# Full.net
KiCad netlist of a schematic drawn in EAGLE
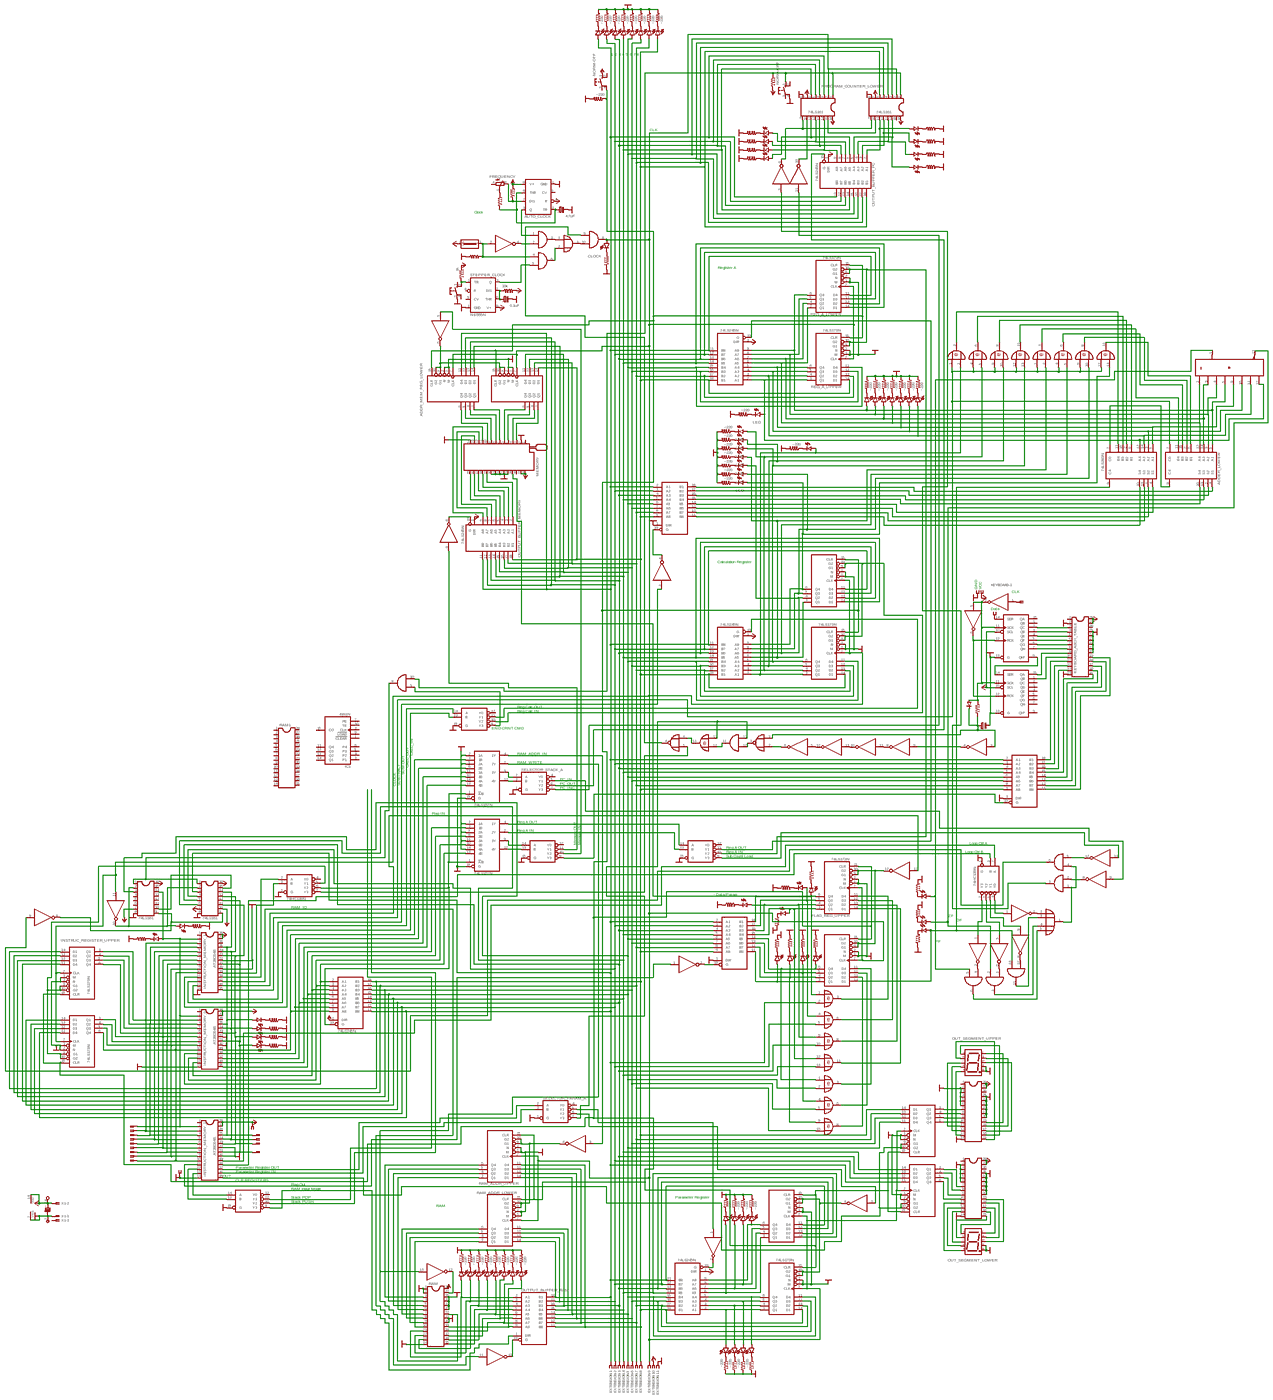
[diagram p0: schematic, sheet 1, overview]
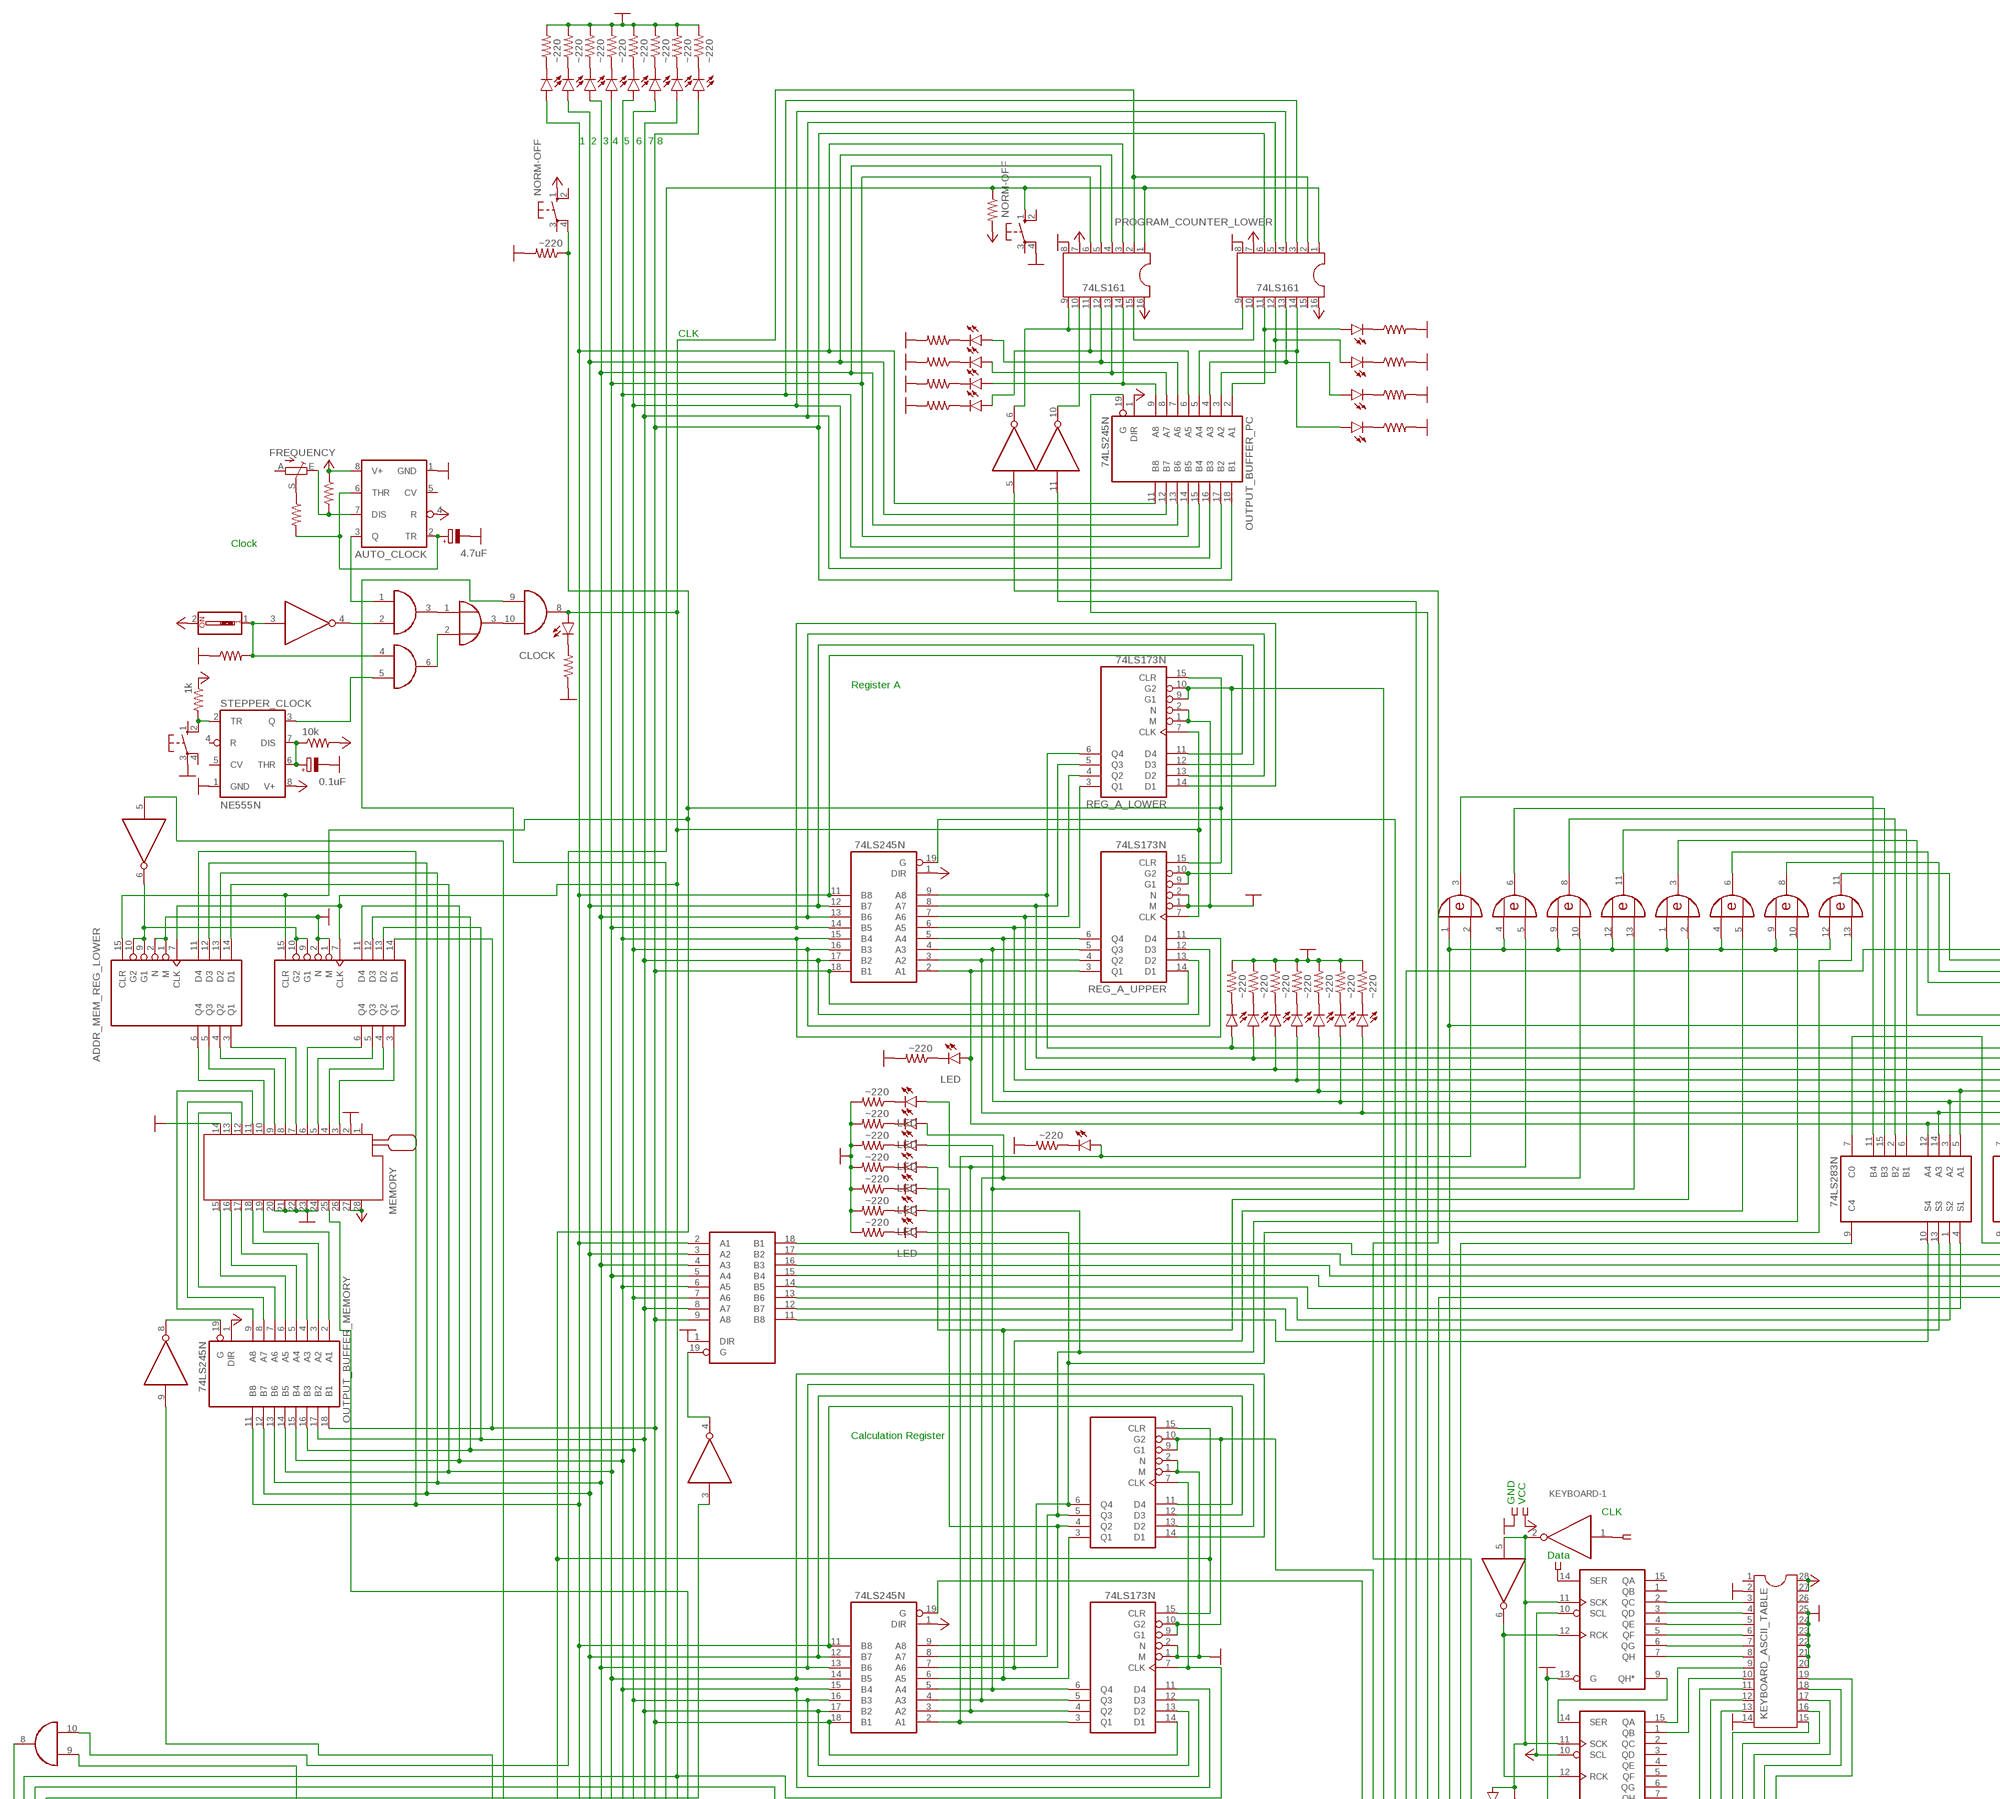
[diagram p1: schematic, sheet 1, part 1 of 4]
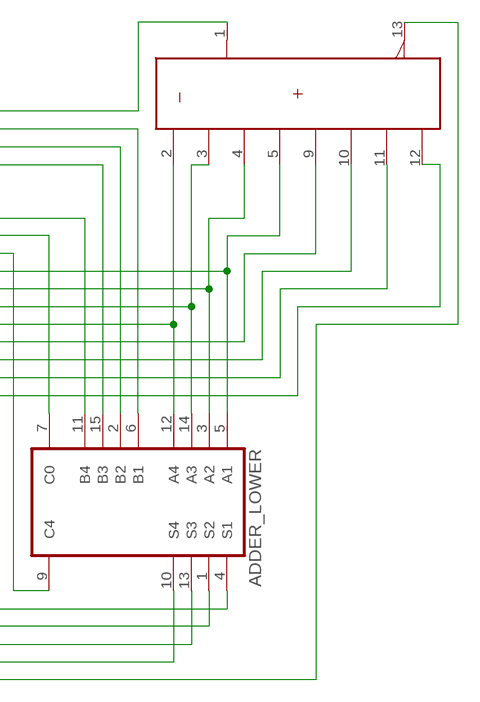
[diagram p2: schematic, sheet 1, part 2 of 4]
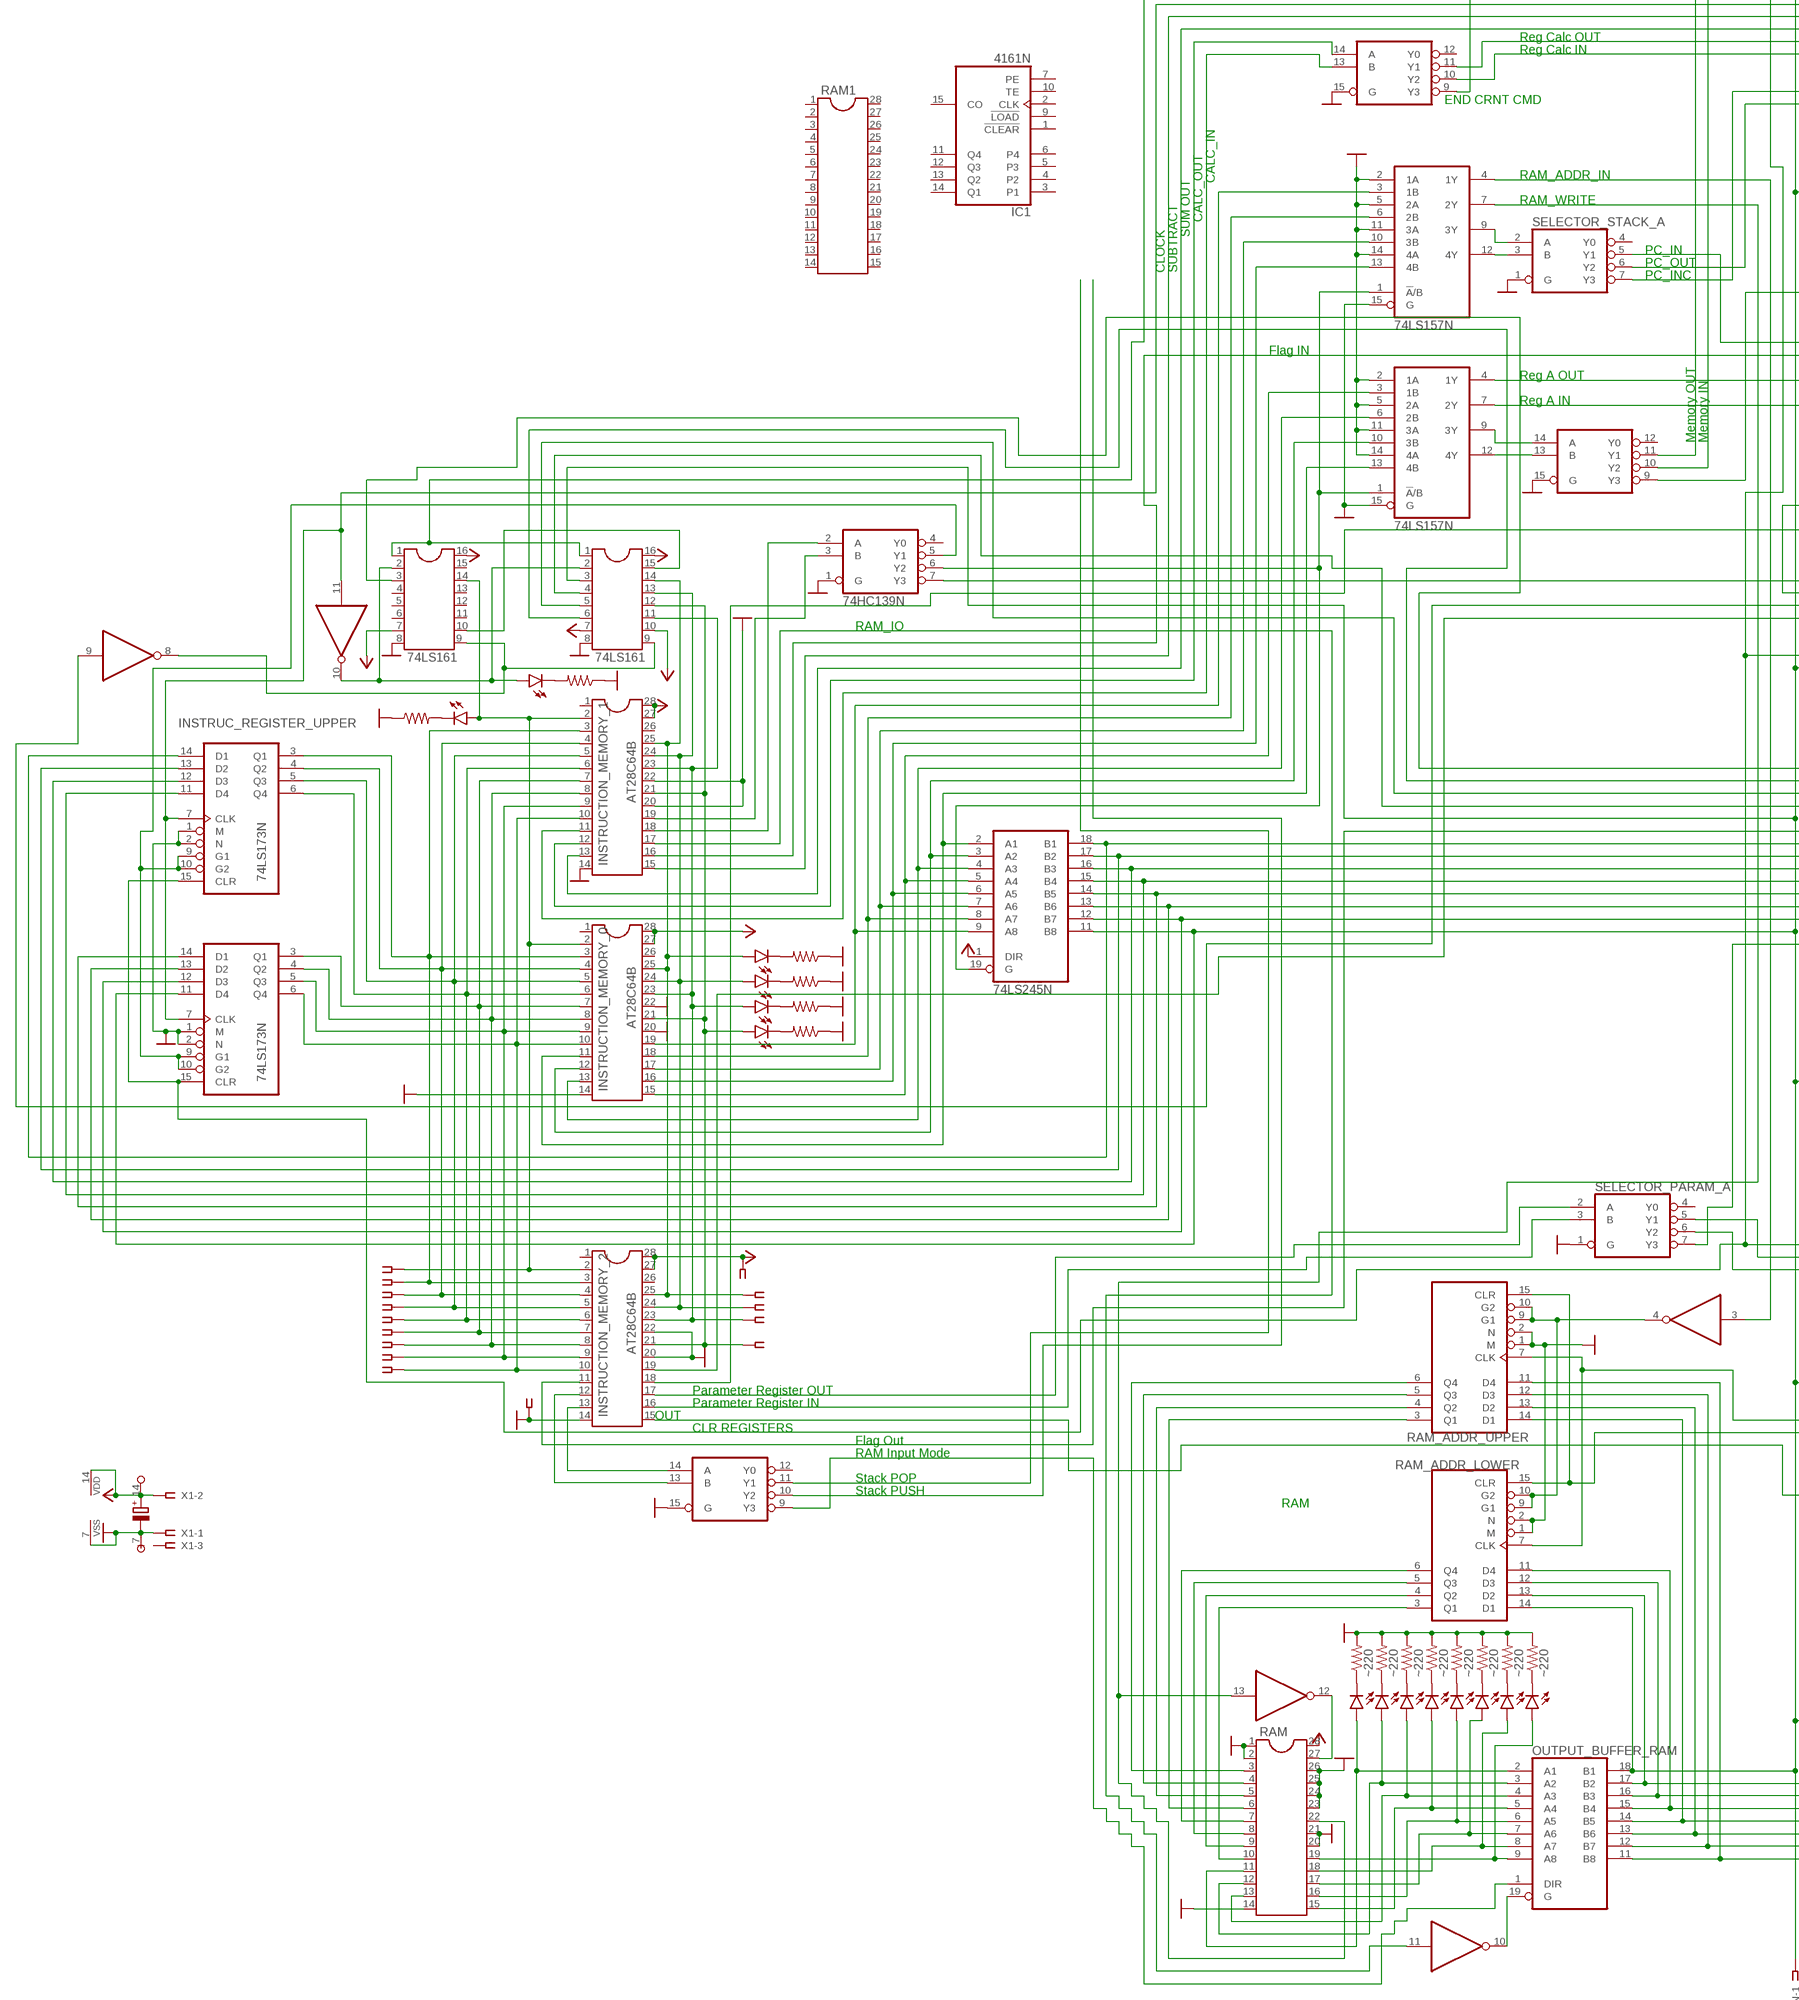
[diagram p3: schematic, sheet 1, part 3 of 4]
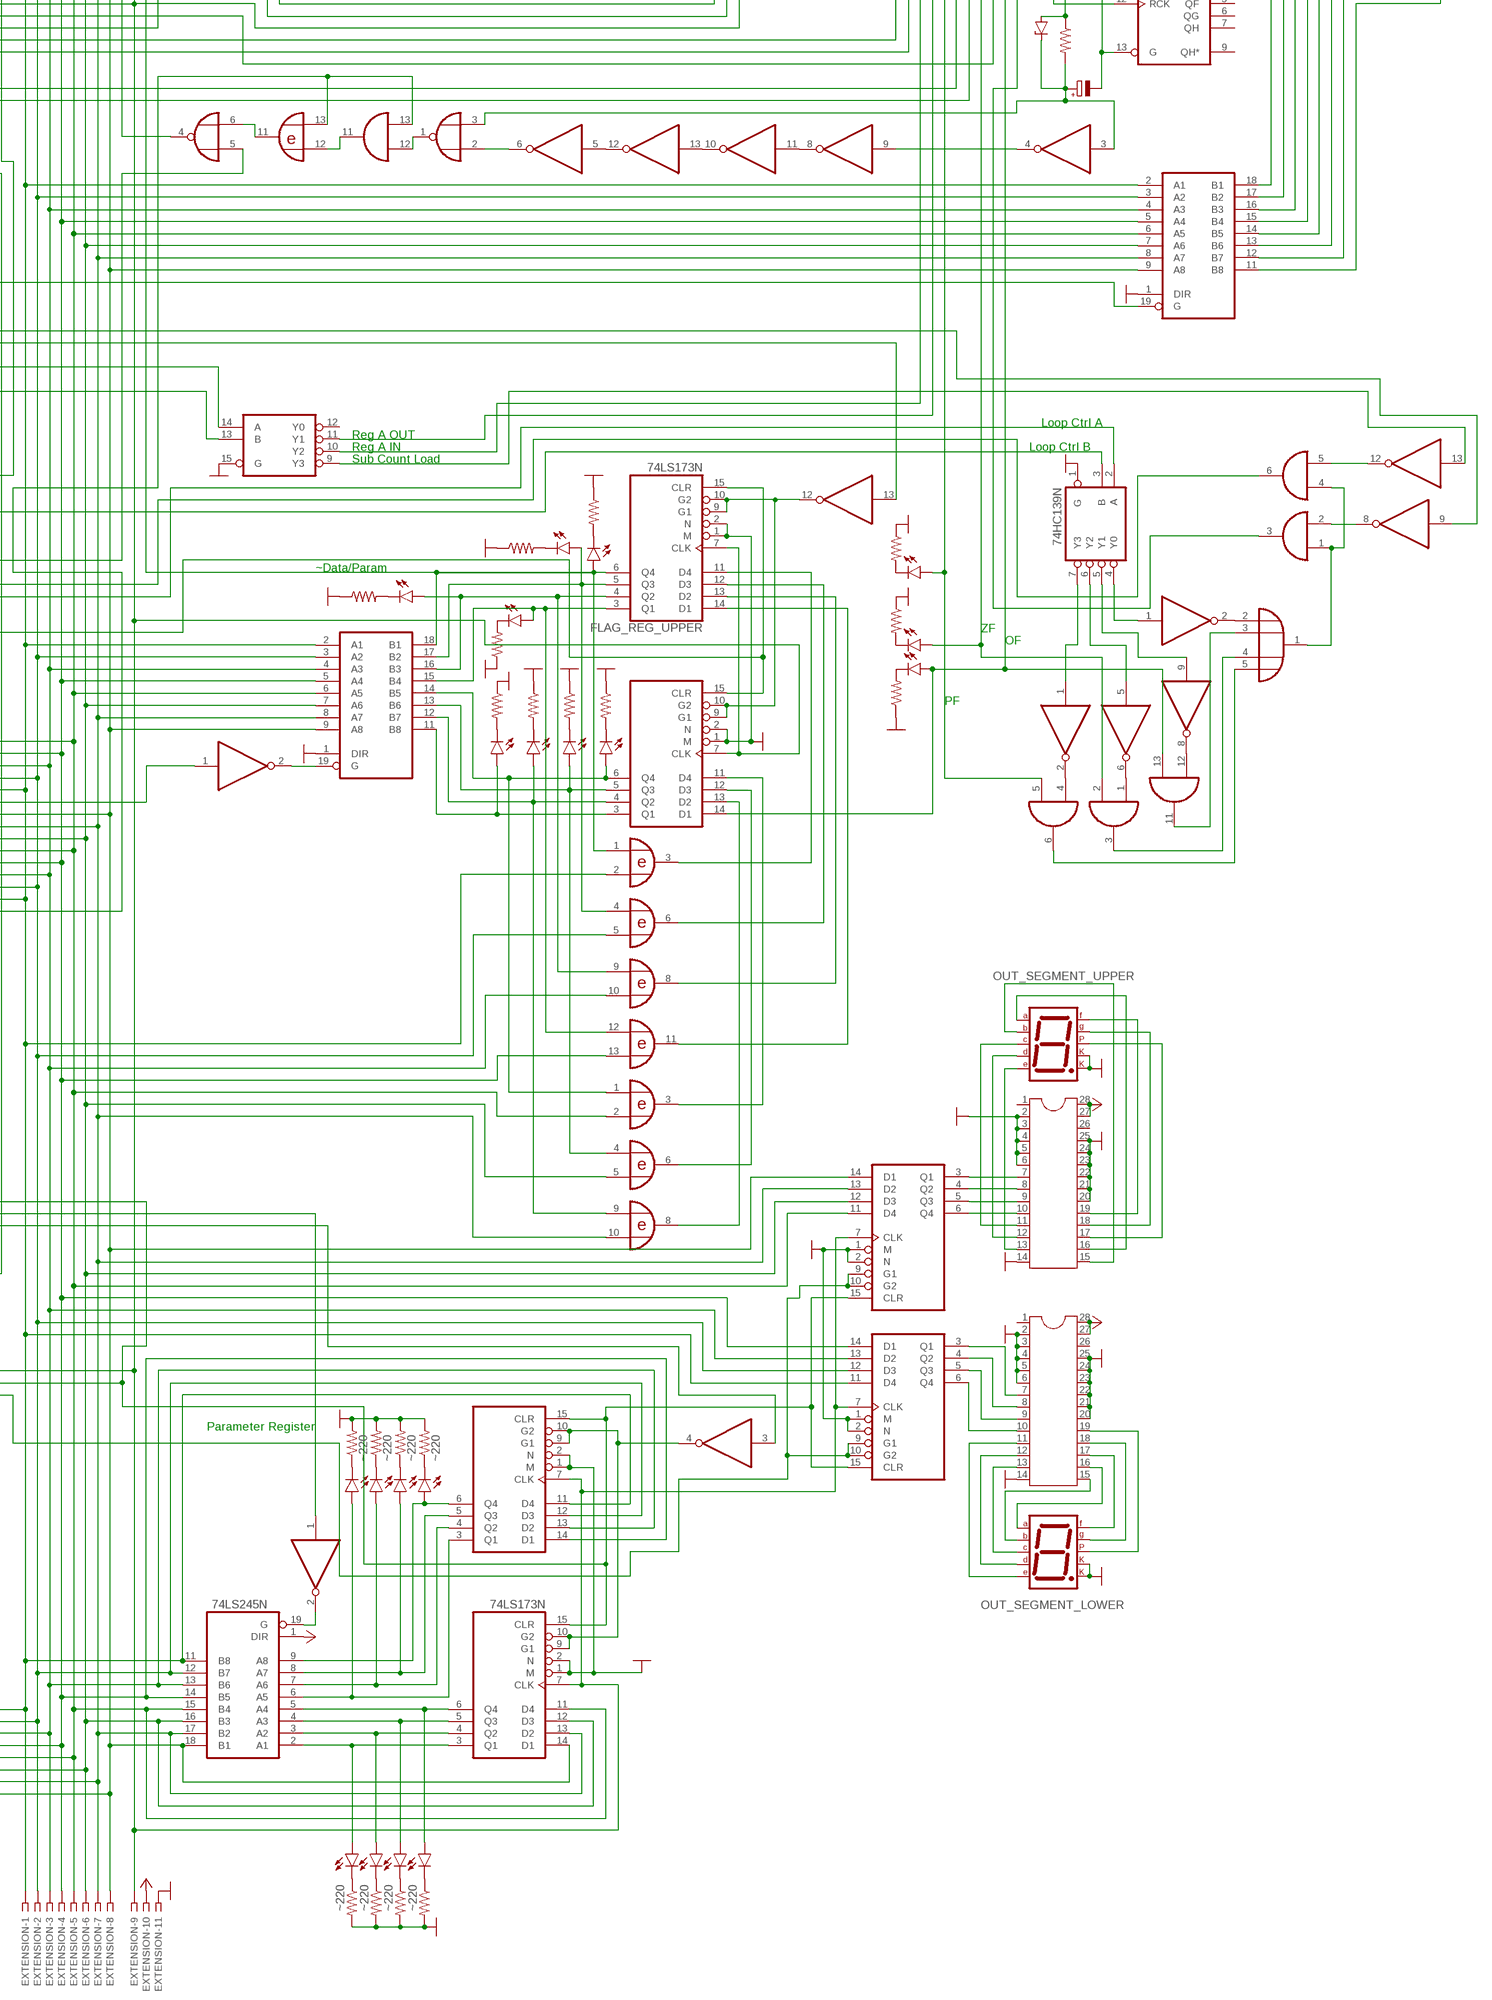
[diagram p4: schematic, sheet 1, part 4 of 4]

(export (version "E")
  (design (tool "Eeschema 10.0.6"))
  (components
    (comp (ref "4_INP_OR_GATE")
      (value "4072N")
      (footprint "eagle-import:DIL14")
      (libsource (lib "eagle-import") (part "4072N"))
    )
    (comp (ref "ADDER_LOWER")
      (value "74LS283N")
      (footprint "eagle-import:DIL16")
      (libsource (lib "eagle-import") (part "74283NLS"))
    )
    (comp (ref "ADDER_UPPER")
      (value "74LS283N")
      (footprint "eagle-import:DIL16")
      (libsource (lib "eagle-import") (part "74283NLS"))
    )
    (comp (ref "ADDR_MEM_REG_LOWER")
      (value "74LS173N")
      (footprint "eagle-import:DIL16")
      (libsource (lib "eagle-import") (part "74173NLS"))
    )
    (comp (ref "ADDR_MEM_REG_UPPER")
      (value "74LS173N")
      (footprint "eagle-import:DIL16")
      (libsource (lib "eagle-import") (part "74173NLS"))
    )
    (comp (ref "AND_GATE3_")
      (value "74LS08N")
      (footprint "eagle-import:DIL14")
      (libsource (lib "eagle-import") (part "7408NLS"))
    )
    (comp (ref "AND_GATE4_")
      (value "74LS08N")
      (footprint "eagle-import:DIL14")
      (libsource (lib "eagle-import") (part "7408NLS"))
    )
    (comp (ref "AND_GATE_")
      (value "74LS08N")
      (footprint "eagle-import:DIL14")
      (libsource (lib "eagle-import") (part "7408NLS"))
    )
    (comp (ref "AUTO_CLOCK")
      (value "NE555N")
      (footprint "eagle-import:DIL08")
      (libsource (lib "eagle-import") (part "555NNE"))
    )
    (comp (ref "C1")
      (value "4.7uF")
      (footprint "eagle-import:E2-5")
      (libsource (lib "eagle-import") (part "CPOL-EUE2-5"))
    )
    (comp (ref "C2")
      (value "0.1uF")
      (footprint "eagle-import:E2-5")
      (libsource (lib "eagle-import") (part "CPOL-EUE2-5"))
    )
    (comp (ref "C3")
      (value "0.1uF")
      (footprint "eagle-import:E2-5")
      (libsource (lib "eagle-import") (part "CPOL-EUE2-5"))
    )
    (comp (ref "C4")
      (value "0.1uF")
      (footprint "eagle-import:E2-5")
      (libsource (lib "eagle-import") (part "CPOL-EUE2-5"))
    )
    (comp (ref "CLK_MODE")
      (value "SWITCH")
      (footprint "eagle-import:EDG-01")
      (libsource (lib "eagle-import") (part "SW_DIP-1"))
    )
    (comp (ref "CLK_TRIGGER")
      (value "SWITCH")
      (footprint "eagle-import:B3F-10XX")
      (fields (field (name "MPN") "B3F-1000"))
      (libsource (lib "eagle-import") (part "10-XX"))
    )
    (comp (ref "CLOCK")
      (value "Yellow")
      (footprint "eagle-import:LED5MM")
      (libsource (lib "eagle-import") (part "LED5MM"))
    )
    (comp (ref "D1")
      (value "1N4728")
      (footprint "eagle-import:DO41Z10")
      (libsource (lib "eagle-import") (part "1N4728"))
    )
    (comp (ref "DATABUS_1")
      (value "LED")
      (footprint "eagle-import:LED5MM")
      (libsource (lib "eagle-import") (part "LED5MM"))
    )
    (comp (ref "DATABUS_2")
      (value "LED")
      (footprint "eagle-import:LED5MM")
      (libsource (lib "eagle-import") (part "LED5MM"))
    )
    (comp (ref "DATABUS_3")
      (value "LED")
      (footprint "eagle-import:LED5MM")
      (libsource (lib "eagle-import") (part "LED5MM"))
    )
    (comp (ref "DATABUS_4")
      (value "LED")
      (footprint "eagle-import:LED5MM")
      (libsource (lib "eagle-import") (part "LED5MM"))
    )
    (comp (ref "DATABUS_5")
      (value "LED")
      (footprint "eagle-import:LED5MM")
      (libsource (lib "eagle-import") (part "LED5MM"))
    )
    (comp (ref "DATABUS_6")
      (value "LED")
      (footprint "eagle-import:LED5MM")
      (libsource (lib "eagle-import") (part "LED5MM"))
    )
    (comp (ref "DATABUS_7")
      (value "LED")
      (footprint "eagle-import:LED5MM")
      (libsource (lib "eagle-import") (part "LED5MM"))
    )
    (comp (ref "DATABUS_8")
      (value "LED")
      (footprint "eagle-import:LED5MM")
      (libsource (lib "eagle-import") (part "LED5MM"))
    )
    (comp (ref "EXTENSION")
      (value "SSW-111-02-G-S")
      (footprint "eagle-import:SSW-111-02-G-S")
      (fields (field (name "MF") "Samtec Inc."))
      (libsource (lib "eagle-import") (part "SSW-111-02-G-S"))
    )
    (comp (ref "FLAG_1")
      (value "LED")
      (footprint "eagle-import:LED5MM")
      (libsource (lib "eagle-import") (part "LED5MM"))
    )
    (comp (ref "FLAG_2")
      (value "LED")
      (footprint "eagle-import:LED5MM")
      (libsource (lib "eagle-import") (part "LED5MM"))
    )
    (comp (ref "FLAG_3")
      (value "LED")
      (footprint "eagle-import:LED5MM")
      (libsource (lib "eagle-import") (part "LED5MM"))
    )
    (comp (ref "FLAG_4")
      (value "LED")
      (footprint "eagle-import:LED5MM")
      (libsource (lib "eagle-import") (part "LED5MM"))
    )
    (comp (ref "FLAG_5")
      (value "LED")
      (footprint "eagle-import:LED5MM")
      (libsource (lib "eagle-import") (part "LED5MM"))
    )
    (comp (ref "FLAG_6")
      (value "LED")
      (footprint "eagle-import:LED5MM")
      (libsource (lib "eagle-import") (part "LED5MM"))
    )
    (comp (ref "FLAG_7")
      (value "LED")
      (footprint "eagle-import:LED5MM")
      (libsource (lib "eagle-import") (part "LED5MM"))
    )
    (comp (ref "FLAG_8")
      (value "LED")
      (footprint "eagle-import:LED5MM")
      (libsource (lib "eagle-import") (part "LED5MM"))
    )
    (comp (ref "FLAG_REG_LOWER")
      (value "74LS173N")
      (footprint "eagle-import:DIL16")
      (libsource (lib "eagle-import") (part "74173NLS"))
    )
    (comp (ref "FLAG_REG_UPPER")
      (value "74LS173N")
      (footprint "eagle-import:DIL16")
      (libsource (lib "eagle-import") (part "74173NLS"))
    )
    (comp (ref "FREQUENCY")
      (value "100k")
      (footprint "eagle-import:RJ9W")
      (libsource (lib "eagle-import") (part "TRIM_EU-RJ9W"))
    )
    (comp (ref "IC1")
      (value "4161N")
      (footprint "eagle-import:DIL16")
      (libsource (lib "eagle-import") (part "4161N"))
    )
    (comp (ref "INSTRUCTIONS_EXTENSION")
      (value "SSW-115-02-G-S")
      (footprint "eagle-import:SSW-115-02-G-S")
      (fields (field (name "MF") "Samtec Inc."))
      (libsource (lib "eagle-import") (part "SSW-115-02-G-S"))
    )
    (comp (ref "INSTRUCTION_MEMORY_0")
      (value "AT28C64B")
      (footprint "eagle-import:DIL28-6")
      (libsource (lib "eagle-import") (part "DIL28"))
    )
    (comp (ref "INSTRUCTION_MEMORY_1")
      (value "AT28C64B")
      (footprint "eagle-import:DIL28-6")
      (libsource (lib "eagle-import") (part "DIL28"))
    )
    (comp (ref "INSTRUCTION_MEMORY_2")
      (value "AT28C64B")
      (footprint "eagle-import:DIL28-6")
      (libsource (lib "eagle-import") (part "DIL28"))
    )
    (comp (ref "INSTRUC_REGISTER_LOWER")
      (value "74LS173N")
      (footprint "eagle-import:DIL16")
      (libsource (lib "eagle-import") (part "74173NLS"))
    )
    (comp (ref "INSTRUC_REGISTER_UPPER")
      (value "74LS173N")
      (footprint "eagle-import:DIL16")
      (libsource (lib "eagle-import") (part "74173NLS"))
    )
    (comp (ref "INVERTED_CLK_LED")
      (value "LED")
      (footprint "eagle-import:LED5MM")
      (libsource (lib "eagle-import") (part "LED5MM"))
    )
    (comp (ref "KEYBOARD")
      (value "SSW-104-02-G-S")
      (footprint "eagle-import:SSW-104-02-G-S")
      (fields (field (name "MF") "Samtec Inc."))
      (libsource (lib "eagle-import") (part "SSW-104-02-G-S"))
    )
    (comp (ref "KEYBOARD_ASCII_TABLE")
      (value "AT28C64B")
      (footprint "eagle-import:DIL28-6")
      (libsource (lib "eagle-import") (part "DIL28"))
    )
    (comp (ref "KEYBOARD_SHIFT_LOWER")
      (value "74LS595N")
      (footprint "eagle-import:DIL16")
      (libsource (lib "eagle-import") (part "74595NLS"))
    )
    (comp (ref "KEYBOARD_SHIFT_UPPER")
      (value "74LS595N")
      (footprint "eagle-import:DIL16")
      (libsource (lib "eagle-import") (part "74595NLS"))
    )
    (comp (ref "LED_A_REG_1")
      (value "LED")
      (footprint "eagle-import:LED5MM")
      (libsource (lib "eagle-import") (part "LED5MM"))
    )
    (comp (ref "LED_A_REG_2")
      (value "LED")
      (footprint "eagle-import:LED5MM")
      (libsource (lib "eagle-import") (part "LED5MM"))
    )
    (comp (ref "LED_A_REG_3")
      (value "LED")
      (footprint "eagle-import:LED5MM")
      (libsource (lib "eagle-import") (part "LED5MM"))
    )
    (comp (ref "LED_A_REG_4")
      (value "LED")
      (footprint "eagle-import:LED5MM")
      (libsource (lib "eagle-import") (part "LED5MM"))
    )
    (comp (ref "LED_A_REG_5")
      (value "LED")
      (footprint "eagle-import:LED5MM")
      (libsource (lib "eagle-import") (part "LED5MM"))
    )
    (comp (ref "LED_A_REG_6")
      (value "LED")
      (footprint "eagle-import:LED5MM")
      (libsource (lib "eagle-import") (part "LED5MM"))
    )
    (comp (ref "LED_A_REG_7")
      (value "LED")
      (footprint "eagle-import:LED5MM")
      (libsource (lib "eagle-import") (part "LED5MM"))
    )
    (comp (ref "LED_A_REG_8")
      (value "LED")
      (footprint "eagle-import:LED5MM")
      (libsource (lib "eagle-import") (part "LED5MM"))
    )
    (comp (ref "LED_B_REG_1")
      (value "LED")
      (footprint "eagle-import:LED5MM")
      (libsource (lib "eagle-import") (part "LED5MM"))
    )
    (comp (ref "LED_B_REG_2")
      (value "LED")
      (footprint "eagle-import:LED5MM")
      (libsource (lib "eagle-import") (part "LED5MM"))
    )
    (comp (ref "LED_B_REG_3")
      (value "LED")
      (footprint "eagle-import:LED5MM")
      (libsource (lib "eagle-import") (part "LED5MM"))
    )
    (comp (ref "LED_B_REG_4")
      (value "LED")
      (footprint "eagle-import:LED5MM")
      (libsource (lib "eagle-import") (part "LED5MM"))
    )
    (comp (ref "LED_B_REG_5")
      (value "LED")
      (footprint "eagle-import:LED5MM")
      (libsource (lib "eagle-import") (part "LED5MM"))
    )
    (comp (ref "LED_B_REG_6")
      (value "LED")
      (footprint "eagle-import:LED5MM")
      (libsource (lib "eagle-import") (part "LED5MM"))
    )
    (comp (ref "LED_B_REG_7")
      (value "LED")
      (footprint "eagle-import:LED5MM")
      (libsource (lib "eagle-import") (part "LED5MM"))
    )
    (comp (ref "LED_B_REG_8")
      (value "LED")
      (footprint "eagle-import:LED5MM")
      (libsource (lib "eagle-import") (part "LED5MM"))
    )
    (comp (ref "MEMORY")
      (value "228-1277-00-0602J")
      (footprint "eagle-import:228-1277-00-0602J")
      (fields (field (name "MF") "3M"))
      (libsource (lib "eagle-import") (part "228-?00-0602J1277-"))
    )
    (comp (ref "MICRO_COUNTER_LOWER")
      (value "74LS161")
      (footprint "eagle-import:DIL16")
      (libsource (lib "eagle-import") (part "DIL16"))
    )
    (comp (ref "MICRO_COUNTER_UPPER")
      (value "74LS161")
      (footprint "eagle-import:DIL16")
      (libsource (lib "eagle-import") (part "DIL16"))
    )
    (comp (ref "NOR_GATE_")
      (value "74LS02N")
      (footprint "eagle-import:DIL14")
      (libsource (lib "eagle-import") (part "7402NLS"))
    )
    (comp (ref "NOT_GATE1_")
      (value "74LS04N")
      (footprint "eagle-import:DIL14")
      (libsource (lib "eagle-import") (part "7404NLS"))
    )
    (comp (ref "NOT_GATE2_")
      (value "74LS04N")
      (footprint "eagle-import:DIL14")
      (libsource (lib "eagle-import") (part "7404NLS"))
    )
    (comp (ref "NOT_GATE3_")
      (value "74LS04N")
      (footprint "eagle-import:DIL14")
      (libsource (lib "eagle-import") (part "7404NLS"))
    )
    (comp (ref "NOT_GATE4_")
      (value "74LS04N")
      (footprint "eagle-import:DIL14")
      (fields (field (name "SPICEPREFIX") "B"))
      (libsource (lib "eagle-import") (part "7404NLS"))
    )
    (comp (ref "NOT_GATE_")
      (value "74LS04N")
      (footprint "eagle-import:DIL14")
      (libsource (lib "eagle-import") (part "7404NLS"))
    )
    (comp (ref "OR_GATE_")
      (value "74LS32N")
      (footprint "eagle-import:DIL14")
      (libsource (lib "eagle-import") (part "7432NLS"))
    )
    (comp (ref "OUTPUT_BUFFER_ALU")
      (value "74LS245N")
      (footprint "eagle-import:DIL20")
      (libsource (lib "eagle-import") (part "74245NLS"))
    )
    (comp (ref "OUTPUT_BUFFER_CALC_REG")
      (value "74LS245N")
      (footprint "eagle-import:DIL20")
      (libsource (lib "eagle-import") (part "74245NLS"))
    )
    (comp (ref "OUTPUT_BUFFER_FLAGS")
      (value "74HC245N")
      (footprint "eagle-import:DIL20")
      (libsource (lib "eagle-import") (part "74245NHC"))
    )
    (comp (ref "OUTPUT_BUFFER_INSTRUCTION")
      (value "74LS245N")
      (footprint "eagle-import:DIL20")
      (libsource (lib "eagle-import") (part "74xx-us_88_74245NLS"))
    )
    (comp (ref "OUTPUT_BUFFER_KEYBOARD")
      (value "74LS245N")
      (footprint "eagle-import:DIL20")
      (libsource (lib "eagle-import") (part "74245NLS"))
    )
    (comp (ref "OUTPUT_BUFFER_MEMORY")
      (value "74LS245N")
      (footprint "eagle-import:DIL20")
      (libsource (lib "eagle-import") (part "74245NLS"))
    )
    (comp (ref "OUTPUT_BUFFER_PARAM_REG")
      (value "74LS245N")
      (footprint "eagle-import:DIL20")
      (libsource (lib "eagle-import") (part "74245NLS"))
    )
    (comp (ref "OUTPUT_BUFFER_PC")
      (value "74LS245N")
      (footprint "eagle-import:DIL20")
      (libsource (lib "eagle-import") (part "74245NLS"))
    )
    (comp (ref "OUTPUT_BUFFER_RAM")
      (value "74HC245N")
      (footprint "eagle-import:DIL20")
      (libsource (lib "eagle-import") (part "74245NHC"))
    )
    (comp (ref "OUTPUT_BUFFER_REG_A")
      (value "74LS245N")
      (footprint "eagle-import:DIL20")
      (libsource (lib "eagle-import") (part "74245NLS"))
    )
    (comp (ref "OUT_REG_LOWER")
      (value "74LS173N")
      (footprint "eagle-import:DIL16")
      (libsource (lib "eagle-import") (part "74173NLS"))
    )
    (comp (ref "OUT_REG_UPPER")
      (value "74LS173N")
      (footprint "eagle-import:DIL16")
      (libsource (lib "eagle-import") (part "74173NLS"))
    )
    (comp (ref "OUT_ROM_LOWER")
      (value "AT28C64B")
      (footprint "eagle-import:DIL28-6")
      (libsource (lib "eagle-import") (part "DIL28"))
    )
    (comp (ref "OUT_ROM_UPPER")
      (value "AT28C64B")
      (footprint "eagle-import:DIL28-6")
      (libsource (lib "eagle-import") (part "DIL28"))
    )
    (comp (ref "OUT_SEGMENT_LOWER")
      (value "LED")
      (footprint "eagle-import:7SEG-13")
      (libsource (lib "eagle-import") (part "7SEG-CK"))
    )
    (comp (ref "OUT_SEGMENT_UPPER")
      (value "LED")
      (footprint "eagle-import:7SEG-13")
      (libsource (lib "eagle-import") (part "7SEG-CK"))
    )
    (comp (ref "OVERFLOW_FLAG")
      (value "LED")
      (footprint "eagle-import:LED5MM")
      (libsource (lib "eagle-import") (part "LED5MM"))
    )
    (comp (ref "PARAM_LED_1")
      (value "LED3MM")
      (footprint "eagle-import:LED3MM")
      (libsource (lib "eagle-import") (part "LED3MM"))
    )
    (comp (ref "PARAM_LED_2")
      (value "LED3MM")
      (footprint "eagle-import:LED3MM")
      (libsource (lib "eagle-import") (part "LED3MM"))
    )
    (comp (ref "PARAM_LED_3")
      (value "LED3MM")
      (footprint "eagle-import:LED3MM")
      (libsource (lib "eagle-import") (part "LED3MM"))
    )
    (comp (ref "PARAM_LED_4")
      (value "LED3MM")
      (footprint "eagle-import:LED3MM")
      (libsource (lib "eagle-import") (part "LED3MM"))
    )
    (comp (ref "PARAM_LED_5")
      (value "LED3MM")
      (footprint "eagle-import:LED3MM")
      (libsource (lib "eagle-import") (part "LED3MM"))
    )
    (comp (ref "PARAM_LED_6")
      (value "LED3MM")
      (footprint "eagle-import:LED3MM")
      (libsource (lib "eagle-import") (part "LED3MM"))
    )
    (comp (ref "PARAM_LED_7")
      (value "LED3MM")
      (footprint "eagle-import:LED3MM")
      (libsource (lib "eagle-import") (part "LED3MM"))
    )
    (comp (ref "PARAM_LED_8")
      (value "LED3MM")
      (footprint "eagle-import:LED3MM")
      (libsource (lib "eagle-import") (part "LED3MM"))
    )
    (comp (ref "PC_1")
      (value "LED5MM")
      (footprint "eagle-import:LED5MM")
      (libsource (lib "eagle-import") (part "LED5MM"))
    )
    (comp (ref "PC_2")
      (value "LED5MM")
      (footprint "eagle-import:LED5MM")
      (libsource (lib "eagle-import") (part "LED5MM"))
    )
    (comp (ref "PC_3")
      (value "LED5MM")
      (footprint "eagle-import:LED5MM")
      (libsource (lib "eagle-import") (part "LED5MM"))
    )
    (comp (ref "PC_4")
      (value "LED5MM")
      (footprint "eagle-import:LED5MM")
      (libsource (lib "eagle-import") (part "LED5MM"))
    )
    (comp (ref "PC_5")
      (value "LED5MM")
      (footprint "eagle-import:LED5MM")
      (libsource (lib "eagle-import") (part "LED5MM"))
    )
    (comp (ref "PC_6")
      (value "LED5MM")
      (footprint "eagle-import:LED5MM")
      (libsource (lib "eagle-import") (part "LED5MM"))
    )
    (comp (ref "PC_7")
      (value "LED5MM")
      (footprint "eagle-import:LED5MM")
      (libsource (lib "eagle-import") (part "LED5MM"))
    )
    (comp (ref "PC_8")
      (value "LED5MM")
      (footprint "eagle-import:LED5MM")
      (libsource (lib "eagle-import") (part "LED5MM"))
    )
    (comp (ref "POSITIVE_FLAG")
      (value "LED")
      (footprint "eagle-import:LED5MM")
      (libsource (lib "eagle-import") (part "LED5MM"))
    )
    (comp (ref "PROGRAM_COUNTER_LOWER")
      (value "74LS161")
      (footprint "eagle-import:DIL16")
      (libsource (lib "eagle-import") (part "DIL16"))
    )
    (comp (ref "PROGRAM_COUNTER_UPPER")
      (value "74LS161")
      (footprint "eagle-import:DIL16")
      (libsource (lib "eagle-import") (part "DIL16"))
    )
    (comp (ref "R1")
      (value "1k")
      (footprint "eagle-import:0204_7")
      (libsource (lib "eagle-import") (part "R-US_0204/7"))
    )
    (comp (ref "R2")
      (value "1k")
      (footprint "eagle-import:0204_7")
      (libsource (lib "eagle-import") (part "R-US_0204/7"))
    )
    (comp (ref "R3")
      (value "10k")
      (footprint "eagle-import:0204_7")
      (libsource (lib "eagle-import") (part "R-US_0204/7"))
    )
    (comp (ref "R4")
      (value "220")
      (footprint "eagle-import:0204_7")
      (libsource (lib "eagle-import") (part "R-US_0204/7"))
    )
    (comp (ref "R5")
      (value "~220")
      (footprint "eagle-import:0204_7")
      (libsource (lib "eagle-import") (part "R-US_0204/7"))
    )
    (comp (ref "R6")
      (value "~220")
      (footprint "eagle-import:0204_7")
      (libsource (lib "eagle-import") (part "R-US_0204/7"))
    )
    (comp (ref "R7")
      (value "220")
      (footprint "eagle-import:0204_7")
      (libsource (lib "eagle-import") (part "R-US_0204/7"))
    )
    (comp (ref "R8")
      (value "~220")
      (footprint "eagle-import:0204_7")
      (libsource (lib "eagle-import") (part "R-US_0204/7"))
    )
    (comp (ref "R9")
      (value "~220")
      (footprint "eagle-import:0204_7")
      (libsource (lib "eagle-import") (part "R-US_0204/7"))
    )
    (comp (ref "R10")
      (value "~220")
      (footprint "eagle-import:0204_7")
      (libsource (lib "eagle-import") (part "R-US_0204/7"))
    )
    (comp (ref "R11")
      (value "~220")
      (footprint "eagle-import:0204_7")
      (libsource (lib "eagle-import") (part "R-US_0204/7"))
    )
    (comp (ref "R12")
      (value "~220")
      (footprint "eagle-import:0204_7")
      (libsource (lib "eagle-import") (part "R-US_0204/7"))
    )
    (comp (ref "R13")
      (value "~220")
      (footprint "eagle-import:0204_7")
      (libsource (lib "eagle-import") (part "R-US_0204/7"))
    )
    (comp (ref "R14")
      (value "~220")
      (footprint "eagle-import:0204_7")
      (libsource (lib "eagle-import") (part "R-US_0204/7"))
    )
    (comp (ref "R15")
      (value "~220")
      (footprint "eagle-import:0204_7")
      (libsource (lib "eagle-import") (part "R-US_0204/7"))
    )
    (comp (ref "R16")
      (value "~220")
      (footprint "eagle-import:0204_7")
      (libsource (lib "eagle-import") (part "R-US_0204/7"))
    )
    (comp (ref "R17")
      (value "~220")
      (footprint "eagle-import:0204_7")
      (libsource (lib "eagle-import") (part "R-US_0204/7"))
    )
    (comp (ref "R18")
      (value "~220")
      (footprint "eagle-import:0204_7")
      (libsource (lib "eagle-import") (part "R-US_0204/7"))
    )
    (comp (ref "R19")
      (value "~220")
      (footprint "eagle-import:0204_7")
      (libsource (lib "eagle-import") (part "R-US_0204/7"))
    )
    (comp (ref "R20")
      (value "~220")
      (footprint "eagle-import:0204_7")
      (libsource (lib "eagle-import") (part "R-US_0204/7"))
    )
    (comp (ref "R21")
      (value "~220")
      (footprint "eagle-import:0204_7")
      (libsource (lib "eagle-import") (part "R-US_0204/7"))
    )
    (comp (ref "R22")
      (value "~220")
      (footprint "eagle-import:0204_7")
      (libsource (lib "eagle-import") (part "R-US_0204/7"))
    )
    (comp (ref "R23")
      (value "~220")
      (footprint "eagle-import:0204_7")
      (libsource (lib "eagle-import") (part "R-US_0204/7"))
    )
    (comp (ref "R24")
      (value "~220")
      (footprint "eagle-import:0204_7")
      (libsource (lib "eagle-import") (part "R-US_0204/7"))
    )
    (comp (ref "R25")
      (value "~220")
      (footprint "eagle-import:0204_7")
      (libsource (lib "eagle-import") (part "R-US_0204/7"))
    )
    (comp (ref "R26")
      (value "~220")
      (footprint "eagle-import:0204_7")
      (libsource (lib "eagle-import") (part "R-US_0204/7"))
    )
    (comp (ref "R27")
      (value "~220")
      (footprint "eagle-import:0204_7")
      (libsource (lib "eagle-import") (part "R-US_0204/7"))
    )
    (comp (ref "R28")
      (value "~220")
      (footprint "eagle-import:0204_7")
      (libsource (lib "eagle-import") (part "R-US_0204/7"))
    )
    (comp (ref "R29")
      (value "~220")
      (footprint "eagle-import:0204_7")
      (libsource (lib "eagle-import") (part "R-US_0204/7"))
    )
    (comp (ref "R30")
      (value "~220")
      (footprint "eagle-import:0204_7")
      (libsource (lib "eagle-import") (part "R-US_0204/7"))
    )
    (comp (ref "R31")
      (value "~220")
      (footprint "eagle-import:0204_7")
      (libsource (lib "eagle-import") (part "R-US_0204/7"))
    )
    (comp (ref "R32")
      (value "~220")
      (footprint "eagle-import:0204_7")
      (libsource (lib "eagle-import") (part "R-US_0204/7"))
    )
    (comp (ref "R33")
      (value "~220")
      (footprint "eagle-import:0204_7")
      (libsource (lib "eagle-import") (part "R-US_0204/7"))
    )
    (comp (ref "R34")
      (value "~220")
      (footprint "eagle-import:0204_7")
      (libsource (lib "eagle-import") (part "R-US_0204/7"))
    )
    (comp (ref "R35")
      (value "~220")
      (footprint "eagle-import:0204_7")
      (libsource (lib "eagle-import") (part "R-US_0204/7"))
    )
    (comp (ref "R36")
      (value "~220")
      (footprint "eagle-import:0204_7")
      (libsource (lib "eagle-import") (part "R-US_0204/7"))
    )
    (comp (ref "R37")
      (value "~220")
      (footprint "eagle-import:0204_7")
      (libsource (lib "eagle-import") (part "R-US_0204/7"))
    )
    (comp (ref "R38")
      (value "~220")
      (footprint "eagle-import:0204_7")
      (libsource (lib "eagle-import") (part "R-US_0204/7"))
    )
    (comp (ref "R39")
      (value "~220")
      (footprint "eagle-import:0204_7")
      (libsource (lib "eagle-import") (part "R-US_0204/7"))
    )
    (comp (ref "R40")
      (value "~220")
      (footprint "eagle-import:0204_7")
      (libsource (lib "eagle-import") (part "R-US_0204/7"))
    )
    (comp (ref "R41")
      (value "~220")
      (footprint "eagle-import:0204_7")
      (libsource (lib "eagle-import") (part "R-US_0204/7"))
    )
    (comp (ref "R42")
      (value "~220")
      (footprint "eagle-import:0204_7")
      (libsource (lib "eagle-import") (part "R-US_0204/7"))
    )
    (comp (ref "R43")
      (value "~220")
      (footprint "eagle-import:0204_7")
      (libsource (lib "eagle-import") (part "R-US_0204/7"))
    )
    (comp (ref "R44")
      (value "~220")
      (footprint "eagle-import:0204_7")
      (libsource (lib "eagle-import") (part "R-US_0204/7"))
    )
    (comp (ref "R45")
      (value "~220")
      (footprint "eagle-import:0204_7")
      (libsource (lib "eagle-import") (part "R-US_0204/7"))
    )
    (comp (ref "R53")
      (value "~220")
      (footprint "eagle-import:0204_7")
      (libsource (lib "eagle-import") (part "R-US_0204/7"))
    )
    (comp (ref "R54")
      (value "~220")
      (footprint "eagle-import:0204_7")
      (libsource (lib "eagle-import") (part "R-US_0204/7"))
    )
    (comp (ref "R55")
      (value "~220")
      (footprint "eagle-import:0204_7")
      (libsource (lib "eagle-import") (part "R-US_0204/7"))
    )
    (comp (ref "R56")
      (value "~220")
      (footprint "eagle-import:0204_7")
      (libsource (lib "eagle-import") (part "R-US_0204/7"))
    )
    (comp (ref "R57")
      (value "~220")
      (footprint "eagle-import:0204_7")
      (libsource (lib "eagle-import") (part "R-US_0204/7"))
    )
    (comp (ref "R58")
      (value "~220")
      (footprint "eagle-import:0204_7")
      (libsource (lib "eagle-import") (part "R-US_0204/7"))
    )
    (comp (ref "R59")
      (value "~220")
      (footprint "eagle-import:0204_7")
      (libsource (lib "eagle-import") (part "R-US_0204/7"))
    )
    (comp (ref "R60")
      (value "~220")
      (footprint "eagle-import:0204_7")
      (libsource (lib "eagle-import") (part "R-US_0204/7"))
    )
    (comp (ref "R61")
      (value "~220")
      (footprint "eagle-import:0204_7")
      (libsource (lib "eagle-import") (part "R-US_0204/7"))
    )
    (comp (ref "R62")
      (value "~220")
      (footprint "eagle-import:0204_7")
      (libsource (lib "eagle-import") (part "R-US_0204/7"))
    )
    (comp (ref "R63")
      (value "~220")
      (footprint "eagle-import:0204_7")
      (libsource (lib "eagle-import") (part "R-US_0204/7"))
    )
    (comp (ref "R64")
      (value "~220")
      (footprint "eagle-import:0204_7")
      (libsource (lib "eagle-import") (part "R-US_0204/7"))
    )
    (comp (ref "R65")
      (value "~220")
      (footprint "eagle-import:0204_7")
      (libsource (lib "eagle-import") (part "R-US_0204/7"))
    )
    (comp (ref "R66")
      (value "~220")
      (footprint "eagle-import:0204_7")
      (libsource (lib "eagle-import") (part "R-US_0204/7"))
    )
    (comp (ref "R67")
      (value "~220")
      (footprint "eagle-import:0204_7")
      (libsource (lib "eagle-import") (part "R-US_0204/7"))
    )
    (comp (ref "R68")
      (value "~220")
      (footprint "eagle-import:0204_7")
      (libsource (lib "eagle-import") (part "R-US_0204/7"))
    )
    (comp (ref "R69")
      (value "~220")
      (footprint "eagle-import:0204_7")
      (libsource (lib "eagle-import") (part "R-US_0204/7"))
    )
    (comp (ref "R70")
      (value "~220")
      (footprint "eagle-import:0204_7")
      (libsource (lib "eagle-import") (part "R-US_0204/7"))
    )
    (comp (ref "R71")
      (value "~220")
      (footprint "eagle-import:0204_7")
      (libsource (lib "eagle-import") (part "R-US_0204/7"))
    )
    (comp (ref "R72")
      (value "~220")
      (footprint "eagle-import:0204_7")
      (libsource (lib "eagle-import") (part "R-US_0204/7"))
    )
    (comp (ref "R73")
      (value "~220")
      (footprint "eagle-import:0204_7")
      (libsource (lib "eagle-import") (part "R-US_0204/7"))
    )
    (comp (ref "R74")
      (value "~220")
      (footprint "eagle-import:0204_7")
      (libsource (lib "eagle-import") (part "R-US_0204/7"))
    )
    (comp (ref "R75")
      (value "~220")
      (footprint "eagle-import:0204_7")
      (libsource (lib "eagle-import") (part "R-US_0204/7"))
    )
    (comp (ref "R76")
      (value "~220")
      (footprint "eagle-import:0204_7")
      (libsource (lib "eagle-import") (part "R-US_0204/7"))
    )
    (comp (ref "R77")
      (value "~220")
      (footprint "eagle-import:0204_7")
      (libsource (lib "eagle-import") (part "R-US_0204/7"))
    )
    (comp (ref "R78")
      (value "~220")
      (footprint "eagle-import:0204_7")
      (libsource (lib "eagle-import") (part "R-US_0204/7"))
    )
    (comp (ref "R79")
      (value "~220")
      (footprint "eagle-import:0204_7")
      (libsource (lib "eagle-import") (part "R-US_0204/7"))
    )
    (comp (ref "R80")
      (value "~220")
      (footprint "eagle-import:0204_7")
      (libsource (lib "eagle-import") (part "R-US_0204/7"))
    )
    (comp (ref "R81")
      (value "~220")
      (footprint "eagle-import:0204_7")
      (libsource (lib "eagle-import") (part "R-US_0204/7"))
    )
    (comp (ref "RAM")
      (value "71256SA15TPG")
      (footprint "eagle-import:DIL28-3")
      (libsource (lib "eagle-import") (part "DIL28-3"))
    )
    (comp (ref "RAM1")
      (value "71256SA15TPG")
      (footprint "eagle-import:DIL28-3")
      (libsource (lib "eagle-import") (part "DIL28-3"))
    )
    (comp (ref "RAM_ADDR_LOWER")
      (value "74LS173N")
      (footprint "eagle-import:DIL16")
      (libsource (lib "eagle-import") (part "74173NLS"))
    )
    (comp (ref "RAM_ADDR_UPPER")
      (value "74LS173N")
      (footprint "eagle-import:DIL16")
      (libsource (lib "eagle-import") (part "74173NLS"))
    )
    (comp (ref "RAM_LED_1")
      (value "LED3MM")
      (footprint "eagle-import:LED3MM")
      (libsource (lib "eagle-import") (part "LED3MM"))
    )
    (comp (ref "RAM_LED_2")
      (value "LED3MM")
      (footprint "eagle-import:LED3MM")
      (libsource (lib "eagle-import") (part "LED3MM"))
    )
    (comp (ref "RAM_LED_3")
      (value "LED3MM")
      (footprint "eagle-import:LED3MM")
      (libsource (lib "eagle-import") (part "LED3MM"))
    )
    (comp (ref "RAM_LED_4")
      (value "LED3MM")
      (footprint "eagle-import:LED3MM")
      (libsource (lib "eagle-import") (part "LED3MM"))
    )
    (comp (ref "RAM_LED_5")
      (value "LED3MM")
      (footprint "eagle-import:LED3MM")
      (libsource (lib "eagle-import") (part "LED3MM"))
    )
    (comp (ref "RAM_LED_6")
      (value "LED3MM")
      (footprint "eagle-import:LED3MM")
      (libsource (lib "eagle-import") (part "LED3MM"))
    )
    (comp (ref "RAM_LED_7")
      (value "LED3MM")
      (footprint "eagle-import:LED3MM")
      (libsource (lib "eagle-import") (part "LED3MM"))
    )
    (comp (ref "RAM_LED_8")
      (value "LED3MM")
      (footprint "eagle-import:LED3MM")
      (libsource (lib "eagle-import") (part "LED3MM"))
    )
    (comp (ref "REG_A_LOWER")
      (value "74LS173N")
      (footprint "eagle-import:DIL16")
      (libsource (lib "eagle-import") (part "74173NLS"))
    )
    (comp (ref "REG_A_UPPER")
      (value "74LS173N")
      (footprint "eagle-import:DIL16")
      (libsource (lib "eagle-import") (part "74173NLS"))
    )
    (comp (ref "REG_CALC_LOWER")
      (value "74LS173N")
      (footprint "eagle-import:DIL16")
      (libsource (lib "eagle-import") (part "74173NLS"))
    )
    (comp (ref "REG_CALC_UPPER")
      (value "74LS173N")
      (footprint "eagle-import:DIL16")
      (libsource (lib "eagle-import") (part "74173NLS"))
    )
    (comp (ref "REG_PARAM_LOWER")
      (value "74LS173N")
      (footprint "eagle-import:DIL16")
      (libsource (lib "eagle-import") (part "74173NLS"))
    )
    (comp (ref "REG_PARAM_UPPER")
      (value "74LS173N")
      (footprint "eagle-import:DIL16")
      (libsource (lib "eagle-import") (part "74173NLS"))
    )
    (comp (ref "RESET_PC")
      (value "NORM-OFF")
      (footprint "eagle-import:B3F-10XX")
      (fields (field (name "MPN") "B3F-1000"))
      (libsource (lib "eagle-import") (part "10-XX"))
    )
    (comp (ref "RESET_REGS")
      (value "NORM-OFF")
      (footprint "eagle-import:B3F-10XX")
      (fields (field (name "MPN") "B3F-1000"))
      (libsource (lib "eagle-import") (part "10-XX"))
    )
    (comp (ref "SELECTOR_BRANCH_")
      (value "74HC139N")
      (footprint "eagle-import:DIL16")
      (libsource (lib "eagle-import") (part "74139NHC"))
    )
    (comp (ref "SELECTOR_INSRUCTION_LOWER")
      (value "74LS157N")
      (footprint "eagle-import:DIL16")
      (libsource (lib "eagle-import") (part "74157NLS"))
    )
    (comp (ref "SELECTOR_INSRUCTION_UPPER")
      (value "74LS157N")
      (footprint "eagle-import:DIL16")
      (libsource (lib "eagle-import") (part "74157NLS"))
    )
    (comp (ref "SELECTOR_LOGIC_")
      (value "74HC139N")
      (footprint "eagle-import:DIL16")
      (libsource (lib "eagle-import") (part "74139NHC"))
    )
    (comp (ref "SELECTOR_PARAM_")
      (value "74LS139N")
      (footprint "eagle-import:DIL16")
      (libsource (lib "eagle-import") (part "74139NLS"))
    )
    (comp (ref "SELECTOR_STACK_")
      (value "74LS139N")
      (footprint "eagle-import:DIL16")
      (libsource (lib "eagle-import") (part "74139NLS"))
    )
    (comp (ref "STEPPER_CLOCK")
      (value "NE555N")
      (footprint "eagle-import:DIL08")
      (libsource (lib "eagle-import") (part "555NNE"))
    )
    (comp (ref "SUBTRACT_INVRTR_LOWER_")
      (value "74LS86N")
      (footprint "eagle-import:DIL14")
      (libsource (lib "eagle-import") (part "7486NLS"))
    )
    (comp (ref "SUBTRACT_INVRTR_UPPER_")
      (value "74LS86N")
      (footprint "eagle-import:DIL14")
      (libsource (lib "eagle-import") (part "7486NLS"))
    )
    (comp (ref "USTEP_1")
      (value "LED")
      (footprint "eagle-import:LED5MM")
      (libsource (lib "eagle-import") (part "LED5MM"))
    )
    (comp (ref "USTEP_2")
      (value "LED")
      (footprint "eagle-import:LED5MM")
      (libsource (lib "eagle-import") (part "LED5MM"))
    )
    (comp (ref "USTEP_3")
      (value "LED")
      (footprint "eagle-import:LED5MM")
      (libsource (lib "eagle-import") (part "LED5MM"))
    )
    (comp (ref "USTEP_4")
      (value "LED")
      (footprint "eagle-import:LED5MM")
      (libsource (lib "eagle-import") (part "LED5MM"))
    )
    (comp (ref "USTEP_5")
      (value "LED")
      (footprint "eagle-import:LED5MM")
      (libsource (lib "eagle-import") (part "LED5MM"))
    )
    (comp (ref "X1")
      (value "SSW-103-02-G-S")
      (footprint "eagle-import:SSW-103-02-G-S")
      (fields (field (name "MF") "Samtec Inc."))
      (libsource (lib "eagle-import") (part "SSW-103-02-G-S"))
    )
    (comp (ref "XOR_GATE_1")
      (value "74LS86N")
      (footprint "eagle-import:DIL14")
      (libsource (lib "eagle-import") (part "7486NLS"))
    )
    (comp (ref "XOR_GATE_2")
      (value "74LS86N")
      (footprint "eagle-import:DIL14")
      (libsource (lib "eagle-import") (part "7486NLS"))
    )
    (comp (ref "ZERO_FLAG")
      (value "220")
      (footprint "eagle-import:LED5MM")
      (libsource (lib "eagle-import") (part "LED5MM"))
    )
    (comp (ref "ZERO_POS_FLAG_IDENTIFIER")
      (value "744078N")
      (footprint "eagle-import:DIL14")
      (libsource (lib "eagle-import") (part "744078N"))
    )
  )
  (nets
    (net (code "1") (name "GND") (class "Default")
      (node (ref "4_INP_OR_GATE") (pin "7") (pinfunction "VSS_7") (pintype "power_in"))
      (node (ref "ADDR_MEM_REG_LOWER") (pin "1") (pinfunction "M_1") (pintype "input"))
      (node (ref "ADDR_MEM_REG_LOWER") (pin "2") (pinfunction "N_2") (pintype "input"))
      (node (ref "ADDR_MEM_REG_UPPER") (pin "1") (pinfunction "M_1") (pintype "input"))
      (node (ref "ADDR_MEM_REG_UPPER") (pin "2") (pinfunction "N_2") (pintype "input"))
      (node (ref "AUTO_CLOCK") (pin "1") (pinfunction "GND_1") (pintype "power_in"))
      (node (ref "C1") (pin "-") (pinfunction "-_-") (pintype "passive"))
      (node (ref "C2") (pin "-") (pinfunction "-_-") (pintype "passive"))
      (node (ref "C3") (pin "-") (pinfunction "-_-") (pintype "passive"))
      (node (ref "C4") (pin "-") (pinfunction "-_-") (pintype "passive"))
      (node (ref "CLK_TRIGGER") (pin "3") (pinfunction "P_3") (pintype "passive"))
      (node (ref "EXTENSION") (pin "11") (pinfunction "1_11") (pintype "passive"))
      (node (ref "FLAG_REG_LOWER") (pin "1") (pinfunction "M_1") (pintype "input"))
      (node (ref "FLAG_REG_LOWER") (pin "2") (pinfunction "N_2") (pintype "input"))
      (node (ref "FLAG_REG_UPPER") (pin "1") (pinfunction "M_1") (pintype "input"))
      (node (ref "FLAG_REG_UPPER") (pin "2") (pinfunction "N_2") (pintype "input"))
      (node (ref "INSTRUCTIONS_EXTENSION") (pin "15") (pinfunction "1_15") (pintype "passive"))
      (node (ref "INSTRUCTION_MEMORY_0") (pin "14") (pinfunction "14_14") (pintype "passive"))
      (node (ref "INSTRUCTION_MEMORY_0") (pin "20") (pinfunction "20_20") (pintype "passive"))
      (node (ref "INSTRUCTION_MEMORY_0") (pin "22") (pinfunction "22_22") (pintype "passive"))
      (node (ref "INSTRUCTION_MEMORY_1") (pin "14") (pinfunction "14_14") (pintype "passive"))
      (node (ref "INSTRUCTION_MEMORY_1") (pin "20") (pinfunction "20_20") (pintype "passive"))
      (node (ref "INSTRUCTION_MEMORY_1") (pin "22") (pinfunction "22_22") (pintype "passive"))
      (node (ref "INSTRUCTION_MEMORY_2") (pin "14") (pinfunction "14_14") (pintype "passive"))
      (node (ref "INSTRUCTION_MEMORY_2") (pin "20") (pinfunction "20_20") (pintype "passive"))
      (node (ref "INSTRUCTION_MEMORY_2") (pin "22") (pinfunction "22_22") (pintype "passive"))
      (node (ref "INSTRUC_REGISTER_LOWER") (pin "1") (pinfunction "M_1") (pintype "input"))
      (node (ref "INSTRUC_REGISTER_LOWER") (pin "2") (pinfunction "N_2") (pintype "input"))
      (node (ref "INSTRUC_REGISTER_UPPER") (pin "1") (pinfunction "M_1") (pintype "input"))
      (node (ref "INSTRUC_REGISTER_UPPER") (pin "2") (pinfunction "N_2") (pintype "input"))
      (node (ref "KEYBOARD") (pin "4") (pinfunction "1_4") (pintype "passive"))
      (node (ref "KEYBOARD_ASCII_TABLE") (pin "14") (pinfunction "14_14") (pintype "passive"))
      (node (ref "KEYBOARD_ASCII_TABLE") (pin "2") (pinfunction "2_2") (pintype "passive"))
      (node (ref "KEYBOARD_ASCII_TABLE") (pin "20") (pinfunction "20_20") (pintype "passive"))
      (node (ref "KEYBOARD_ASCII_TABLE") (pin "21") (pinfunction "21_21") (pintype "passive"))
      (node (ref "KEYBOARD_ASCII_TABLE") (pin "22") (pinfunction "22_22") (pintype "passive"))
      (node (ref "KEYBOARD_ASCII_TABLE") (pin "23") (pinfunction "23_23") (pintype "passive"))
      (node (ref "KEYBOARD_ASCII_TABLE") (pin "24") (pinfunction "24_24") (pintype "passive"))
      (node (ref "KEYBOARD_ASCII_TABLE") (pin "25") (pinfunction "25_25") (pintype "passive"))
      (node (ref "KEYBOARD_SHIFT_LOWER") (pin "13") (pinfunction "G_13") (pintype "input"))
      (node (ref "KEYBOARD_SHIFT_UPPER") (pin "13") (pinfunction "G_13") (pintype "input"))
      (node (ref "MEMORY") (pin "14") (pinfunction "14_14") (pintype "passive"))
      (node (ref "MEMORY") (pin "2") (pinfunction "2_2") (pintype "passive"))
      (node (ref "MEMORY") (pin "20") (pinfunction "20_20") (pintype "passive"))
      (node (ref "MEMORY") (pin "21") (pinfunction "21_21") (pintype "passive"))
      (node (ref "MEMORY") (pin "22") (pinfunction "22_22") (pintype "passive"))
      (node (ref "MEMORY") (pin "23") (pinfunction "23_23") (pintype "passive"))
      (node (ref "MEMORY") (pin "24") (pinfunction "24_24") (pintype "passive"))
      (node (ref "MICRO_COUNTER_LOWER") (pin "8") (pinfunction "8_8") (pintype "passive"))
      (node (ref "MICRO_COUNTER_UPPER") (pin "8") (pinfunction "8_8") (pintype "passive"))
      (node (ref "OUTPUT_BUFFER_ALU") (pin "1") (pinfunction "DIR_1") (pintype "input"))
      (node (ref "OUTPUT_BUFFER_FLAGS") (pin "1") (pinfunction "DIR_1") (pintype "input"))
      (node (ref "OUTPUT_BUFFER_KEYBOARD") (pin "1") (pinfunction "DIR_1") (pintype "input"))
      (node (ref "OUT_REG_LOWER") (pin "1") (pinfunction "M_1") (pintype "input"))
      (node (ref "OUT_REG_LOWER") (pin "2") (pinfunction "N_2") (pintype "input"))
      (node (ref "OUT_REG_UPPER") (pin "1") (pinfunction "M_1") (pintype "input"))
      (node (ref "OUT_REG_UPPER") (pin "2") (pinfunction "N_2") (pintype "input"))
      (node (ref "OUT_ROM_LOWER") (pin "14") (pinfunction "14_14") (pintype "passive"))
      (node (ref "OUT_ROM_LOWER") (pin "2") (pinfunction "2_2") (pintype "passive"))
      (node (ref "OUT_ROM_LOWER") (pin "20") (pinfunction "20_20") (pintype "passive"))
      (node (ref "OUT_ROM_LOWER") (pin "21") (pinfunction "21_21") (pintype "passive"))
      (node (ref "OUT_ROM_LOWER") (pin "22") (pinfunction "22_22") (pintype "passive"))
      (node (ref "OUT_ROM_LOWER") (pin "23") (pinfunction "23_23") (pintype "passive"))
      (node (ref "OUT_ROM_LOWER") (pin "24") (pinfunction "24_24") (pintype "passive"))
      (node (ref "OUT_ROM_LOWER") (pin "25") (pinfunction "25_25") (pintype "passive"))
      (node (ref "OUT_ROM_LOWER") (pin "3") (pinfunction "3_3") (pintype "passive"))
      (node (ref "OUT_ROM_LOWER") (pin "4") (pinfunction "4_4") (pintype "passive"))
      (node (ref "OUT_ROM_LOWER") (pin "5") (pinfunction "5_5") (pintype "passive"))
      (node (ref "OUT_ROM_LOWER") (pin "6") (pinfunction "6_6") (pintype "passive"))
      (node (ref "OUT_ROM_UPPER") (pin "14") (pinfunction "14_14") (pintype "passive"))
      (node (ref "OUT_ROM_UPPER") (pin "2") (pinfunction "2_2") (pintype "passive"))
      (node (ref "OUT_ROM_UPPER") (pin "20") (pinfunction "20_20") (pintype "passive"))
      (node (ref "OUT_ROM_UPPER") (pin "21") (pinfunction "21_21") (pintype "passive"))
      (node (ref "OUT_ROM_UPPER") (pin "22") (pinfunction "22_22") (pintype "passive"))
      (node (ref "OUT_ROM_UPPER") (pin "23") (pinfunction "23_23") (pintype "passive"))
      (node (ref "OUT_ROM_UPPER") (pin "24") (pinfunction "24_24") (pintype "passive"))
      (node (ref "OUT_ROM_UPPER") (pin "25") (pinfunction "25_25") (pintype "passive"))
      (node (ref "OUT_ROM_UPPER") (pin "3") (pinfunction "3_3") (pintype "passive"))
      (node (ref "OUT_ROM_UPPER") (pin "4") (pinfunction "4_4") (pintype "passive"))
      (node (ref "OUT_ROM_UPPER") (pin "5") (pinfunction "5_5") (pintype "passive"))
      (node (ref "OUT_ROM_UPPER") (pin "6") (pinfunction "6_6") (pintype "passive"))
      (node (ref "OUT_SEGMENT_LOWER") (pin "3") (pinfunction "CK1_3") (pintype "passive"))
      (node (ref "OUT_SEGMENT_LOWER") (pin "8") (pinfunction "CK2_8") (pintype "passive"))
      (node (ref "OUT_SEGMENT_UPPER") (pin "3") (pinfunction "CK1_3") (pintype "passive"))
      (node (ref "OUT_SEGMENT_UPPER") (pin "8") (pinfunction "CK2_8") (pintype "passive"))
      (node (ref "PROGRAM_COUNTER_LOWER") (pin "8") (pinfunction "8_8") (pintype "passive"))
      (node (ref "PROGRAM_COUNTER_UPPER") (pin "8") (pinfunction "8_8") (pintype "passive"))
      (node (ref "R10") (pin "1") (pinfunction "1_1") (pintype "passive"))
      (node (ref "R11") (pin "1") (pinfunction "1_1") (pintype "passive"))
      (node (ref "R12") (pin "1") (pinfunction "1_1") (pintype "passive"))
      (node (ref "R13") (pin "1") (pinfunction "1_1") (pintype "passive"))
      (node (ref "R14") (pin "1") (pinfunction "1_1") (pintype "passive"))
      (node (ref "R15") (pin "1") (pinfunction "1_1") (pintype "passive"))
      (node (ref "R16") (pin "2") (pinfunction "2_2") (pintype "passive"))
      (node (ref "R17") (pin "2") (pinfunction "2_2") (pintype "passive"))
      (node (ref "R18") (pin "2") (pinfunction "2_2") (pintype "passive"))
      (node (ref "R19") (pin "2") (pinfunction "2_2") (pintype "passive"))
      (node (ref "R20") (pin "2") (pinfunction "2_2") (pintype "passive"))
      (node (ref "R21") (pin "2") (pinfunction "2_2") (pintype "passive"))
      (node (ref "R22") (pin "2") (pinfunction "2_2") (pintype "passive"))
      (node (ref "R23") (pin "2") (pinfunction "2_2") (pintype "passive"))
      (node (ref "R24") (pin "2") (pinfunction "2_2") (pintype "passive"))
      (node (ref "R25") (pin "2") (pinfunction "2_2") (pintype "passive"))
      (node (ref "R26") (pin "2") (pinfunction "2_2") (pintype "passive"))
      (node (ref "R27") (pin "2") (pinfunction "2_2") (pintype "passive"))
      (node (ref "R28") (pin "2") (pinfunction "2_2") (pintype "passive"))
      (node (ref "R29") (pin "2") (pinfunction "2_2") (pintype "passive"))
      (node (ref "R30") (pin "2") (pinfunction "2_2") (pintype "passive"))
      (node (ref "R31") (pin "2") (pinfunction "2_2") (pintype "passive"))
      (node (ref "R32") (pin "2") (pinfunction "2_2") (pintype "passive"))
      (node (ref "R33") (pin "2") (pinfunction "2_2") (pintype "passive"))
      (node (ref "R34") (pin "2") (pinfunction "2_2") (pintype "passive"))
      (node (ref "R35") (pin "2") (pinfunction "2_2") (pintype "passive"))
      (node (ref "R36") (pin "2") (pinfunction "2_2") (pintype "passive"))
      (node (ref "R37") (pin "2") (pinfunction "2_2") (pintype "passive"))
      (node (ref "R38") (pin "2") (pinfunction "2_2") (pintype "passive"))
      (node (ref "R39") (pin "2") (pinfunction "2_2") (pintype "passive"))
      (node (ref "R4") (pin "1") (pinfunction "1_1") (pintype "passive"))
      (node (ref "R40") (pin "1") (pinfunction "1_1") (pintype "passive"))
      (node (ref "R41") (pin "1") (pinfunction "1_1") (pintype "passive"))
      (node (ref "R42") (pin "1") (pinfunction "1_1") (pintype "passive"))
      (node (ref "R43") (pin "1") (pinfunction "1_1") (pintype "passive"))
      (node (ref "R44") (pin "1") (pinfunction "1_1") (pintype "passive"))
      (node (ref "R45") (pin "1") (pinfunction "1_1") (pintype "passive"))
      (node (ref "R5") (pin "1") (pinfunction "1_1") (pintype "passive"))
      (node (ref "R53") (pin "2") (pinfunction "2_2") (pintype "passive"))
      (node (ref "R54") (pin "2") (pinfunction "2_2") (pintype "passive"))
      (node (ref "R55") (pin "2") (pinfunction "2_2") (pintype "passive"))
      (node (ref "R56") (pin "2") (pinfunction "2_2") (pintype "passive"))
      (node (ref "R57") (pin "2") (pinfunction "2_2") (pintype "passive"))
      (node (ref "R58") (pin "2") (pinfunction "2_2") (pintype "passive"))
      (node (ref "R59") (pin "2") (pinfunction "2_2") (pintype "passive"))
      (node (ref "R60") (pin "2") (pinfunction "2_2") (pintype "passive"))
      (node (ref "R61") (pin "2") (pinfunction "2_2") (pintype "passive"))
      (node (ref "R62") (pin "2") (pinfunction "2_2") (pintype "passive"))
      (node (ref "R63") (pin "2") (pinfunction "2_2") (pintype "passive"))
      (node (ref "R64") (pin "2") (pinfunction "2_2") (pintype "passive"))
      (node (ref "R65") (pin "2") (pinfunction "2_2") (pintype "passive"))
      (node (ref "R66") (pin "2") (pinfunction "2_2") (pintype "passive"))
      (node (ref "R67") (pin "2") (pinfunction "2_2") (pintype "passive"))
      (node (ref "R68") (pin "2") (pinfunction "2_2") (pintype "passive"))
      (node (ref "R69") (pin "2") (pinfunction "2_2") (pintype "passive"))
      (node (ref "R70") (pin "2") (pinfunction "2_2") (pintype "passive"))
      (node (ref "R71") (pin "2") (pinfunction "2_2") (pintype "passive"))
      (node (ref "R72") (pin "2") (pinfunction "2_2") (pintype "passive"))
      (node (ref "R73") (pin "2") (pinfunction "2_2") (pintype "passive"))
      (node (ref "R74") (pin "2") (pinfunction "2_2") (pintype "passive"))
      (node (ref "R75") (pin "2") (pinfunction "2_2") (pintype "passive"))
      (node (ref "R76") (pin "2") (pinfunction "2_2") (pintype "passive"))
      (node (ref "R77") (pin "1") (pinfunction "1_1") (pintype "passive"))
      (node (ref "R78") (pin "1") (pinfunction "1_1") (pintype "passive"))
      (node (ref "R79") (pin "1") (pinfunction "1_1") (pintype "passive"))
      (node (ref "R8") (pin "1") (pinfunction "1_1") (pintype "passive"))
      (node (ref "R81") (pin "2") (pinfunction "2_2") (pintype "passive"))
      (node (ref "R9") (pin "1") (pinfunction "1_1") (pintype "passive"))
      (node (ref "RAM") (pin "1") (pinfunction "1_1") (pintype "passive"))
      (node (ref "RAM") (pin "14") (pinfunction "14_14") (pintype "passive"))
      (node (ref "RAM") (pin "2") (pinfunction "2_2") (pintype "passive"))
      (node (ref "RAM") (pin "20") (pinfunction "20_20") (pintype "passive"))
      (node (ref "RAM") (pin "21") (pinfunction "21_21") (pintype "passive"))
      (node (ref "RAM") (pin "23") (pinfunction "23_23") (pintype "passive"))
      (node (ref "RAM") (pin "24") (pinfunction "24_24") (pintype "passive"))
      (node (ref "RAM") (pin "25") (pinfunction "25_25") (pintype "passive"))
      (node (ref "RAM") (pin "26") (pinfunction "26_26") (pintype "passive"))
      (node (ref "RAM_ADDR_LOWER") (pin "1") (pinfunction "M_1") (pintype "input"))
      (node (ref "RAM_ADDR_LOWER") (pin "2") (pinfunction "N_2") (pintype "input"))
      (node (ref "RAM_ADDR_UPPER") (pin "1") (pinfunction "M_1") (pintype "input"))
      (node (ref "RAM_ADDR_UPPER") (pin "2") (pinfunction "N_2") (pintype "input"))
      (node (ref "REG_A_LOWER") (pin "1") (pinfunction "M_1") (pintype "input"))
      (node (ref "REG_A_LOWER") (pin "2") (pinfunction "N_2") (pintype "input"))
      (node (ref "REG_A_UPPER") (pin "1") (pinfunction "M_1") (pintype "input"))
      (node (ref "REG_A_UPPER") (pin "2") (pinfunction "N_2") (pintype "input"))
      (node (ref "REG_CALC_LOWER") (pin "1") (pinfunction "M_1") (pintype "input"))
      (node (ref "REG_CALC_LOWER") (pin "2") (pinfunction "N_2") (pintype "input"))
      (node (ref "REG_CALC_UPPER") (pin "1") (pinfunction "M_1") (pintype "input"))
      (node (ref "REG_CALC_UPPER") (pin "2") (pinfunction "N_2") (pintype "input"))
      (node (ref "REG_PARAM_LOWER") (pin "1") (pinfunction "M_1") (pintype "input"))
      (node (ref "REG_PARAM_LOWER") (pin "2") (pinfunction "N_2") (pintype "input"))
      (node (ref "REG_PARAM_UPPER") (pin "1") (pinfunction "M_1") (pintype "input"))
      (node (ref "REG_PARAM_UPPER") (pin "2") (pinfunction "N_2") (pintype "input"))
      (node (ref "RESET_PC") (pin "4") (pinfunction "P1_4") (pintype "passive"))
      (node (ref "SELECTOR_BRANCH_") (pin "1") (pinfunction "G_1") (pintype "input"))
      (node (ref "SELECTOR_BRANCH_") (pin "15") (pinfunction "G_15") (pintype "input"))
      (node (ref "SELECTOR_INSRUCTION_LOWER") (pin "11") (pinfunction "3A_11") (pintype "input"))
      (node (ref "SELECTOR_INSRUCTION_LOWER") (pin "14") (pinfunction "4A_14") (pintype "input"))
      (node (ref "SELECTOR_INSRUCTION_LOWER") (pin "15") (pinfunction "G_15") (pintype "input"))
      (node (ref "SELECTOR_INSRUCTION_LOWER") (pin "2") (pinfunction "1A_2") (pintype "input"))
      (node (ref "SELECTOR_INSRUCTION_LOWER") (pin "5") (pinfunction "2A_5") (pintype "input"))
      (node (ref "SELECTOR_INSRUCTION_UPPER") (pin "11") (pinfunction "3A_11") (pintype "input"))
      (node (ref "SELECTOR_INSRUCTION_UPPER") (pin "14") (pinfunction "4A_14") (pintype "input"))
      (node (ref "SELECTOR_INSRUCTION_UPPER") (pin "15") (pinfunction "G_15") (pintype "input"))
      (node (ref "SELECTOR_INSRUCTION_UPPER") (pin "2") (pinfunction "1A_2") (pintype "input"))
      (node (ref "SELECTOR_INSRUCTION_UPPER") (pin "5") (pinfunction "2A_5") (pintype "input"))
      (node (ref "SELECTOR_LOGIC_") (pin "1") (pinfunction "G_1") (pintype "input"))
      (node (ref "SELECTOR_LOGIC_") (pin "15") (pinfunction "G_15") (pintype "input"))
      (node (ref "SELECTOR_PARAM_") (pin "1") (pinfunction "G_1") (pintype "input"))
      (node (ref "SELECTOR_PARAM_") (pin "15") (pinfunction "G_15") (pintype "input"))
      (node (ref "SELECTOR_STACK_") (pin "1") (pinfunction "G_1") (pintype "input"))
      (node (ref "SELECTOR_STACK_") (pin "15") (pinfunction "G_15") (pintype "input"))
      (node (ref "STEPPER_CLOCK") (pin "1") (pinfunction "GND_1") (pintype "power_in"))
      (node (ref "X1") (pin "1") (pinfunction "1_1") (pintype "passive"))
      (node (ref "ZERO_POS_FLAG_IDENTIFIER") (pin "7") (pinfunction "-UB_7") (pintype "power_in"))
    )
    (net (code "2") (name "Net-(4_INP_OR_GATEA-I0)") (class "Default")
      (node (ref "4_INP_OR_GATE") (pin "2") (pinfunction "I0_2") (pintype "input"))
      (node (ref "NOT_GATE4_") (pin "2") (pinfunction "O_2") (pintype "output"))
    )
    (net (code "3") (name "Net-(4_INP_OR_GATEA-I1)") (class "Default")
      (node (ref "4_INP_OR_GATE") (pin "3") (pinfunction "I1_3") (pintype "input"))
      (node (ref "AND_GATE3_") (pin "11") (pinfunction "O_11") (pintype "output"))
    )
    (net (code "4") (name "Net-(4_INP_OR_GATEA-I2)") (class "Default")
      (node (ref "4_INP_OR_GATE") (pin "4") (pinfunction "I2_4") (pintype "input"))
      (node (ref "AND_GATE4_") (pin "3") (pinfunction "O_3") (pintype "output"))
    )
    (net (code "5") (name "Net-(4_INP_OR_GATEA-I3)") (class "Default")
      (node (ref "4_INP_OR_GATE") (pin "5") (pinfunction "I3_5") (pintype "input"))
      (node (ref "AND_GATE4_") (pin "6") (pinfunction "O_6") (pintype "output"))
    )
    (net (code "6") (name "Net-(4_INP_OR_GATEA-O)") (class "Default")
      (node (ref "4_INP_OR_GATE") (pin "1") (pinfunction "O_1") (pintype "output"))
      (node (ref "AND_GATE3_") (pin "1") (pinfunction "I0_1") (pintype "input"))
      (node (ref "AND_GATE3_") (pin "4") (pinfunction "I0_4") (pintype "input"))
    )
    (net (code "7") (name "Net-(ADDER_LOWERA-A1)") (class "Default")
      (node (ref "ADDER_LOWER") (pin "5") (pinfunction "A1_5") (pintype "input"))
      (node (ref "LED_A_REG_1") (pin "A") (pinfunction "A_A") (pintype "passive"))
      (node (ref "OUTPUT_BUFFER_REG_A") (pin "9") (pinfunction "A8_9") (pintype "bidirectional"))
      (node (ref "REG_A_LOWER") (pin "6") (pinfunction "Q4_6") (pintype "tri_state"))
      (node (ref "ZERO_POS_FLAG_IDENTIFIER") (pin "5") (pinfunction "D_5") (pintype "input"))
    )
    (net (code "8") (name "Net-(ADDER_LOWERA-A2)") (class "Default")
      (node (ref "ADDER_LOWER") (pin "3") (pinfunction "A2_3") (pintype "input"))
      (node (ref "LED_A_REG_2") (pin "A") (pinfunction "A_A") (pintype "passive"))
      (node (ref "OUTPUT_BUFFER_REG_A") (pin "8") (pinfunction "A7_8") (pintype "bidirectional"))
      (node (ref "REG_A_LOWER") (pin "5") (pinfunction "Q3_5") (pintype "tri_state"))
      (node (ref "ZERO_POS_FLAG_IDENTIFIER") (pin "4") (pinfunction "C_4") (pintype "input"))
    )
    (net (code "9") (name "Net-(ADDER_LOWERA-A3)") (class "Default")
      (node (ref "ADDER_LOWER") (pin "14") (pinfunction "A3_14") (pintype "input"))
      (node (ref "LED_A_REG_3") (pin "A") (pinfunction "A_A") (pintype "passive"))
      (node (ref "OUTPUT_BUFFER_REG_A") (pin "7") (pinfunction "A6_7") (pintype "bidirectional"))
      (node (ref "REG_A_LOWER") (pin "4") (pinfunction "Q2_4") (pintype "tri_state"))
      (node (ref "ZERO_POS_FLAG_IDENTIFIER") (pin "3") (pinfunction "B_3") (pintype "input"))
    )
    (net (code "10") (name "Net-(ADDER_LOWERA-A4)") (class "Default")
      (node (ref "ADDER_LOWER") (pin "12") (pinfunction "A4_12") (pintype "input"))
      (node (ref "LED_A_REG_4") (pin "A") (pinfunction "A_A") (pintype "passive"))
      (node (ref "OUTPUT_BUFFER_REG_A") (pin "6") (pinfunction "A5_6") (pintype "bidirectional"))
      (node (ref "REG_A_LOWER") (pin "3") (pinfunction "Q1_3") (pintype "tri_state"))
      (node (ref "ZERO_POS_FLAG_IDENTIFIER") (pin "2") (pinfunction "A_2") (pintype "input"))
    )
    (net (code "11") (name "Net-(ADDER_LOWERA-B1)") (class "Default")
      (node (ref "ADDER_LOWER") (pin "6") (pinfunction "B1_6") (pintype "input"))
      (node (ref "SUBTRACT_INVRTR_LOWER_") (pin "11") (pinfunction "O_11") (pintype "output"))
    )
    (net (code "12") (name "Net-(ADDER_LOWERA-B2)") (class "Default")
      (node (ref "ADDER_LOWER") (pin "2") (pinfunction "B2_2") (pintype "input"))
      (node (ref "SUBTRACT_INVRTR_LOWER_") (pin "8") (pinfunction "O_8") (pintype "output"))
    )
    (net (code "13") (name "Net-(ADDER_LOWERA-B3)") (class "Default")
      (node (ref "ADDER_LOWER") (pin "15") (pinfunction "B3_15") (pintype "input"))
      (node (ref "SUBTRACT_INVRTR_LOWER_") (pin "6") (pinfunction "O_6") (pintype "output"))
    )
    (net (code "14") (name "Net-(ADDER_LOWERA-B4)") (class "Default")
      (node (ref "ADDER_LOWER") (pin "11") (pinfunction "B4_11") (pintype "input"))
      (node (ref "SUBTRACT_INVRTR_LOWER_") (pin "3") (pinfunction "O_3") (pintype "output"))
    )
    (net (code "15") (name "Net-(ADDER_LOWERA-C0)") (class "Default")
      (node (ref "ADDER_LOWER") (pin "7") (pinfunction "C0_7") (pintype "input"))
      (node (ref "INSTRUCTION_MEMORY_1") (pin "15") (pinfunction "15_15") (pintype "passive"))
      (node (ref "SUBTRACT_INVRTR_LOWER_") (pin "1") (pinfunction "I0_1") (pintype "input"))
      (node (ref "SUBTRACT_INVRTR_LOWER_") (pin "12") (pinfunction "I0_12") (pintype "input"))
      (node (ref "SUBTRACT_INVRTR_LOWER_") (pin "4") (pinfunction "I0_4") (pintype "input"))
      (node (ref "SUBTRACT_INVRTR_LOWER_") (pin "9") (pinfunction "I0_9") (pintype "input"))
      (node (ref "SUBTRACT_INVRTR_UPPER_") (pin "1") (pinfunction "I0_1") (pintype "input"))
      (node (ref "SUBTRACT_INVRTR_UPPER_") (pin "12") (pinfunction "I0_12") (pintype "input"))
      (node (ref "SUBTRACT_INVRTR_UPPER_") (pin "4") (pinfunction "I0_4") (pintype "input"))
      (node (ref "SUBTRACT_INVRTR_UPPER_") (pin "9") (pinfunction "I0_9") (pintype "input"))
    )
    (net (code "16") (name "Net-(ADDER_LOWERA-C4)") (class "Default")
      (node (ref "ADDER_LOWER") (pin "9") (pinfunction "C4_9") (pintype "output"))
      (node (ref "ADDER_UPPER") (pin "7") (pinfunction "C0_7") (pintype "input"))
    )
    (net (code "17") (name "Net-(ADDER_LOWERA-S1)") (class "Default")
      (node (ref "ADDER_LOWER") (pin "4") (pinfunction "S1_4") (pintype "output"))
      (node (ref "OUTPUT_BUFFER_ALU") (pin "18") (pinfunction "B1_18") (pintype "bidirectional"))
    )
    (net (code "18") (name "Net-(ADDER_LOWERA-S2)") (class "Default")
      (node (ref "ADDER_LOWER") (pin "1") (pinfunction "S2_1") (pintype "output"))
      (node (ref "OUTPUT_BUFFER_ALU") (pin "17") (pinfunction "B2_17") (pintype "bidirectional"))
    )
    (net (code "19") (name "Net-(ADDER_LOWERA-S3)") (class "Default")
      (node (ref "ADDER_LOWER") (pin "13") (pinfunction "S3_13") (pintype "output"))
      (node (ref "OUTPUT_BUFFER_ALU") (pin "16") (pinfunction "B3_16") (pintype "bidirectional"))
    )
    (net (code "20") (name "Net-(ADDER_LOWERA-S4)") (class "Default")
      (node (ref "ADDER_LOWER") (pin "10") (pinfunction "S4_10") (pintype "output"))
      (node (ref "OUTPUT_BUFFER_ALU") (pin "15") (pinfunction "B4_15") (pintype "bidirectional"))
    )
    (net (code "21") (name "Net-(ADDER_UPPERA-A1)") (class "Default")
      (node (ref "ADDER_UPPER") (pin "5") (pinfunction "A1_5") (pintype "input"))
      (node (ref "LED_A_REG_5") (pin "A") (pinfunction "A_A") (pintype "passive"))
      (node (ref "OUTPUT_BUFFER_REG_A") (pin "5") (pinfunction "A4_5") (pintype "bidirectional"))
      (node (ref "REG_A_UPPER") (pin "6") (pinfunction "Q4_6") (pintype "tri_state"))
      (node (ref "ZERO_POS_FLAG_IDENTIFIER") (pin "9") (pinfunction "E_9") (pintype "input"))
    )
    (net (code "22") (name "Net-(ADDER_UPPERA-A2)") (class "Default")
      (node (ref "ADDER_UPPER") (pin "3") (pinfunction "A2_3") (pintype "input"))
      (node (ref "LED_A_REG_6") (pin "A") (pinfunction "A_A") (pintype "passive"))
      (node (ref "OUTPUT_BUFFER_REG_A") (pin "4") (pinfunction "A3_4") (pintype "bidirectional"))
      (node (ref "REG_A_UPPER") (pin "5") (pinfunction "Q3_5") (pintype "tri_state"))
      (node (ref "ZERO_POS_FLAG_IDENTIFIER") (pin "10") (pinfunction "F_10") (pintype "input"))
    )
    (net (code "23") (name "Net-(ADDER_UPPERA-A3)") (class "Default")
      (node (ref "ADDER_UPPER") (pin "14") (pinfunction "A3_14") (pintype "input"))
      (node (ref "LED_A_REG_7") (pin "A") (pinfunction "A_A") (pintype "passive"))
      (node (ref "OUTPUT_BUFFER_REG_A") (pin "3") (pinfunction "A2_3") (pintype "bidirectional"))
      (node (ref "REG_A_UPPER") (pin "4") (pinfunction "Q2_4") (pintype "tri_state"))
      (node (ref "ZERO_POS_FLAG_IDENTIFIER") (pin "11") (pinfunction "G_11") (pintype "input"))
    )
    (net (code "24") (name "Net-(ADDER_UPPERA-A4)") (class "Default")
      (node (ref "ADDER_UPPER") (pin "12") (pinfunction "A4_12") (pintype "input"))
      (node (ref "LED_A_REG_8") (pin "A") (pinfunction "A_A") (pintype "passive"))
      (node (ref "OUTPUT_BUFFER_REG_A") (pin "2") (pinfunction "A1_2") (pintype "bidirectional"))
      (node (ref "REG_A_UPPER") (pin "3") (pinfunction "Q1_3") (pintype "tri_state"))
      (node (ref "ZERO_POS_FLAG_IDENTIFIER") (pin "12") (pinfunction "H_12") (pintype "input"))
    )
    (net (code "25") (name "Net-(ADDER_UPPERA-B1)") (class "Default")
      (node (ref "ADDER_UPPER") (pin "6") (pinfunction "B1_6") (pintype "input"))
      (node (ref "SUBTRACT_INVRTR_UPPER_") (pin "11") (pinfunction "O_11") (pintype "output"))
    )
    (net (code "26") (name "Net-(ADDER_UPPERA-B2)") (class "Default")
      (node (ref "ADDER_UPPER") (pin "2") (pinfunction "B2_2") (pintype "input"))
      (node (ref "SUBTRACT_INVRTR_UPPER_") (pin "8") (pinfunction "O_8") (pintype "output"))
    )
    (net (code "27") (name "Net-(ADDER_UPPERA-B3)") (class "Default")
      (node (ref "ADDER_UPPER") (pin "15") (pinfunction "B3_15") (pintype "input"))
      (node (ref "SUBTRACT_INVRTR_UPPER_") (pin "6") (pinfunction "O_6") (pintype "output"))
    )
    (net (code "28") (name "Net-(ADDER_UPPERA-B4)") (class "Default")
      (node (ref "ADDER_UPPER") (pin "11") (pinfunction "B4_11") (pintype "input"))
      (node (ref "SUBTRACT_INVRTR_UPPER_") (pin "3") (pinfunction "O_3") (pintype "output"))
    )
    (net (code "29") (name "Net-(ADDER_UPPERA-C4)") (class "Default")
      (node (ref "ADDER_UPPER") (pin "9") (pinfunction "C4_9") (pintype "output"))
      (node (ref "AND_GATE3_") (pin "13") (pinfunction "I1_13") (pintype "input"))
      (node (ref "FLAG_REG_LOWER") (pin "14") (pinfunction "D1_14") (pintype "input"))
      (node (ref "OVERFLOW_FLAG") (pin "A") (pinfunction "A_A") (pintype "passive"))
    )
    (net (code "30") (name "Net-(ADDER_UPPERA-S1)") (class "Default")
      (node (ref "ADDER_UPPER") (pin "4") (pinfunction "S1_4") (pintype "output"))
      (node (ref "OUTPUT_BUFFER_ALU") (pin "14") (pinfunction "B5_14") (pintype "bidirectional"))
    )
    (net (code "31") (name "Net-(ADDER_UPPERA-S2)") (class "Default")
      (node (ref "ADDER_UPPER") (pin "1") (pinfunction "S2_1") (pintype "output"))
      (node (ref "OUTPUT_BUFFER_ALU") (pin "13") (pinfunction "B6_13") (pintype "bidirectional"))
    )
    (net (code "32") (name "Net-(ADDER_UPPERA-S3)") (class "Default")
      (node (ref "ADDER_UPPER") (pin "13") (pinfunction "S3_13") (pintype "output"))
      (node (ref "OUTPUT_BUFFER_ALU") (pin "12") (pinfunction "B7_12") (pintype "bidirectional"))
    )
    (net (code "33") (name "Net-(ADDER_UPPERA-S4)") (class "Default")
      (node (ref "ADDER_UPPER") (pin "10") (pinfunction "S4_10") (pintype "output"))
      (node (ref "OUTPUT_BUFFER_ALU") (pin "11") (pinfunction "B8_11") (pintype "bidirectional"))
    )
    (net (code "34") (name "Net-(ADDR_MEM_REG_LOWERA-CLK)") (class "Default")
      (node (ref "ADDR_MEM_REG_LOWER") (pin "7") (pinfunction "CLK_7") (pintype "input"))
      (node (ref "ADDR_MEM_REG_UPPER") (pin "7") (pinfunction "CLK_7") (pintype "input"))
      (node (ref "AND_GATE_") (pin "8") (pinfunction "O_8") (pintype "output"))
      (node (ref "CLOCK") (pin "A") (pinfunction "A_A") (pintype "passive"))
      (node (ref "EXTENSION") (pin "9") (pinfunction "1_9") (pintype "passive"))
      (node (ref "FLAG_REG_LOWER") (pin "7") (pinfunction "CLK_7") (pintype "input"))
      (node (ref "FLAG_REG_UPPER") (pin "7") (pinfunction "CLK_7") (pintype "input"))
      (node (ref "INSTRUC_REGISTER_LOWER") (pin "7") (pinfunction "CLK_7") (pintype "input"))
      (node (ref "INSTRUC_REGISTER_UPPER") (pin "7") (pinfunction "CLK_7") (pintype "input"))
      (node (ref "NOT_GATE1_") (pin "11") (pinfunction "I_11") (pintype "input"))
      (node (ref "OUT_REG_LOWER") (pin "7") (pinfunction "CLK_7") (pintype "input"))
      (node (ref "OUT_REG_UPPER") (pin "7") (pinfunction "CLK_7") (pintype "input"))
      (node (ref "PROGRAM_COUNTER_LOWER") (pin "2") (pinfunction "2_2") (pintype "passive"))
      (node (ref "PROGRAM_COUNTER_UPPER") (pin "2") (pinfunction "2_2") (pintype "passive"))
      (node (ref "RAM_ADDR_LOWER") (pin "7") (pinfunction "CLK_7") (pintype "input"))
      (node (ref "RAM_ADDR_UPPER") (pin "7") (pinfunction "CLK_7") (pintype "input"))
      (node (ref "REG_A_LOWER") (pin "7") (pinfunction "CLK_7") (pintype "input"))
      (node (ref "REG_A_UPPER") (pin "7") (pinfunction "CLK_7") (pintype "input"))
      (node (ref "REG_CALC_LOWER") (pin "7") (pinfunction "CLK_7") (pintype "input"))
      (node (ref "REG_CALC_UPPER") (pin "7") (pinfunction "CLK_7") (pintype "input"))
      (node (ref "REG_PARAM_LOWER") (pin "7") (pinfunction "CLK_7") (pintype "input"))
      (node (ref "REG_PARAM_UPPER") (pin "7") (pinfunction "CLK_7") (pintype "input"))
    )
    (net (code "35") (name "Net-(ADDR_MEM_REG_LOWERA-CLR)") (class "Default")
      (node (ref "ADDR_MEM_REG_LOWER") (pin "15") (pinfunction "CLR_15") (pintype "input"))
      (node (ref "ADDR_MEM_REG_UPPER") (pin "15") (pinfunction "CLR_15") (pintype "input"))
      (node (ref "FLAG_REG_LOWER") (pin "15") (pinfunction "CLR_15") (pintype "input"))
      (node (ref "FLAG_REG_UPPER") (pin "15") (pinfunction "CLR_15") (pintype "input"))
      (node (ref "INSTRUC_REGISTER_LOWER") (pin "15") (pinfunction "CLR_15") (pintype "input"))
      (node (ref "INSTRUC_REGISTER_UPPER") (pin "15") (pinfunction "CLR_15") (pintype "input"))
      (node (ref "OUT_REG_LOWER") (pin "15") (pinfunction "CLR_15") (pintype "input"))
      (node (ref "OUT_REG_UPPER") (pin "15") (pinfunction "CLR_15") (pintype "input"))
      (node (ref "R81") (pin "1") (pinfunction "1_1") (pintype "passive"))
      (node (ref "RAM_ADDR_LOWER") (pin "15") (pinfunction "CLR_15") (pintype "input"))
      (node (ref "RAM_ADDR_UPPER") (pin "15") (pinfunction "CLR_15") (pintype "input"))
      (node (ref "REG_A_LOWER") (pin "15") (pinfunction "CLR_15") (pintype "input"))
      (node (ref "REG_A_UPPER") (pin "15") (pinfunction "CLR_15") (pintype "input"))
      (node (ref "REG_CALC_LOWER") (pin "15") (pinfunction "CLR_15") (pintype "input"))
      (node (ref "REG_CALC_UPPER") (pin "15") (pinfunction "CLR_15") (pintype "input"))
      (node (ref "REG_PARAM_LOWER") (pin "15") (pinfunction "CLR_15") (pintype "input"))
      (node (ref "REG_PARAM_UPPER") (pin "15") (pinfunction "CLR_15") (pintype "input"))
      (node (ref "RESET_REGS") (pin "4") (pinfunction "P1_4") (pintype "passive"))
    )
    (net (code "36") (name "Net-(ADDR_MEM_REG_LOWERA-D1)") (class "Default")
      (node (ref "ADDR_MEM_REG_LOWER") (pin "14") (pinfunction "D1_14") (pintype "input"))
      (node (ref "DATABUS_4") (pin "A") (pinfunction "A_A") (pintype "passive"))
      (node (ref "EXTENSION") (pin "4") (pinfunction "1_4") (pintype "passive"))
      (node (ref "INSTRUC_REGISTER_LOWER") (pin "14") (pinfunction "D1_14") (pintype "input"))
      (node (ref "MICRO_COUNTER_LOWER") (pin "6") (pinfunction "6_6") (pintype "passive"))
      (node (ref "OUTPUT_BUFFER_ALU") (pin "5") (pinfunction "A4_5") (pintype "bidirectional"))
      (node (ref "OUTPUT_BUFFER_CALC_REG") (pin "14") (pinfunction "B5_14") (pintype "bidirectional"))
      (node (ref "OUTPUT_BUFFER_FLAGS") (pin "5") (pinfunction "A4_5") (pintype "bidirectional"))
      (node (ref "OUTPUT_BUFFER_INSTRUCTION") (pin "14") (pinfunction "B5_14") (pintype "bidirectional"))
      (node (ref "OUTPUT_BUFFER_KEYBOARD") (pin "5") (pinfunction "A4_5") (pintype "bidirectional"))
      (node (ref "OUTPUT_BUFFER_MEMORY") (pin "14") (pinfunction "B5_14") (pintype "bidirectional"))
      (node (ref "OUTPUT_BUFFER_PARAM_REG") (pin "14") (pinfunction "B5_14") (pintype "bidirectional"))
      (node (ref "OUTPUT_BUFFER_PC") (pin "14") (pinfunction "B5_14") (pintype "bidirectional"))
      (node (ref "OUTPUT_BUFFER_RAM") (pin "15") (pinfunction "B4_15") (pintype "bidirectional"))
      (node (ref "OUTPUT_BUFFER_REG_A") (pin "14") (pinfunction "B5_14") (pintype "bidirectional"))
      (node (ref "OUT_REG_LOWER") (pin "14") (pinfunction "D1_14") (pintype "input"))
      (node (ref "PROGRAM_COUNTER_LOWER") (pin "6") (pinfunction "6_6") (pintype "passive"))
      (node (ref "RAM_ADDR_LOWER") (pin "11") (pinfunction "D4_11") (pintype "input"))
      (node (ref "REG_A_LOWER") (pin "14") (pinfunction "D1_14") (pintype "input"))
      (node (ref "REG_CALC_LOWER") (pin "14") (pinfunction "D1_14") (pintype "input"))
      (node (ref "REG_PARAM_LOWER") (pin "14") (pinfunction "D1_14") (pintype "input"))
      (node (ref "XOR_GATE_1") (pin "13") (pinfunction "I1_13") (pintype "input"))
    )
    (net (code "37") (name "Net-(ADDR_MEM_REG_LOWERA-D2)") (class "Default")
      (node (ref "ADDR_MEM_REG_LOWER") (pin "13") (pinfunction "D2_13") (pintype "input"))
      (node (ref "DATABUS_3") (pin "A") (pinfunction "A_A") (pintype "passive"))
      (node (ref "EXTENSION") (pin "3") (pinfunction "1_3") (pintype "passive"))
      (node (ref "INSTRUC_REGISTER_LOWER") (pin "13") (pinfunction "D2_13") (pintype "input"))
      (node (ref "MICRO_COUNTER_LOWER") (pin "5") (pinfunction "5_5") (pintype "passive"))
      (node (ref "OUTPUT_BUFFER_ALU") (pin "4") (pinfunction "A3_4") (pintype "bidirectional"))
      (node (ref "OUTPUT_BUFFER_CALC_REG") (pin "13") (pinfunction "B6_13") (pintype "bidirectional"))
      (node (ref "OUTPUT_BUFFER_FLAGS") (pin "4") (pinfunction "A3_4") (pintype "bidirectional"))
      (node (ref "OUTPUT_BUFFER_INSTRUCTION") (pin "13") (pinfunction "B6_13") (pintype "bidirectional"))
      (node (ref "OUTPUT_BUFFER_KEYBOARD") (pin "4") (pinfunction "A3_4") (pintype "bidirectional"))
      (node (ref "OUTPUT_BUFFER_MEMORY") (pin "13") (pinfunction "B6_13") (pintype "bidirectional"))
      (node (ref "OUTPUT_BUFFER_PARAM_REG") (pin "13") (pinfunction "B6_13") (pintype "bidirectional"))
      (node (ref "OUTPUT_BUFFER_PC") (pin "13") (pinfunction "B6_13") (pintype "bidirectional"))
      (node (ref "OUTPUT_BUFFER_RAM") (pin "16") (pinfunction "B3_16") (pintype "bidirectional"))
      (node (ref "OUTPUT_BUFFER_REG_A") (pin "13") (pinfunction "B6_13") (pintype "bidirectional"))
      (node (ref "OUT_REG_LOWER") (pin "13") (pinfunction "D2_13") (pintype "input"))
      (node (ref "PROGRAM_COUNTER_LOWER") (pin "5") (pinfunction "5_5") (pintype "passive"))
      (node (ref "RAM_ADDR_LOWER") (pin "12") (pinfunction "D3_12") (pintype "input"))
      (node (ref "REG_A_LOWER") (pin "13") (pinfunction "D2_13") (pintype "input"))
      (node (ref "REG_CALC_LOWER") (pin "13") (pinfunction "D2_13") (pintype "input"))
      (node (ref "REG_PARAM_LOWER") (pin "13") (pinfunction "D2_13") (pintype "input"))
      (node (ref "XOR_GATE_1") (pin "10") (pinfunction "I1_10") (pintype "input"))
    )
    (net (code "38") (name "Net-(ADDR_MEM_REG_LOWERA-D3)") (class "Default")
      (node (ref "ADDR_MEM_REG_LOWER") (pin "12") (pinfunction "D3_12") (pintype "input"))
      (node (ref "DATABUS_2") (pin "A") (pinfunction "A_A") (pintype "passive"))
      (node (ref "EXTENSION") (pin "2") (pinfunction "1_2") (pintype "passive"))
      (node (ref "INSTRUC_REGISTER_LOWER") (pin "12") (pinfunction "D3_12") (pintype "input"))
      (node (ref "MICRO_COUNTER_LOWER") (pin "4") (pinfunction "4_4") (pintype "passive"))
      (node (ref "OUTPUT_BUFFER_ALU") (pin "3") (pinfunction "A2_3") (pintype "bidirectional"))
      (node (ref "OUTPUT_BUFFER_CALC_REG") (pin "12") (pinfunction "B7_12") (pintype "bidirectional"))
      (node (ref "OUTPUT_BUFFER_FLAGS") (pin "3") (pinfunction "A2_3") (pintype "bidirectional"))
      (node (ref "OUTPUT_BUFFER_INSTRUCTION") (pin "12") (pinfunction "B7_12") (pintype "bidirectional"))
      (node (ref "OUTPUT_BUFFER_KEYBOARD") (pin "3") (pinfunction "A2_3") (pintype "bidirectional"))
      (node (ref "OUTPUT_BUFFER_MEMORY") (pin "12") (pinfunction "B7_12") (pintype "bidirectional"))
      (node (ref "OUTPUT_BUFFER_PARAM_REG") (pin "12") (pinfunction "B7_12") (pintype "bidirectional"))
      (node (ref "OUTPUT_BUFFER_PC") (pin "12") (pinfunction "B7_12") (pintype "bidirectional"))
      (node (ref "OUTPUT_BUFFER_RAM") (pin "17") (pinfunction "B2_17") (pintype "bidirectional"))
      (node (ref "OUTPUT_BUFFER_REG_A") (pin "12") (pinfunction "B7_12") (pintype "bidirectional"))
      (node (ref "OUT_REG_LOWER") (pin "12") (pinfunction "D3_12") (pintype "input"))
      (node (ref "PROGRAM_COUNTER_LOWER") (pin "4") (pinfunction "4_4") (pintype "passive"))
      (node (ref "RAM_ADDR_LOWER") (pin "13") (pinfunction "D2_13") (pintype "input"))
      (node (ref "REG_A_LOWER") (pin "12") (pinfunction "D3_12") (pintype "input"))
      (node (ref "REG_CALC_LOWER") (pin "12") (pinfunction "D3_12") (pintype "input"))
      (node (ref "REG_PARAM_LOWER") (pin "12") (pinfunction "D3_12") (pintype "input"))
      (node (ref "XOR_GATE_1") (pin "5") (pinfunction "I1_5") (pintype "input"))
    )
    (net (code "39") (name "Net-(ADDR_MEM_REG_LOWERA-D4)") (class "Default")
      (node (ref "ADDR_MEM_REG_LOWER") (pin "11") (pinfunction "D4_11") (pintype "input"))
      (node (ref "DATABUS_1") (pin "A") (pinfunction "A_A") (pintype "passive"))
      (node (ref "EXTENSION") (pin "1") (pinfunction "1_1") (pintype "passive"))
      (node (ref "INSTRUC_REGISTER_LOWER") (pin "11") (pinfunction "D4_11") (pintype "input"))
      (node (ref "MICRO_COUNTER_LOWER") (pin "3") (pinfunction "3_3") (pintype "passive"))
      (node (ref "OUTPUT_BUFFER_ALU") (pin "2") (pinfunction "A1_2") (pintype "bidirectional"))
      (node (ref "OUTPUT_BUFFER_CALC_REG") (pin "11") (pinfunction "B8_11") (pintype "bidirectional"))
      (node (ref "OUTPUT_BUFFER_FLAGS") (pin "2") (pinfunction "A1_2") (pintype "bidirectional"))
      (node (ref "OUTPUT_BUFFER_INSTRUCTION") (pin "11") (pinfunction "B8_11") (pintype "bidirectional"))
      (node (ref "OUTPUT_BUFFER_KEYBOARD") (pin "2") (pinfunction "A1_2") (pintype "bidirectional"))
      (node (ref "OUTPUT_BUFFER_MEMORY") (pin "11") (pinfunction "B8_11") (pintype "bidirectional"))
      (node (ref "OUTPUT_BUFFER_PARAM_REG") (pin "11") (pinfunction "B8_11") (pintype "bidirectional"))
      (node (ref "OUTPUT_BUFFER_PC") (pin "11") (pinfunction "B8_11") (pintype "bidirectional"))
      (node (ref "OUTPUT_BUFFER_RAM") (pin "18") (pinfunction "B1_18") (pintype "bidirectional"))
      (node (ref "OUTPUT_BUFFER_REG_A") (pin "11") (pinfunction "B8_11") (pintype "bidirectional"))
      (node (ref "OUT_REG_LOWER") (pin "11") (pinfunction "D4_11") (pintype "input"))
      (node (ref "PROGRAM_COUNTER_LOWER") (pin "3") (pinfunction "3_3") (pintype "passive"))
      (node (ref "RAM_ADDR_LOWER") (pin "14") (pinfunction "D1_14") (pintype "input"))
      (node (ref "REG_A_LOWER") (pin "11") (pinfunction "D4_11") (pintype "input"))
      (node (ref "REG_CALC_LOWER") (pin "11") (pinfunction "D4_11") (pintype "input"))
      (node (ref "REG_PARAM_LOWER") (pin "11") (pinfunction "D4_11") (pintype "input"))
      (node (ref "XOR_GATE_1") (pin "2") (pinfunction "I1_2") (pintype "input"))
    )
    (net (code "40") (name "Net-(ADDR_MEM_REG_LOWERA-G1)") (class "Default")
      (node (ref "ADDR_MEM_REG_LOWER") (pin "10") (pinfunction "G2_10") (pintype "input"))
      (node (ref "ADDR_MEM_REG_LOWER") (pin "9") (pinfunction "G1_9") (pintype "input"))
      (node (ref "ADDR_MEM_REG_UPPER") (pin "10") (pinfunction "G2_10") (pintype "input"))
      (node (ref "ADDR_MEM_REG_UPPER") (pin "9") (pinfunction "G1_9") (pintype "input"))
      (node (ref "NOT_GATE1_") (pin "6") (pinfunction "O_6") (pintype "output"))
    )
    (net (code "41") (name "Net-(ADDR_MEM_REG_LOWERA-Q1)") (class "Default")
      (node (ref "ADDR_MEM_REG_LOWER") (pin "3") (pinfunction "Q1_3") (pintype "tri_state"))
      (node (ref "MEMORY") (pin "7") (pinfunction "7_7") (pintype "passive"))
    )
    (net (code "42") (name "Net-(ADDR_MEM_REG_LOWERA-Q2)") (class "Default")
      (node (ref "ADDR_MEM_REG_LOWER") (pin "4") (pinfunction "Q2_4") (pintype "tri_state"))
      (node (ref "MEMORY") (pin "8") (pinfunction "8_8") (pintype "passive"))
    )
    (net (code "43") (name "Net-(ADDR_MEM_REG_LOWERA-Q3)") (class "Default")
      (node (ref "ADDR_MEM_REG_LOWER") (pin "5") (pinfunction "Q3_5") (pintype "tri_state"))
      (node (ref "MEMORY") (pin "9") (pinfunction "9_9") (pintype "passive"))
    )
    (net (code "44") (name "Net-(ADDR_MEM_REG_LOWERA-Q4)") (class "Default")
      (node (ref "ADDR_MEM_REG_LOWER") (pin "6") (pinfunction "Q4_6") (pintype "tri_state"))
      (node (ref "MEMORY") (pin "10") (pinfunction "10_10") (pintype "passive"))
    )
    (net (code "45") (name "Net-(ADDR_MEM_REG_UPPERA-D1)") (class "Default")
      (node (ref "ADDR_MEM_REG_UPPER") (pin "14") (pinfunction "D1_14") (pintype "input"))
      (node (ref "DATABUS_8") (pin "A") (pinfunction "A_A") (pintype "passive"))
      (node (ref "EXTENSION") (pin "8") (pinfunction "1_8") (pintype "passive"))
      (node (ref "INSTRUC_REGISTER_UPPER") (pin "14") (pinfunction "D1_14") (pintype "input"))
      (node (ref "OUTPUT_BUFFER_ALU") (pin "9") (pinfunction "A8_9") (pintype "bidirectional"))
      (node (ref "OUTPUT_BUFFER_CALC_REG") (pin "18") (pinfunction "B1_18") (pintype "bidirectional"))
      (node (ref "OUTPUT_BUFFER_FLAGS") (pin "9") (pinfunction "A8_9") (pintype "bidirectional"))
      (node (ref "OUTPUT_BUFFER_INSTRUCTION") (pin "18") (pinfunction "B1_18") (pintype "bidirectional"))
      (node (ref "OUTPUT_BUFFER_KEYBOARD") (pin "9") (pinfunction "A8_9") (pintype "bidirectional"))
      (node (ref "OUTPUT_BUFFER_MEMORY") (pin "18") (pinfunction "B1_18") (pintype "bidirectional"))
      (node (ref "OUTPUT_BUFFER_PARAM_REG") (pin "18") (pinfunction "B1_18") (pintype "bidirectional"))
      (node (ref "OUTPUT_BUFFER_PC") (pin "18") (pinfunction "B1_18") (pintype "bidirectional"))
      (node (ref "OUTPUT_BUFFER_RAM") (pin "11") (pinfunction "B8_11") (pintype "bidirectional"))
      (node (ref "OUTPUT_BUFFER_REG_A") (pin "18") (pinfunction "B1_18") (pintype "bidirectional"))
      (node (ref "OUT_REG_UPPER") (pin "14") (pinfunction "D1_14") (pintype "input"))
      (node (ref "PROGRAM_COUNTER_UPPER") (pin "6") (pinfunction "6_6") (pintype "passive"))
      (node (ref "RAM_ADDR_UPPER") (pin "11") (pinfunction "D4_11") (pintype "input"))
      (node (ref "REG_A_UPPER") (pin "14") (pinfunction "D1_14") (pintype "input"))
      (node (ref "REG_CALC_UPPER") (pin "14") (pinfunction "D1_14") (pintype "input"))
      (node (ref "REG_PARAM_UPPER") (pin "14") (pinfunction "D1_14") (pintype "input"))
    )
    (net (code "46") (name "Net-(ADDR_MEM_REG_UPPERA-D2)") (class "Default")
      (node (ref "ADDR_MEM_REG_UPPER") (pin "13") (pinfunction "D2_13") (pintype "input"))
      (node (ref "DATABUS_7") (pin "A") (pinfunction "A_A") (pintype "passive"))
      (node (ref "EXTENSION") (pin "7") (pinfunction "1_7") (pintype "passive"))
      (node (ref "INSTRUC_REGISTER_UPPER") (pin "13") (pinfunction "D2_13") (pintype "input"))
      (node (ref "OUTPUT_BUFFER_ALU") (pin "8") (pinfunction "A7_8") (pintype "bidirectional"))
      (node (ref "OUTPUT_BUFFER_CALC_REG") (pin "17") (pinfunction "B2_17") (pintype "bidirectional"))
      (node (ref "OUTPUT_BUFFER_FLAGS") (pin "8") (pinfunction "A7_8") (pintype "bidirectional"))
      (node (ref "OUTPUT_BUFFER_INSTRUCTION") (pin "17") (pinfunction "B2_17") (pintype "bidirectional"))
      (node (ref "OUTPUT_BUFFER_KEYBOARD") (pin "8") (pinfunction "A7_8") (pintype "bidirectional"))
      (node (ref "OUTPUT_BUFFER_MEMORY") (pin "17") (pinfunction "B2_17") (pintype "bidirectional"))
      (node (ref "OUTPUT_BUFFER_PARAM_REG") (pin "17") (pinfunction "B2_17") (pintype "bidirectional"))
      (node (ref "OUTPUT_BUFFER_PC") (pin "17") (pinfunction "B2_17") (pintype "bidirectional"))
      (node (ref "OUTPUT_BUFFER_RAM") (pin "12") (pinfunction "B7_12") (pintype "bidirectional"))
      (node (ref "OUTPUT_BUFFER_REG_A") (pin "17") (pinfunction "B2_17") (pintype "bidirectional"))
      (node (ref "OUT_REG_UPPER") (pin "13") (pinfunction "D2_13") (pintype "input"))
      (node (ref "PROGRAM_COUNTER_UPPER") (pin "5") (pinfunction "5_5") (pintype "passive"))
      (node (ref "RAM_ADDR_UPPER") (pin "12") (pinfunction "D3_12") (pintype "input"))
      (node (ref "REG_A_UPPER") (pin "13") (pinfunction "D2_13") (pintype "input"))
      (node (ref "REG_CALC_UPPER") (pin "13") (pinfunction "D2_13") (pintype "input"))
      (node (ref "REG_PARAM_UPPER") (pin "13") (pinfunction "D2_13") (pintype "input"))
      (node (ref "XOR_GATE_2") (pin "10") (pinfunction "I1_10") (pintype "input"))
    )
    (net (code "47") (name "Net-(ADDR_MEM_REG_UPPERA-D3)") (class "Default")
      (node (ref "ADDR_MEM_REG_UPPER") (pin "12") (pinfunction "D3_12") (pintype "input"))
      (node (ref "DATABUS_6") (pin "A") (pinfunction "A_A") (pintype "passive"))
      (node (ref "EXTENSION") (pin "6") (pinfunction "1_6") (pintype "passive"))
      (node (ref "INSTRUC_REGISTER_UPPER") (pin "12") (pinfunction "D3_12") (pintype "input"))
      (node (ref "OUTPUT_BUFFER_ALU") (pin "7") (pinfunction "A6_7") (pintype "bidirectional"))
      (node (ref "OUTPUT_BUFFER_CALC_REG") (pin "16") (pinfunction "B3_16") (pintype "bidirectional"))
      (node (ref "OUTPUT_BUFFER_FLAGS") (pin "7") (pinfunction "A6_7") (pintype "bidirectional"))
      (node (ref "OUTPUT_BUFFER_INSTRUCTION") (pin "16") (pinfunction "B3_16") (pintype "bidirectional"))
      (node (ref "OUTPUT_BUFFER_KEYBOARD") (pin "7") (pinfunction "A6_7") (pintype "bidirectional"))
      (node (ref "OUTPUT_BUFFER_MEMORY") (pin "16") (pinfunction "B3_16") (pintype "bidirectional"))
      (node (ref "OUTPUT_BUFFER_PARAM_REG") (pin "16") (pinfunction "B3_16") (pintype "bidirectional"))
      (node (ref "OUTPUT_BUFFER_PC") (pin "16") (pinfunction "B3_16") (pintype "bidirectional"))
      (node (ref "OUTPUT_BUFFER_RAM") (pin "13") (pinfunction "B6_13") (pintype "bidirectional"))
      (node (ref "OUTPUT_BUFFER_REG_A") (pin "16") (pinfunction "B3_16") (pintype "bidirectional"))
      (node (ref "OUT_REG_UPPER") (pin "12") (pinfunction "D3_12") (pintype "input"))
      (node (ref "PROGRAM_COUNTER_UPPER") (pin "4") (pinfunction "4_4") (pintype "passive"))
      (node (ref "RAM_ADDR_UPPER") (pin "13") (pinfunction "D2_13") (pintype "input"))
      (node (ref "REG_A_UPPER") (pin "12") (pinfunction "D3_12") (pintype "input"))
      (node (ref "REG_CALC_UPPER") (pin "12") (pinfunction "D3_12") (pintype "input"))
      (node (ref "REG_PARAM_UPPER") (pin "12") (pinfunction "D3_12") (pintype "input"))
      (node (ref "XOR_GATE_2") (pin "5") (pinfunction "I1_5") (pintype "input"))
    )
    (net (code "48") (name "Net-(ADDR_MEM_REG_UPPERA-D4)") (class "Default")
      (node (ref "ADDR_MEM_REG_UPPER") (pin "11") (pinfunction "D4_11") (pintype "input"))
      (node (ref "DATABUS_5") (pin "A") (pinfunction "A_A") (pintype "passive"))
      (node (ref "EXTENSION") (pin "5") (pinfunction "1_5") (pintype "passive"))
      (node (ref "INSTRUC_REGISTER_UPPER") (pin "11") (pinfunction "D4_11") (pintype "input"))
      (node (ref "MICRO_COUNTER_UPPER") (pin "3") (pinfunction "3_3") (pintype "passive"))
      (node (ref "OUTPUT_BUFFER_ALU") (pin "6") (pinfunction "A5_6") (pintype "bidirectional"))
      (node (ref "OUTPUT_BUFFER_CALC_REG") (pin "15") (pinfunction "B4_15") (pintype "bidirectional"))
      (node (ref "OUTPUT_BUFFER_FLAGS") (pin "6") (pinfunction "A5_6") (pintype "bidirectional"))
      (node (ref "OUTPUT_BUFFER_INSTRUCTION") (pin "15") (pinfunction "B4_15") (pintype "bidirectional"))
      (node (ref "OUTPUT_BUFFER_KEYBOARD") (pin "6") (pinfunction "A5_6") (pintype "bidirectional"))
      (node (ref "OUTPUT_BUFFER_MEMORY") (pin "15") (pinfunction "B4_15") (pintype "bidirectional"))
      (node (ref "OUTPUT_BUFFER_PARAM_REG") (pin "15") (pinfunction "B4_15") (pintype "bidirectional"))
      (node (ref "OUTPUT_BUFFER_PC") (pin "15") (pinfunction "B4_15") (pintype "bidirectional"))
      (node (ref "OUTPUT_BUFFER_RAM") (pin "14") (pinfunction "B5_14") (pintype "bidirectional"))
      (node (ref "OUTPUT_BUFFER_REG_A") (pin "15") (pinfunction "B4_15") (pintype "bidirectional"))
      (node (ref "OUT_REG_UPPER") (pin "11") (pinfunction "D4_11") (pintype "input"))
      (node (ref "PROGRAM_COUNTER_UPPER") (pin "3") (pinfunction "3_3") (pintype "passive"))
      (node (ref "RAM_ADDR_UPPER") (pin "14") (pinfunction "D1_14") (pintype "input"))
      (node (ref "REG_A_UPPER") (pin "11") (pinfunction "D4_11") (pintype "input"))
      (node (ref "REG_CALC_UPPER") (pin "11") (pinfunction "D4_11") (pintype "input"))
      (node (ref "REG_PARAM_UPPER") (pin "11") (pinfunction "D4_11") (pintype "input"))
      (node (ref "XOR_GATE_2") (pin "2") (pinfunction "I1_2") (pintype "input"))
    )
    (net (code "49") (name "Net-(ADDR_MEM_REG_UPPERA-Q1)") (class "Default")
      (node (ref "ADDR_MEM_REG_UPPER") (pin "3") (pinfunction "Q1_3") (pintype "tri_state"))
      (node (ref "MEMORY") (pin "3") (pinfunction "3_3") (pintype "passive"))
    )
    (net (code "50") (name "Net-(ADDR_MEM_REG_UPPERA-Q2)") (class "Default")
      (node (ref "ADDR_MEM_REG_UPPER") (pin "4") (pinfunction "Q2_4") (pintype "tri_state"))
      (node (ref "MEMORY") (pin "4") (pinfunction "4_4") (pintype "passive"))
    )
    (net (code "51") (name "Net-(ADDR_MEM_REG_UPPERA-Q3)") (class "Default")
      (node (ref "ADDR_MEM_REG_UPPER") (pin "5") (pinfunction "Q3_5") (pintype "tri_state"))
      (node (ref "MEMORY") (pin "5") (pinfunction "5_5") (pintype "passive"))
    )
    (net (code "52") (name "Net-(ADDR_MEM_REG_UPPERA-Q4)") (class "Default")
      (node (ref "ADDR_MEM_REG_UPPER") (pin "6") (pinfunction "Q4_6") (pintype "tri_state"))
      (node (ref "MEMORY") (pin "6") (pinfunction "6_6") (pintype "passive"))
    )
    (net (code "53") (name "Net-(AND_GATE3_A-I1)") (class "Default")
      (node (ref "AND_GATE3_") (pin "2") (pinfunction "I1_2") (pintype "input"))
      (node (ref "NOT_GATE_") (pin "8") (pinfunction "O_8") (pintype "output"))
    )
    (net (code "54") (name "Net-(AND_GATE3_A-O)") (class "Default")
      (node (ref "AND_GATE3_") (pin "3") (pinfunction "O_3") (pintype "output"))
      (node (ref "NOT_GATE4_") (pin "5") (pinfunction "I_5") (pintype "input"))
    )
    (net (code "55") (name "Net-(AND_GATE3_B-I1)") (class "Default")
      (node (ref "AND_GATE3_") (pin "5") (pinfunction "I1_5") (pintype "input"))
      (node (ref "NOT_GATE4_") (pin "12") (pinfunction "O_12") (pintype "output"))
    )
    (net (code "56") (name "Net-(AND_GATE3_B-O)") (class "Default")
      (node (ref "AND_GATE3_") (pin "6") (pinfunction "O_6") (pintype "output"))
      (node (ref "NOT_GATE4_") (pin "9") (pinfunction "I_9") (pintype "input"))
    )
    (net (code "57") (name "Net-(AND_GATE3_C-I0)") (class "Default")
      (node (ref "AND_GATE3_") (pin "9") (pinfunction "I0_9") (pintype "input"))
      (node (ref "SELECTOR_LOGIC_") (pin "9") (pinfunction "Y3_9") (pintype "output"))
    )
    (net (code "58") (name "Net-(AND_GATE3_C-I1)") (class "Default")
      (node (ref "AND_GATE3_") (pin "10") (pinfunction "I1_10") (pintype "input"))
      (node (ref "PROGRAM_COUNTER_LOWER") (pin "1") (pinfunction "1_1") (pintype "passive"))
      (node (ref "PROGRAM_COUNTER_UPPER") (pin "1") (pinfunction "1_1") (pintype "passive"))
      (node (ref "R80") (pin "1") (pinfunction "1_1") (pintype "passive"))
      (node (ref "RESET_PC") (pin "1") (pinfunction "S_1") (pintype "passive"))
    )
    (net (code "59") (name "Net-(AND_GATE3_C-O)") (class "Default")
      (node (ref "AND_GATE3_") (pin "8") (pinfunction "O_8") (pintype "output"))
      (node (ref "MICRO_COUNTER_LOWER") (pin "1") (pinfunction "1_1") (pintype "passive"))
      (node (ref "MICRO_COUNTER_UPPER") (pin "1") (pinfunction "1_1") (pintype "passive"))
    )
    (net (code "60") (name "Net-(AND_GATE3_D-I0)") (class "Default")
      (node (ref "AND_GATE3_") (pin "12") (pinfunction "I0_12") (pintype "input"))
      (node (ref "NOT_GATE2_") (pin "8") (pinfunction "O_8") (pintype "output"))
    )
    (net (code "61") (name "Net-(AND_GATE4_A-I0)") (class "Default")
      (node (ref "AND_GATE4_") (pin "1") (pinfunction "I0_1") (pintype "input"))
      (node (ref "NOT_GATE2_") (pin "6") (pinfunction "O_6") (pintype "output"))
    )
    (net (code "62") (name "Net-(AND_GATE4_A-I1)") (class "Default")
      (node (ref "AND_GATE4_") (pin "2") (pinfunction "I1_2") (pintype "input"))
      (node (ref "ZERO_FLAG") (pin "A") (pinfunction "A_A") (pintype "passive"))
      (node (ref "ZERO_POS_FLAG_IDENTIFIER") (pin "13") (pinfunction "W_13") (pintype "output"))
    )
    (net (code "63") (name "Net-(AND_GATE4_B-I0)") (class "Default")
      (node (ref "AND_GATE4_") (pin "4") (pinfunction "I0_4") (pintype "input"))
      (node (ref "NOT_GATE1_") (pin "2") (pinfunction "O_2") (pintype "output"))
    )
    (net (code "64") (name "Net-(AND_GATE4_B-I1)") (class "Default")
      (node (ref "AND_GATE4_") (pin "5") (pinfunction "I1_5") (pintype "input"))
      (node (ref "POSITIVE_FLAG") (pin "A") (pinfunction "A_A") (pintype "passive"))
      (node (ref "ZERO_POS_FLAG_IDENTIFIER") (pin "1") (pinfunction "Y_1") (pintype "output"))
    )
    (net (code "65") (name "Net-(AND_GATE_A-I0)") (class "Default")
      (node (ref "AND_GATE_") (pin "1") (pinfunction "I0_1") (pintype "input"))
      (node (ref "AUTO_CLOCK") (pin "3") (pinfunction "Q_3") (pintype "output"))
    )
    (net (code "66") (name "Net-(AND_GATE_A-I1)") (class "Default")
      (node (ref "AND_GATE_") (pin "2") (pinfunction "I1_2") (pintype "input"))
      (node (ref "NOT_GATE1_") (pin "4") (pinfunction "O_4") (pintype "output"))
    )
    (net (code "67") (name "Net-(AND_GATE_A-O)") (class "Default")
      (node (ref "AND_GATE_") (pin "3") (pinfunction "O_3") (pintype "output"))
      (node (ref "OR_GATE_") (pin "1") (pinfunction "I0_1") (pintype "input"))
    )
    (net (code "68") (name "Net-(AND_GATE_B-I0)") (class "Default")
      (node (ref "AND_GATE_") (pin "4") (pinfunction "I0_4") (pintype "input"))
      (node (ref "CLK_MODE") (pin "1") (pinfunction "1_1") (pintype "passive"))
      (node (ref "NOT_GATE1_") (pin "3") (pinfunction "I_3") (pintype "input"))
      (node (ref "R4") (pin "2") (pinfunction "2_2") (pintype "passive"))
    )
    (net (code "69") (name "Net-(AND_GATE_B-I1)") (class "Default")
      (node (ref "AND_GATE_") (pin "5") (pinfunction "I1_5") (pintype "input"))
      (node (ref "STEPPER_CLOCK") (pin "3") (pinfunction "Q_3") (pintype "output"))
    )
    (net (code "70") (name "Net-(AND_GATE_B-O)") (class "Default")
      (node (ref "AND_GATE_") (pin "6") (pinfunction "O_6") (pintype "output"))
      (node (ref "OR_GATE_") (pin "2") (pinfunction "I1_2") (pintype "input"))
    )
    (net (code "71") (name "Net-(AND_GATE_C-I0)") (class "Default")
      (node (ref "AND_GATE_") (pin "9") (pinfunction "I0_9") (pintype "input"))
      (node (ref "NOR_GATE_") (pin "4") (pinfunction "O_4") (pintype "output"))
    )
    (net (code "72") (name "Net-(AND_GATE_C-I1)") (class "Default")
      (node (ref "AND_GATE_") (pin "10") (pinfunction "I1_10") (pintype "input"))
      (node (ref "OR_GATE_") (pin "3") (pinfunction "O_3") (pintype "output"))
    )
    (net (code "73") (name "Net-(AND_GATE_D-I0)") (class "Default")
      (node (ref "AND_GATE_") (pin "12") (pinfunction "I0_12") (pintype "input"))
      (node (ref "NOR_GATE_") (pin "1") (pinfunction "O_1") (pintype "output"))
    )
    (net (code "74") (name "Net-(AND_GATE_D-I1)") (class "Default")
      (node (ref "AND_GATE_") (pin "13") (pinfunction "I1_13") (pintype "input"))
      (node (ref "SELECTOR_PARAM_") (pin "7") (pinfunction "Y3_7") (pintype "output"))
      (node (ref "XOR_GATE_2") (pin "13") (pinfunction "I1_13") (pintype "input"))
    )
    (net (code "75") (name "Net-(AND_GATE_D-O)") (class "Default")
      (node (ref "AND_GATE_") (pin "11") (pinfunction "O_11") (pintype "output"))
      (node (ref "XOR_GATE_2") (pin "12") (pinfunction "I0_12") (pintype "input"))
    )
    (net (code "76") (name "Net-(AUTO_CLOCK-DIS)") (class "Default")
      (node (ref "AUTO_CLOCK") (pin "7") (pinfunction "DIS_7") (pintype "input"))
      (node (ref "FREQUENCY") (pin "E") (pinfunction "E_E") (pintype "passive"))
      (node (ref "R1") (pin "2") (pinfunction "2_2") (pintype "passive"))
    )
    (net (code "77") (name "Net-(AUTO_CLOCK-THR)") (class "Default")
      (node (ref "AUTO_CLOCK") (pin "2") (pinfunction "TR_2") (pintype "input"))
      (node (ref "AUTO_CLOCK") (pin "6") (pinfunction "THR_6") (pintype "input"))
      (node (ref "C1") (pin "+") (pinfunction "+_+") (pintype "passive"))
      (node (ref "R7") (pin "2") (pinfunction "2_2") (pintype "passive"))
    )
    (net (code "78") (name "Net-(CLK_TRIGGER-S1)") (class "Default")
      (node (ref "CLK_TRIGGER") (pin "2") (pinfunction "S1_2") (pintype "passive"))
      (node (ref "R2") (pin "2") (pinfunction "2_2") (pintype "passive"))
      (node (ref "STEPPER_CLOCK") (pin "2") (pinfunction "TR_2") (pintype "input"))
    )
    (net (code "79") (name "Net-(CLOCK-C)") (class "Default")
      (node (ref "CLOCK") (pin "K") (pinfunction "C_K") (pintype "passive"))
      (node (ref "R5") (pin "2") (pinfunction "2_2") (pintype "passive"))
    )
    (net (code "80") (name "Net-(DATABUS_1-C)") (class "Default")
      (node (ref "DATABUS_1") (pin "K") (pinfunction "C_K") (pintype "passive"))
      (node (ref "R24") (pin "1") (pinfunction "1_1") (pintype "passive"))
    )
    (net (code "81") (name "Net-(DATABUS_2-C)") (class "Default")
      (node (ref "DATABUS_2") (pin "K") (pinfunction "C_K") (pintype "passive"))
      (node (ref "R25") (pin "1") (pinfunction "1_1") (pintype "passive"))
    )
    (net (code "82") (name "Net-(DATABUS_3-C)") (class "Default")
      (node (ref "DATABUS_3") (pin "K") (pinfunction "C_K") (pintype "passive"))
      (node (ref "R26") (pin "1") (pinfunction "1_1") (pintype "passive"))
    )
    (net (code "83") (name "Net-(DATABUS_4-C)") (class "Default")
      (node (ref "DATABUS_4") (pin "K") (pinfunction "C_K") (pintype "passive"))
      (node (ref "R27") (pin "1") (pinfunction "1_1") (pintype "passive"))
    )
    (net (code "84") (name "Net-(DATABUS_5-C)") (class "Default")
      (node (ref "DATABUS_5") (pin "K") (pinfunction "C_K") (pintype "passive"))
      (node (ref "R28") (pin "1") (pinfunction "1_1") (pintype "passive"))
    )
    (net (code "85") (name "Net-(DATABUS_6-C)") (class "Default")
      (node (ref "DATABUS_6") (pin "K") (pinfunction "C_K") (pintype "passive"))
      (node (ref "R29") (pin "1") (pinfunction "1_1") (pintype "passive"))
    )
    (net (code "86") (name "Net-(DATABUS_7-C)") (class "Default")
      (node (ref "DATABUS_7") (pin "K") (pinfunction "C_K") (pintype "passive"))
      (node (ref "R30") (pin "1") (pinfunction "1_1") (pintype "passive"))
    )
    (net (code "87") (name "Net-(DATABUS_8-C)") (class "Default")
      (node (ref "DATABUS_8") (pin "K") (pinfunction "C_K") (pintype "passive"))
      (node (ref "R31") (pin "1") (pinfunction "1_1") (pintype "passive"))
    )
    (net (code "88") (name "Net-(FLAG_1-C)") (class "Default")
      (node (ref "FLAG_1") (pin "K") (pinfunction "C_K") (pintype "passive"))
      (node (ref "R15") (pin "2") (pinfunction "2_2") (pintype "passive"))
    )
    (net (code "89") (name "Net-(FLAG_2-C)") (class "Default")
      (node (ref "FLAG_2") (pin "K") (pinfunction "C_K") (pintype "passive"))
      (node (ref "R77") (pin "2") (pinfunction "2_2") (pintype "passive"))
    )
    (net (code "90") (name "Net-(FLAG_3-C)") (class "Default")
      (node (ref "FLAG_3") (pin "K") (pinfunction "C_K") (pintype "passive"))
      (node (ref "R78") (pin "2") (pinfunction "2_2") (pintype "passive"))
    )
    (net (code "91") (name "Net-(FLAG_4-C)") (class "Default")
      (node (ref "FLAG_4") (pin "K") (pinfunction "C_K") (pintype "passive"))
      (node (ref "R79") (pin "2") (pinfunction "2_2") (pintype "passive"))
    )
    (net (code "92") (name "Net-(FLAG_5-C)") (class "Default")
      (node (ref "FLAG_5") (pin "K") (pinfunction "C_K") (pintype "passive"))
      (node (ref "R11") (pin "2") (pinfunction "2_2") (pintype "passive"))
    )
    (net (code "93") (name "Net-(FLAG_6-C)") (class "Default")
      (node (ref "FLAG_6") (pin "K") (pinfunction "C_K") (pintype "passive"))
      (node (ref "R10") (pin "2") (pinfunction "2_2") (pintype "passive"))
    )
    (net (code "94") (name "Net-(FLAG_7-C)") (class "Default")
      (node (ref "FLAG_7") (pin "K") (pinfunction "C_K") (pintype "passive"))
      (node (ref "R9") (pin "2") (pinfunction "2_2") (pintype "passive"))
    )
    (net (code "95") (name "Net-(FLAG_8-C)") (class "Default")
      (node (ref "FLAG_8") (pin "K") (pinfunction "C_K") (pintype "passive"))
      (node (ref "R8") (pin "2") (pinfunction "2_2") (pintype "passive"))
    )
    (net (code "96") (name "Net-(FLAG_REG_LOWERA-D2)") (class "Default")
      (node (ref "FLAG_REG_LOWER") (pin "13") (pinfunction "D2_13") (pintype "input"))
      (node (ref "XOR_GATE_2") (pin "8") (pinfunction "O_8") (pintype "output"))
    )
    (net (code "97") (name "Net-(FLAG_REG_LOWERA-D3)") (class "Default")
      (node (ref "FLAG_REG_LOWER") (pin "12") (pinfunction "D3_12") (pintype "input"))
      (node (ref "XOR_GATE_2") (pin "6") (pinfunction "O_6") (pintype "output"))
    )
    (net (code "98") (name "Net-(FLAG_REG_LOWERA-D4)") (class "Default")
      (node (ref "FLAG_REG_LOWER") (pin "11") (pinfunction "D4_11") (pintype "input"))
      (node (ref "XOR_GATE_2") (pin "3") (pinfunction "O_3") (pintype "output"))
    )
    (net (code "99") (name "Net-(FLAG_REG_LOWERA-G1)") (class "Default")
      (node (ref "FLAG_REG_LOWER") (pin "10") (pinfunction "G2_10") (pintype "input"))
      (node (ref "FLAG_REG_LOWER") (pin "9") (pinfunction "G1_9") (pintype "input"))
      (node (ref "FLAG_REG_UPPER") (pin "10") (pinfunction "G2_10") (pintype "input"))
      (node (ref "FLAG_REG_UPPER") (pin "9") (pinfunction "G1_9") (pintype "input"))
      (node (ref "NOT_GATE1_") (pin "12") (pinfunction "O_12") (pintype "output"))
    )
    (net (code "100") (name "Net-(FLAG_REG_LOWERA-Q1)") (class "Default")
      (node (ref "FLAG_8") (pin "A") (pinfunction "A_A") (pintype "passive"))
      (node (ref "FLAG_REG_LOWER") (pin "3") (pinfunction "Q1_3") (pintype "tri_state"))
      (node (ref "OUTPUT_BUFFER_FLAGS") (pin "11") (pinfunction "B8_11") (pintype "bidirectional"))
    )
    (net (code "101") (name "Net-(FLAG_REG_LOWERA-Q2)") (class "Default")
      (node (ref "FLAG_7") (pin "A") (pinfunction "A_A") (pintype "passive"))
      (node (ref "FLAG_REG_LOWER") (pin "4") (pinfunction "Q2_4") (pintype "tri_state"))
      (node (ref "OUTPUT_BUFFER_FLAGS") (pin "12") (pinfunction "B7_12") (pintype "bidirectional"))
      (node (ref "XOR_GATE_2") (pin "9") (pinfunction "I0_9") (pintype "input"))
    )
    (net (code "102") (name "Net-(FLAG_REG_LOWERA-Q3)") (class "Default")
      (node (ref "FLAG_6") (pin "A") (pinfunction "A_A") (pintype "passive"))
      (node (ref "FLAG_REG_LOWER") (pin "5") (pinfunction "Q3_5") (pintype "tri_state"))
      (node (ref "OUTPUT_BUFFER_FLAGS") (pin "13") (pinfunction "B6_13") (pintype "bidirectional"))
      (node (ref "XOR_GATE_2") (pin "4") (pinfunction "I0_4") (pintype "input"))
    )
    (net (code "103") (name "Net-(FLAG_REG_LOWERA-Q4)") (class "Default")
      (node (ref "FLAG_5") (pin "A") (pinfunction "A_A") (pintype "passive"))
      (node (ref "FLAG_REG_LOWER") (pin "6") (pinfunction "Q4_6") (pintype "tri_state"))
      (node (ref "OUTPUT_BUFFER_FLAGS") (pin "14") (pinfunction "B5_14") (pintype "bidirectional"))
      (node (ref "XOR_GATE_2") (pin "1") (pinfunction "I0_1") (pintype "input"))
    )
    (net (code "104") (name "Net-(FLAG_REG_UPPERA-D1)") (class "Default")
      (node (ref "FLAG_REG_UPPER") (pin "14") (pinfunction "D1_14") (pintype "input"))
      (node (ref "XOR_GATE_1") (pin "11") (pinfunction "O_11") (pintype "output"))
    )
    (net (code "105") (name "Net-(FLAG_REG_UPPERA-D2)") (class "Default")
      (node (ref "FLAG_REG_UPPER") (pin "13") (pinfunction "D2_13") (pintype "input"))
      (node (ref "XOR_GATE_1") (pin "8") (pinfunction "O_8") (pintype "output"))
    )
    (net (code "106") (name "Net-(FLAG_REG_UPPERA-D3)") (class "Default")
      (node (ref "FLAG_REG_UPPER") (pin "12") (pinfunction "D3_12") (pintype "input"))
      (node (ref "XOR_GATE_1") (pin "6") (pinfunction "O_6") (pintype "output"))
    )
    (net (code "107") (name "Net-(FLAG_REG_UPPERA-D4)") (class "Default")
      (node (ref "FLAG_REG_UPPER") (pin "11") (pinfunction "D4_11") (pintype "input"))
      (node (ref "XOR_GATE_1") (pin "3") (pinfunction "O_3") (pintype "output"))
    )
    (net (code "108") (name "Net-(FLAG_REG_UPPERA-Q1)") (class "Default")
      (node (ref "FLAG_4") (pin "A") (pinfunction "A_A") (pintype "passive"))
      (node (ref "FLAG_REG_UPPER") (pin "3") (pinfunction "Q1_3") (pintype "tri_state"))
      (node (ref "OUTPUT_BUFFER_FLAGS") (pin "15") (pinfunction "B4_15") (pintype "bidirectional"))
      (node (ref "XOR_GATE_1") (pin "12") (pinfunction "I0_12") (pintype "input"))
    )
    (net (code "109") (name "Net-(FLAG_REG_UPPERA-Q2)") (class "Default")
      (node (ref "FLAG_3") (pin "A") (pinfunction "A_A") (pintype "passive"))
      (node (ref "FLAG_REG_UPPER") (pin "4") (pinfunction "Q2_4") (pintype "tri_state"))
      (node (ref "OUTPUT_BUFFER_FLAGS") (pin "16") (pinfunction "B3_16") (pintype "bidirectional"))
      (node (ref "XOR_GATE_1") (pin "9") (pinfunction "I0_9") (pintype "input"))
    )
    (net (code "110") (name "Net-(FLAG_REG_UPPERA-Q3)") (class "Default")
      (node (ref "FLAG_2") (pin "A") (pinfunction "A_A") (pintype "passive"))
      (node (ref "FLAG_REG_UPPER") (pin "5") (pinfunction "Q3_5") (pintype "tri_state"))
      (node (ref "OUTPUT_BUFFER_FLAGS") (pin "17") (pinfunction "B2_17") (pintype "bidirectional"))
      (node (ref "XOR_GATE_1") (pin "4") (pinfunction "I0_4") (pintype "input"))
    )
    (net (code "111") (name "Net-(FLAG_REG_UPPERA-Q4)") (class "Default")
      (node (ref "FLAG_1") (pin "A") (pinfunction "A_A") (pintype "passive"))
      (node (ref "FLAG_REG_UPPER") (pin "6") (pinfunction "Q4_6") (pintype "tri_state"))
      (node (ref "MEMORY") (pin "25") (pinfunction "25_25") (pintype "passive"))
      (node (ref "OUTPUT_BUFFER_FLAGS") (pin "18") (pinfunction "B1_18") (pintype "bidirectional"))
      (node (ref "XOR_GATE_1") (pin "1") (pinfunction "I0_1") (pintype "input"))
    )
    (net (code "112") (name "Net-(FREQUENCY-PadS)") (class "Default")
      (node (ref "FREQUENCY") (pin "S") (pinfunction "S_S") (pintype "passive"))
      (node (ref "R7") (pin "1") (pinfunction "1_1") (pintype "passive"))
    )
    (net (code "113") (name "Net-(INSTRUCTIONS_EXTENSIONB-1)") (class "Default")
      (node (ref "INSTRUCTIONS_EXTENSION") (pin "10") (pinfunction "1_10") (pintype "passive"))
      (node (ref "INSTRUCTION_MEMORY_0") (pin "24") (pinfunction "24_24") (pintype "passive"))
      (node (ref "INSTRUCTION_MEMORY_1") (pin "24") (pinfunction "24_24") (pintype "passive"))
      (node (ref "INSTRUCTION_MEMORY_2") (pin "24") (pinfunction "24_24") (pintype "passive"))
      (node (ref "MICRO_COUNTER_LOWER") (pin "13") (pinfunction "13_13") (pintype "passive"))
      (node (ref "USTEP_2") (pin "A") (pinfunction "A_A") (pintype "passive"))
    )
    (net (code "114") (name "Net-(INSTRUCTIONS_EXTENSIONC-1)") (class "Default")
      (node (ref "INSTRUCTIONS_EXTENSION") (pin "11") (pinfunction "1_11") (pintype "passive"))
      (node (ref "INSTRUCTION_MEMORY_0") (pin "21") (pinfunction "21_21") (pintype "passive"))
      (node (ref "INSTRUCTION_MEMORY_1") (pin "21") (pinfunction "21_21") (pintype "passive"))
      (node (ref "INSTRUCTION_MEMORY_2") (pin "21") (pinfunction "21_21") (pintype "passive"))
      (node (ref "MICRO_COUNTER_LOWER") (pin "12") (pinfunction "12_12") (pintype "passive"))
      (node (ref "USTEP_4") (pin "A") (pinfunction "A_A") (pintype "passive"))
    )
    (net (code "115") (name "Net-(INSTRUCTIONS_EXTENSIOND-1)") (class "Default")
      (node (ref "INSTRUCTIONS_EXTENSION") (pin "12") (pinfunction "1_12") (pintype "passive"))
      (node (ref "INSTRUCTION_MEMORY_0") (pin "23") (pinfunction "23_23") (pintype "passive"))
      (node (ref "INSTRUCTION_MEMORY_1") (pin "23") (pinfunction "23_23") (pintype "passive"))
      (node (ref "INSTRUCTION_MEMORY_2") (pin "23") (pinfunction "23_23") (pintype "passive"))
      (node (ref "MICRO_COUNTER_LOWER") (pin "11") (pinfunction "11_11") (pintype "passive"))
      (node (ref "USTEP_3") (pin "A") (pinfunction "A_A") (pintype "passive"))
    )
    (net (code "116") (name "Net-(INSTRUCTIONS_EXTENSIONE-1)") (class "Default")
      (node (ref "INSTRUCTIONS_EXTENSION") (pin "13") (pinfunction "1_13") (pintype "passive"))
      (node (ref "INSTRUCTION_MEMORY_0") (pin "2") (pinfunction "2_2") (pintype "passive"))
      (node (ref "INSTRUCTION_MEMORY_1") (pin "2") (pinfunction "2_2") (pintype "passive"))
      (node (ref "INSTRUCTION_MEMORY_2") (pin "2") (pinfunction "2_2") (pintype "passive"))
      (node (ref "MICRO_COUNTER_UPPER") (pin "14") (pinfunction "14_14") (pintype "passive"))
      (node (ref "USTEP_5") (pin "A") (pinfunction "A_A") (pintype "passive"))
    )
    (net (code "117") (name "Net-(INSTRUCTIONS_EXTENSIONH-1)") (class "Default")
      (node (ref "INSTRUCTIONS_EXTENSION") (pin "2") (pinfunction "1_2") (pintype "passive"))
      (node (ref "INSTRUCTION_MEMORY_0") (pin "9") (pinfunction "9_9") (pintype "passive"))
      (node (ref "INSTRUCTION_MEMORY_1") (pin "9") (pinfunction "9_9") (pintype "passive"))
      (node (ref "INSTRUCTION_MEMORY_2") (pin "9") (pinfunction "9_9") (pintype "passive"))
      (node (ref "INSTRUC_REGISTER_LOWER") (pin "5") (pinfunction "Q3_5") (pintype "tri_state"))
    )
    (net (code "118") (name "Net-(INSTRUCTIONS_EXTENSIONI-1)") (class "Default")
      (node (ref "INSTRUCTIONS_EXTENSION") (pin "3") (pinfunction "1_3") (pintype "passive"))
      (node (ref "INSTRUCTION_MEMORY_0") (pin "8") (pinfunction "8_8") (pintype "passive"))
      (node (ref "INSTRUCTION_MEMORY_1") (pin "8") (pinfunction "8_8") (pintype "passive"))
      (node (ref "INSTRUCTION_MEMORY_2") (pin "8") (pinfunction "8_8") (pintype "passive"))
      (node (ref "INSTRUC_REGISTER_LOWER") (pin "4") (pinfunction "Q2_4") (pintype "tri_state"))
    )
    (net (code "119") (name "Net-(INSTRUCTIONS_EXTENSIONJ-1)") (class "Default")
      (node (ref "INSTRUCTIONS_EXTENSION") (pin "4") (pinfunction "1_4") (pintype "passive"))
      (node (ref "INSTRUCTION_MEMORY_0") (pin "7") (pinfunction "7_7") (pintype "passive"))
      (node (ref "INSTRUCTION_MEMORY_1") (pin "7") (pinfunction "7_7") (pintype "passive"))
      (node (ref "INSTRUCTION_MEMORY_2") (pin "7") (pinfunction "7_7") (pintype "passive"))
      (node (ref "INSTRUC_REGISTER_LOWER") (pin "3") (pinfunction "Q1_3") (pintype "tri_state"))
    )
    (net (code "120") (name "Net-(INSTRUCTIONS_EXTENSIONK-1)") (class "Default")
      (node (ref "INSTRUCTIONS_EXTENSION") (pin "5") (pinfunction "1_5") (pintype "passive"))
      (node (ref "INSTRUCTION_MEMORY_0") (pin "6") (pinfunction "6_6") (pintype "passive"))
      (node (ref "INSTRUCTION_MEMORY_1") (pin "6") (pinfunction "6_6") (pintype "passive"))
      (node (ref "INSTRUCTION_MEMORY_2") (pin "6") (pinfunction "6_6") (pintype "passive"))
      (node (ref "INSTRUC_REGISTER_UPPER") (pin "6") (pinfunction "Q4_6") (pintype "tri_state"))
    )
    (net (code "121") (name "Net-(INSTRUCTIONS_EXTENSIONL-1)") (class "Default")
      (node (ref "INSTRUCTIONS_EXTENSION") (pin "6") (pinfunction "1_6") (pintype "passive"))
      (node (ref "INSTRUCTION_MEMORY_0") (pin "5") (pinfunction "5_5") (pintype "passive"))
      (node (ref "INSTRUCTION_MEMORY_1") (pin "5") (pinfunction "5_5") (pintype "passive"))
      (node (ref "INSTRUCTION_MEMORY_2") (pin "5") (pinfunction "5_5") (pintype "passive"))
      (node (ref "INSTRUC_REGISTER_UPPER") (pin "5") (pinfunction "Q3_5") (pintype "tri_state"))
    )
    (net (code "122") (name "Net-(INSTRUCTIONS_EXTENSIONM-1)") (class "Default")
      (node (ref "INSTRUCTIONS_EXTENSION") (pin "7") (pinfunction "1_7") (pintype "passive"))
      (node (ref "INSTRUCTION_MEMORY_0") (pin "4") (pinfunction "4_4") (pintype "passive"))
      (node (ref "INSTRUCTION_MEMORY_1") (pin "4") (pinfunction "4_4") (pintype "passive"))
      (node (ref "INSTRUCTION_MEMORY_2") (pin "4") (pinfunction "4_4") (pintype "passive"))
      (node (ref "INSTRUC_REGISTER_UPPER") (pin "4") (pinfunction "Q2_4") (pintype "tri_state"))
    )
    (net (code "123") (name "Net-(INSTRUCTIONS_EXTENSIONN-1)") (class "Default")
      (node (ref "INSTRUCTIONS_EXTENSION") (pin "8") (pinfunction "1_8") (pintype "passive"))
      (node (ref "INSTRUCTION_MEMORY_0") (pin "3") (pinfunction "3_3") (pintype "passive"))
      (node (ref "INSTRUCTION_MEMORY_1") (pin "3") (pinfunction "3_3") (pintype "passive"))
      (node (ref "INSTRUCTION_MEMORY_2") (pin "3") (pinfunction "3_3") (pintype "passive"))
      (node (ref "INSTRUC_REGISTER_UPPER") (pin "3") (pinfunction "Q1_3") (pintype "tri_state"))
    )
    (net (code "124") (name "Net-(INSTRUCTIONS_EXTENSIONO-1)") (class "Default")
      (node (ref "INSTRUCTIONS_EXTENSION") (pin "9") (pinfunction "1_9") (pintype "passive"))
      (node (ref "INSTRUCTION_MEMORY_0") (pin "25") (pinfunction "25_25") (pintype "passive"))
      (node (ref "INSTRUCTION_MEMORY_1") (pin "25") (pinfunction "25_25") (pintype "passive"))
      (node (ref "INSTRUCTION_MEMORY_2") (pin "25") (pinfunction "25_25") (pintype "passive"))
      (node (ref "MICRO_COUNTER_LOWER") (pin "14") (pinfunction "14_14") (pintype "passive"))
      (node (ref "USTEP_1") (pin "A") (pinfunction "A_A") (pintype "passive"))
    )
    (net (code "125") (name "Net-(INSTRUC_REGISTER_LOWERA-G1)") (class "Default")
      (node (ref "INSTRUC_REGISTER_LOWER") (pin "10") (pinfunction "G2_10") (pintype "input"))
      (node (ref "INSTRUC_REGISTER_LOWER") (pin "9") (pinfunction "G1_9") (pintype "input"))
      (node (ref "INSTRUC_REGISTER_UPPER") (pin "10") (pinfunction "G2_10") (pintype "input"))
      (node (ref "INSTRUC_REGISTER_UPPER") (pin "9") (pinfunction "G1_9") (pintype "input"))
      (node (ref "SELECTOR_LOGIC_") (pin "5") (pinfunction "Y1_5") (pintype "output"))
    )
    (net (code "126") (name "Net-(INSTRUC_REGISTER_LOWERA-Q4)") (class "Default")
      (node (ref "INSTRUCTIONS_EXTENSION") (pin "1") (pinfunction "1_1") (pintype "passive"))
      (node (ref "INSTRUCTION_MEMORY_0") (pin "10") (pinfunction "10_10") (pintype "passive"))
      (node (ref "INSTRUCTION_MEMORY_1") (pin "10") (pinfunction "10_10") (pintype "passive"))
      (node (ref "INSTRUCTION_MEMORY_2") (pin "10") (pinfunction "10_10") (pintype "passive"))
      (node (ref "INSTRUC_REGISTER_LOWER") (pin "6") (pinfunction "Q4_6") (pintype "tri_state"))
    )
    (net (code "127") (name "Net-(INVERTED_CLK_LED-C)") (class "Default")
      (node (ref "INVERTED_CLK_LED") (pin "K") (pinfunction "C_K") (pintype "passive"))
      (node (ref "R45") (pin "2") (pinfunction "2_2") (pintype "passive"))
    )
    (net (code "128") (name "Net-(KEYBOARDB-1)") (class "Default")
      (node (ref "KEYBOARD") (pin "2") (pinfunction "1_2") (pintype "passive"))
      (node (ref "KEYBOARD_SHIFT_UPPER") (pin "14") (pinfunction "SER_14") (pintype "input"))
    )
    (net (code "129") (name "Net-(KEYBOARDC-1)") (class "Default")
      (node (ref "KEYBOARD") (pin "3") (pinfunction "1_3") (pintype "passive"))
      (node (ref "NOT_GATE3_") (pin "1") (pinfunction "I_1") (pintype "input"))
    )
    (net (code "130") (name "Net-(KEYBOARD_SHIFT_LOWERA-QA)") (class "Default")
      (node (ref "KEYBOARD_ASCII_TABLE") (pin "9") (pinfunction "9_9") (pintype "passive"))
      (node (ref "KEYBOARD_SHIFT_LOWER") (pin "15") (pinfunction "QA_15") (pintype "tri_state"))
    )
    (net (code "131") (name "Net-(KEYBOARD_SHIFT_LOWERA-QB)") (class "Default")
      (node (ref "KEYBOARD_ASCII_TABLE") (pin "10") (pinfunction "10_10") (pintype "passive"))
      (node (ref "KEYBOARD_SHIFT_LOWER") (pin "1") (pinfunction "QB_1") (pintype "tri_state"))
    )
    (net (code "132") (name "Net-(KEYBOARD_SHIFT_LOWERA-RCK)") (class "Default")
      (node (ref "KEYBOARD_SHIFT_LOWER") (pin "12") (pinfunction "RCK_12") (pintype "input"))
      (node (ref "KEYBOARD_SHIFT_UPPER") (pin "12") (pinfunction "RCK_12") (pintype "input"))
      (node (ref "NOT_GATE3_") (pin "6") (pinfunction "O_6") (pintype "output"))
    )
    (net (code "133") (name "Net-(KEYBOARD_SHIFT_LOWERA-SCK)") (class "Default")
      (node (ref "D1") (pin "A") (pinfunction "A_A") (pintype "passive"))
      (node (ref "KEYBOARD_SHIFT_LOWER") (pin "11") (pinfunction "SCK_11") (pintype "input"))
      (node (ref "KEYBOARD_SHIFT_UPPER") (pin "11") (pinfunction "SCK_11") (pintype "input"))
      (node (ref "NOT_GATE3_") (pin "2") (pinfunction "O_2") (pintype "output"))
      (node (ref "NOT_GATE3_") (pin "5") (pinfunction "I_5") (pintype "input"))
      (node (ref "R6") (pin "1") (pinfunction "1_1") (pintype "passive"))
    )
    (net (code "134") (name "Net-(KEYBOARD_SHIFT_LOWERA-SER)") (class "Default")
      (node (ref "KEYBOARD_SHIFT_LOWER") (pin "14") (pinfunction "SER_14") (pintype "input"))
      (node (ref "KEYBOARD_SHIFT_UPPER") (pin "9") (pinfunction "QH*_9") (pintype "tri_state"))
    )
    (net (code "135") (name "Net-(KEYBOARD_SHIFT_UPPERA-QC)") (class "Default")
      (node (ref "KEYBOARD_ASCII_TABLE") (pin "3") (pinfunction "3_3") (pintype "passive"))
      (node (ref "KEYBOARD_SHIFT_UPPER") (pin "2") (pinfunction "QC_2") (pintype "tri_state"))
    )
    (net (code "136") (name "Net-(KEYBOARD_SHIFT_UPPERA-QD)") (class "Default")
      (node (ref "KEYBOARD_ASCII_TABLE") (pin "4") (pinfunction "4_4") (pintype "passive"))
      (node (ref "KEYBOARD_SHIFT_UPPER") (pin "3") (pinfunction "QD_3") (pintype "tri_state"))
    )
    (net (code "137") (name "Net-(KEYBOARD_SHIFT_UPPERA-QE)") (class "Default")
      (node (ref "KEYBOARD_ASCII_TABLE") (pin "5") (pinfunction "5_5") (pintype "passive"))
      (node (ref "KEYBOARD_SHIFT_UPPER") (pin "4") (pinfunction "QE_4") (pintype "tri_state"))
    )
    (net (code "138") (name "Net-(KEYBOARD_SHIFT_UPPERA-QF)") (class "Default")
      (node (ref "KEYBOARD_ASCII_TABLE") (pin "6") (pinfunction "6_6") (pintype "passive"))
      (node (ref "KEYBOARD_SHIFT_UPPER") (pin "5") (pinfunction "QF_5") (pintype "tri_state"))
    )
    (net (code "139") (name "Net-(KEYBOARD_SHIFT_UPPERA-QG)") (class "Default")
      (node (ref "KEYBOARD_ASCII_TABLE") (pin "7") (pinfunction "7_7") (pintype "passive"))
      (node (ref "KEYBOARD_SHIFT_UPPER") (pin "6") (pinfunction "QG_6") (pintype "tri_state"))
    )
    (net (code "140") (name "Net-(KEYBOARD_SHIFT_UPPERA-QH)") (class "Default")
      (node (ref "KEYBOARD_ASCII_TABLE") (pin "8") (pinfunction "8_8") (pintype "passive"))
      (node (ref "KEYBOARD_SHIFT_UPPER") (pin "7") (pinfunction "QH_7") (pintype "tri_state"))
    )
    (net (code "141") (name "Net-(LED_A_REG_1-C)") (class "Default")
      (node (ref "LED_A_REG_1") (pin "K") (pinfunction "C_K") (pintype "passive"))
      (node (ref "R53") (pin "1") (pinfunction "1_1") (pintype "passive"))
    )
    (net (code "142") (name "Net-(LED_A_REG_2-C)") (class "Default")
      (node (ref "LED_A_REG_2") (pin "K") (pinfunction "C_K") (pintype "passive"))
      (node (ref "R54") (pin "1") (pinfunction "1_1") (pintype "passive"))
    )
    (net (code "143") (name "Net-(LED_A_REG_3-C)") (class "Default")
      (node (ref "LED_A_REG_3") (pin "K") (pinfunction "C_K") (pintype "passive"))
      (node (ref "R55") (pin "1") (pinfunction "1_1") (pintype "passive"))
    )
    (net (code "144") (name "Net-(LED_A_REG_4-C)") (class "Default")
      (node (ref "LED_A_REG_4") (pin "K") (pinfunction "C_K") (pintype "passive"))
      (node (ref "R56") (pin "1") (pinfunction "1_1") (pintype "passive"))
    )
    (net (code "145") (name "Net-(LED_A_REG_5-C)") (class "Default")
      (node (ref "LED_A_REG_5") (pin "K") (pinfunction "C_K") (pintype "passive"))
      (node (ref "R57") (pin "1") (pinfunction "1_1") (pintype "passive"))
    )
    (net (code "146") (name "Net-(LED_A_REG_6-C)") (class "Default")
      (node (ref "LED_A_REG_6") (pin "K") (pinfunction "C_K") (pintype "passive"))
      (node (ref "R58") (pin "1") (pinfunction "1_1") (pintype "passive"))
    )
    (net (code "147") (name "Net-(LED_A_REG_7-C)") (class "Default")
      (node (ref "LED_A_REG_7") (pin "K") (pinfunction "C_K") (pintype "passive"))
      (node (ref "R59") (pin "1") (pinfunction "1_1") (pintype "passive"))
    )
    (net (code "148") (name "Net-(LED_A_REG_8-C)") (class "Default")
      (node (ref "LED_A_REG_8") (pin "K") (pinfunction "C_K") (pintype "passive"))
      (node (ref "R60") (pin "1") (pinfunction "1_1") (pintype "passive"))
    )
    (net (code "149") (name "Net-(LED_B_REG_1-C)") (class "Default")
      (node (ref "LED_B_REG_1") (pin "K") (pinfunction "C_K") (pintype "passive"))
      (node (ref "R61") (pin "1") (pinfunction "1_1") (pintype "passive"))
    )
    (net (code "150") (name "Net-(LED_B_REG_2-C)") (class "Default")
      (node (ref "LED_B_REG_2") (pin "K") (pinfunction "C_K") (pintype "passive"))
      (node (ref "R62") (pin "1") (pinfunction "1_1") (pintype "passive"))
    )
    (net (code "151") (name "Net-(LED_B_REG_3-C)") (class "Default")
      (node (ref "LED_B_REG_3") (pin "K") (pinfunction "C_K") (pintype "passive"))
      (node (ref "R63") (pin "1") (pinfunction "1_1") (pintype "passive"))
    )
    (net (code "152") (name "Net-(LED_B_REG_4-C)") (class "Default")
      (node (ref "LED_B_REG_4") (pin "K") (pinfunction "C_K") (pintype "passive"))
      (node (ref "R64") (pin "1") (pinfunction "1_1") (pintype "passive"))
    )
    (net (code "153") (name "Net-(LED_B_REG_5-C)") (class "Default")
      (node (ref "LED_B_REG_5") (pin "K") (pinfunction "C_K") (pintype "passive"))
      (node (ref "R65") (pin "1") (pinfunction "1_1") (pintype "passive"))
    )
    (net (code "154") (name "Net-(LED_B_REG_6-C)") (class "Default")
      (node (ref "LED_B_REG_6") (pin "K") (pinfunction "C_K") (pintype "passive"))
      (node (ref "R66") (pin "1") (pinfunction "1_1") (pintype "passive"))
    )
    (net (code "155") (name "Net-(LED_B_REG_7-C)") (class "Default")
      (node (ref "LED_B_REG_7") (pin "K") (pinfunction "C_K") (pintype "passive"))
      (node (ref "R67") (pin "1") (pinfunction "1_1") (pintype "passive"))
    )
    (net (code "156") (name "Net-(LED_B_REG_8-C)") (class "Default")
      (node (ref "LED_B_REG_8") (pin "K") (pinfunction "C_K") (pintype "passive"))
      (node (ref "R68") (pin "1") (pinfunction "1_1") (pintype "passive"))
    )
    (net (code "157") (name "Net-(MICRO_COUNTER_LOWER-Pad15)") (class "Default")
      (node (ref "MICRO_COUNTER_LOWER") (pin "15") (pinfunction "15_15") (pintype "passive"))
      (node (ref "MICRO_COUNTER_UPPER") (pin "10") (pinfunction "10_10") (pintype "passive"))
    )
    (net (code "158") (name "Net-(NOR_GATE_A-I0)") (class "Default")
      (node (ref "NOR_GATE_") (pin "2") (pinfunction "I0_2") (pintype "input"))
      (node (ref "NOT_GATE_") (pin "6") (pinfunction "O_6") (pintype "output"))
    )
    (net (code "159") (name "Net-(NOR_GATE_A-I1)") (class "Default")
      (node (ref "C4") (pin "+") (pinfunction "+_+") (pintype "passive"))
      (node (ref "D1") (pin "C") (pinfunction "C_C") (pintype "passive"))
      (node (ref "NOR_GATE_") (pin "3") (pinfunction "I1_3") (pintype "input"))
      (node (ref "NOT_GATE_") (pin "3") (pinfunction "I_3") (pintype "input"))
      (node (ref "R6") (pin "2") (pinfunction "2_2") (pintype "passive"))
    )
    (net (code "160") (name "Net-(NOR_GATE_B-I0)") (class "Default")
      (node (ref "NOR_GATE_") (pin "5") (pinfunction "I0_5") (pintype "input"))
      (node (ref "SELECTOR_LOGIC_") (pin "7") (pinfunction "Y3_7") (pintype "output"))
    )
    (net (code "161") (name "Net-(NOR_GATE_B-I1)") (class "Default")
      (node (ref "NOR_GATE_") (pin "6") (pinfunction "I1_6") (pintype "input"))
      (node (ref "XOR_GATE_2") (pin "11") (pinfunction "O_11") (pintype "output"))
    )
    (net (code "162") (name "Net-(NOT_GATE1_A-I)") (class "Default")
      (node (ref "NOT_GATE1_") (pin "1") (pinfunction "I_1") (pintype "input"))
      (node (ref "SELECTOR_BRANCH_") (pin "7") (pinfunction "Y3_7") (pintype "output"))
    )
    (net (code "163") (name "Net-(NOT_GATE1_C-I)") (class "Default")
      (node (ref "NOT_GATE1_") (pin "5") (pinfunction "I_5") (pintype "input"))
      (node (ref "SELECTOR_PARAM_") (pin "10") (pinfunction "Y2_10") (pintype "output"))
    )
    (net (code "164") (name "Net-(NOT_GATE1_D-I)") (class "Default")
      (node (ref "NOT_GATE1_") (pin "9") (pinfunction "I_9") (pintype "input"))
      (node (ref "SELECTOR_PARAM_") (pin "11") (pinfunction "Y1_11") (pintype "output"))
    )
    (net (code "165") (name "Net-(NOT_GATE1_D-O)") (class "Default")
      (node (ref "NOT_GATE1_") (pin "8") (pinfunction "O_8") (pintype "output"))
      (node (ref "OUTPUT_BUFFER_MEMORY") (pin "19") (pinfunction "G_19") (pintype "input"))
    )
    (net (code "166") (name "Net-(NOT_GATE1_E-O)") (class "Default")
      (node (ref "INVERTED_CLK_LED") (pin "A") (pinfunction "A_A") (pintype "passive"))
      (node (ref "MICRO_COUNTER_LOWER") (pin "2") (pinfunction "2_2") (pintype "passive"))
      (node (ref "MICRO_COUNTER_UPPER") (pin "2") (pinfunction "2_2") (pintype "passive"))
      (node (ref "NOT_GATE1_") (pin "10") (pinfunction "O_10") (pintype "output"))
    )
    (net (code "167") (name "Net-(NOT_GATE1_F-I)") (class "Default")
      (node (ref "INSTRUCTION_MEMORY_1") (pin "16") (pinfunction "16_16") (pintype "passive"))
      (node (ref "NOT_GATE1_") (pin "13") (pinfunction "I_13") (pintype "input"))
    )
    (net (code "168") (name "Net-(NOT_GATE2_A-I)") (class "Default")
      (node (ref "NOT_GATE2_") (pin "1") (pinfunction "I_1") (pintype "input"))
      (node (ref "SELECTOR_PARAM_") (pin "5") (pinfunction "Y1_5") (pintype "output"))
    )
    (net (code "169") (name "Net-(NOT_GATE2_A-O)") (class "Default")
      (node (ref "NOT_GATE2_") (pin "2") (pinfunction "O_2") (pintype "output"))
      (node (ref "OUTPUT_BUFFER_PARAM_REG") (pin "19") (pinfunction "G_19") (pintype "input"))
    )
    (net (code "170") (name "Net-(NOT_GATE2_B-I)") (class "Default")
      (node (ref "NOT_GATE2_") (pin "3") (pinfunction "I_3") (pintype "input"))
      (node (ref "SELECTOR_PARAM_") (pin "6") (pinfunction "Y2_6") (pintype "output"))
    )
    (net (code "171") (name "Net-(NOT_GATE2_B-O)") (class "Default")
      (node (ref "NOT_GATE2_") (pin "4") (pinfunction "O_4") (pintype "output"))
      (node (ref "REG_PARAM_LOWER") (pin "10") (pinfunction "G2_10") (pintype "input"))
      (node (ref "REG_PARAM_LOWER") (pin "9") (pinfunction "G1_9") (pintype "input"))
      (node (ref "REG_PARAM_UPPER") (pin "10") (pinfunction "G2_10") (pintype "input"))
      (node (ref "REG_PARAM_UPPER") (pin "9") (pinfunction "G1_9") (pintype "input"))
    )
    (net (code "172") (name "Net-(NOT_GATE2_C-I)") (class "Default")
      (node (ref "NOT_GATE2_") (pin "5") (pinfunction "I_5") (pintype "input"))
      (node (ref "SELECTOR_BRANCH_") (pin "6") (pinfunction "Y2_6") (pintype "output"))
    )
    (net (code "173") (name "Net-(NOT_GATE2_D-I)") (class "Default")
      (node (ref "NOT_GATE2_") (pin "9") (pinfunction "I_9") (pintype "input"))
      (node (ref "SELECTOR_BRANCH_") (pin "5") (pinfunction "Y1_5") (pintype "output"))
    )
    (net (code "174") (name "Net-(NOT_GATE2_E-I)") (class "Default")
      (node (ref "NOT_GATE2_") (pin "11") (pinfunction "I_11") (pintype "input"))
      (node (ref "SELECTOR_STACK_") (pin "7") (pinfunction "Y3_7") (pintype "output"))
    )
    (net (code "175") (name "Net-(NOT_GATE2_E-O)") (class "Default")
      (node (ref "NOT_GATE2_") (pin "10") (pinfunction "O_10") (pintype "output"))
      (node (ref "PROGRAM_COUNTER_LOWER") (pin "10") (pinfunction "10_10") (pintype "passive"))
    )
    (net (code "176") (name "Net-(NOT_GATE2_F-I)") (class "Default")
      (node (ref "NOT_GATE2_") (pin "13") (pinfunction "I_13") (pintype "input"))
      (node (ref "RAM") (pin "22") (pinfunction "22_22") (pintype "passive"))
      (node (ref "SELECTOR_INSRUCTION_UPPER") (pin "7") (pinfunction "2Y_7") (pintype "output"))
    )
    (net (code "177") (name "Net-(NOT_GATE2_F-O)") (class "Default")
      (node (ref "NOT_GATE2_") (pin "12") (pinfunction "O_12") (pintype "output"))
      (node (ref "RAM") (pin "27") (pinfunction "27_27") (pintype "passive"))
    )
    (net (code "178") (name "Net-(NOT_GATE3_B-I)") (class "Default")
      (node (ref "INSTRUCTION_MEMORY_1") (pin "13") (pinfunction "13_13") (pintype "passive"))
      (node (ref "NOT_GATE3_") (pin "3") (pinfunction "I_3") (pintype "input"))
    )
    (net (code "179") (name "Net-(NOT_GATE3_B-O)") (class "Default")
      (node (ref "NOT_GATE3_") (pin "4") (pinfunction "O_4") (pintype "output"))
      (node (ref "OUTPUT_BUFFER_ALU") (pin "19") (pinfunction "G_19") (pintype "input"))
    )
    (net (code "180") (name "Net-(NOT_GATE3_D-I)") (class "Default")
      (node (ref "NOT_GATE3_") (pin "9") (pinfunction "I_9") (pintype "input"))
      (node (ref "NOT_GATE_") (pin "4") (pinfunction "O_4") (pintype "output"))
    )
    (net (code "181") (name "Net-(NOT_GATE3_D-O)") (class "Default")
      (node (ref "NOT_GATE3_") (pin "11") (pinfunction "I_11") (pintype "input"))
      (node (ref "NOT_GATE3_") (pin "8") (pinfunction "O_8") (pintype "output"))
    )
    (net (code "182") (name "Net-(NOT_GATE3_E-O)") (class "Default")
      (node (ref "NOT_GATE3_") (pin "10") (pinfunction "O_10") (pintype "output"))
      (node (ref "NOT_GATE3_") (pin "13") (pinfunction "I_13") (pintype "input"))
    )
    (net (code "183") (name "Net-(NOT_GATE3_F-O)") (class "Default")
      (node (ref "NOT_GATE3_") (pin "12") (pinfunction "O_12") (pintype "output"))
      (node (ref "NOT_GATE_") (pin "5") (pinfunction "I_5") (pintype "input"))
    )
    (net (code "184") (name "Net-(NOT_GATE4_A-I)") (class "Default")
      (node (ref "NOT_GATE4_") (pin "1") (pinfunction "I_1") (pintype "input"))
      (node (ref "SELECTOR_BRANCH_") (pin "4") (pinfunction "Y0_4") (pintype "output"))
    )
    (net (code "185") (name "Net-(NOT_GATE4_B-I)") (class "Default")
      (node (ref "NOT_GATE4_") (pin "3") (pinfunction "I_3") (pintype "input"))
      (node (ref "SELECTOR_INSRUCTION_UPPER") (pin "4") (pinfunction "1Y_4") (pintype "output"))
    )
    (net (code "186") (name "Net-(NOT_GATE4_B-O)") (class "Default")
      (node (ref "NOT_GATE4_") (pin "4") (pinfunction "O_4") (pintype "output"))
      (node (ref "RAM_ADDR_LOWER") (pin "10") (pinfunction "G2_10") (pintype "input"))
      (node (ref "RAM_ADDR_LOWER") (pin "9") (pinfunction "G1_9") (pintype "input"))
      (node (ref "RAM_ADDR_UPPER") (pin "10") (pinfunction "G2_10") (pintype "input"))
      (node (ref "RAM_ADDR_UPPER") (pin "9") (pinfunction "G1_9") (pintype "input"))
    )
    (net (code "187") (name "Net-(NOT_GATE4_C-O)") (class "Default")
      (node (ref "NOT_GATE4_") (pin "6") (pinfunction "O_6") (pintype "output"))
      (node (ref "PROGRAM_COUNTER_LOWER") (pin "9") (pinfunction "9_9") (pintype "passive"))
      (node (ref "PROGRAM_COUNTER_UPPER") (pin "9") (pinfunction "9_9") (pintype "passive"))
    )
    (net (code "188") (name "Net-(NOT_GATE4_D-O)") (class "Default")
      (node (ref "MICRO_COUNTER_LOWER") (pin "9") (pinfunction "9_9") (pintype "passive"))
      (node (ref "MICRO_COUNTER_UPPER") (pin "9") (pinfunction "9_9") (pintype "passive"))
      (node (ref "NOT_GATE4_") (pin "8") (pinfunction "O_8") (pintype "output"))
    )
    (net (code "189") (name "Net-(NOT_GATE4_E-I)") (class "Default")
      (node (ref "INSTRUCTION_MEMORY_1") (pin "17") (pinfunction "17_17") (pintype "passive"))
      (node (ref "NOT_GATE4_") (pin "11") (pinfunction "I_11") (pintype "input"))
    )
    (net (code "190") (name "Net-(NOT_GATE4_E-O)") (class "Default")
      (node (ref "NOT_GATE4_") (pin "10") (pinfunction "O_10") (pintype "output"))
      (node (ref "OUTPUT_BUFFER_RAM") (pin "19") (pinfunction "G_19") (pintype "input"))
    )
    (net (code "191") (name "Net-(NOT_GATE4_F-I)") (class "Default")
      (node (ref "NOT_GATE4_") (pin "13") (pinfunction "I_13") (pintype "input"))
      (node (ref "SELECTOR_BRANCH_") (pin "9") (pinfunction "Y3_9") (pintype "output"))
    )
    (net (code "192") (name "Net-(NOT_GATE_A-I)") (class "Default")
      (node (ref "INSTRUCTION_MEMORY_2") (pin "11") (pinfunction "11_11") (pintype "passive"))
      (node (ref "NOT_GATE_") (pin "1") (pinfunction "I_1") (pintype "input"))
    )
    (net (code "193") (name "Net-(NOT_GATE_A-O)") (class "Default")
      (node (ref "NOT_GATE_") (pin "2") (pinfunction "O_2") (pintype "output"))
      (node (ref "OUTPUT_BUFFER_FLAGS") (pin "19") (pinfunction "G_19") (pintype "input"))
    )
    (net (code "194") (name "Net-(NOT_GATE_D-I)") (class "Default")
      (node (ref "NOT_GATE_") (pin "9") (pinfunction "I_9") (pintype "input"))
      (node (ref "SELECTOR_STACK_") (pin "5") (pinfunction "Y1_5") (pintype "output"))
    )
    (net (code "195") (name "Net-(OUTPUT_BUFFER_CALC_REGA-A1)") (class "Default")
      (node (ref "LED_B_REG_8") (pin "A") (pinfunction "A_A") (pintype "passive"))
      (node (ref "OUTPUT_BUFFER_CALC_REG") (pin "2") (pinfunction "A1_2") (pintype "bidirectional"))
      (node (ref "REG_CALC_UPPER") (pin "3") (pinfunction "Q1_3") (pintype "tri_state"))
      (node (ref "SUBTRACT_INVRTR_UPPER_") (pin "2") (pinfunction "I1_2") (pintype "input"))
    )
    (net (code "196") (name "Net-(OUTPUT_BUFFER_CALC_REGA-A2)") (class "Default")
      (node (ref "LED_B_REG_7") (pin "A") (pinfunction "A_A") (pintype "passive"))
      (node (ref "OUTPUT_BUFFER_CALC_REG") (pin "3") (pinfunction "A2_3") (pintype "bidirectional"))
      (node (ref "REG_CALC_UPPER") (pin "4") (pinfunction "Q2_4") (pintype "tri_state"))
      (node (ref "SUBTRACT_INVRTR_UPPER_") (pin "5") (pinfunction "I1_5") (pintype "input"))
    )
    (net (code "197") (name "Net-(OUTPUT_BUFFER_CALC_REGA-A3)") (class "Default")
      (node (ref "LED_B_REG_6") (pin "A") (pinfunction "A_A") (pintype "passive"))
      (node (ref "OUTPUT_BUFFER_CALC_REG") (pin "4") (pinfunction "A3_4") (pintype "bidirectional"))
      (node (ref "REG_CALC_UPPER") (pin "5") (pinfunction "Q3_5") (pintype "tri_state"))
      (node (ref "SUBTRACT_INVRTR_UPPER_") (pin "10") (pinfunction "I1_10") (pintype "input"))
    )
    (net (code "198") (name "Net-(OUTPUT_BUFFER_CALC_REGA-A4)") (class "Default")
      (node (ref "LED_B_REG_5") (pin "A") (pinfunction "A_A") (pintype "passive"))
      (node (ref "OUTPUT_BUFFER_CALC_REG") (pin "5") (pinfunction "A4_5") (pintype "bidirectional"))
      (node (ref "REG_CALC_UPPER") (pin "6") (pinfunction "Q4_6") (pintype "tri_state"))
      (node (ref "SUBTRACT_INVRTR_UPPER_") (pin "13") (pinfunction "I1_13") (pintype "input"))
    )
    (net (code "199") (name "Net-(OUTPUT_BUFFER_CALC_REGA-A5)") (class "Default")
      (node (ref "LED_B_REG_4") (pin "A") (pinfunction "A_A") (pintype "passive"))
      (node (ref "OUTPUT_BUFFER_CALC_REG") (pin "6") (pinfunction "A5_6") (pintype "bidirectional"))
      (node (ref "REG_CALC_LOWER") (pin "3") (pinfunction "Q1_3") (pintype "tri_state"))
      (node (ref "SUBTRACT_INVRTR_LOWER_") (pin "2") (pinfunction "I1_2") (pintype "input"))
    )
    (net (code "200") (name "Net-(OUTPUT_BUFFER_CALC_REGA-A6)") (class "Default")
      (node (ref "LED_B_REG_3") (pin "A") (pinfunction "A_A") (pintype "passive"))
      (node (ref "OUTPUT_BUFFER_CALC_REG") (pin "7") (pinfunction "A6_7") (pintype "bidirectional"))
      (node (ref "REG_CALC_LOWER") (pin "4") (pinfunction "Q2_4") (pintype "tri_state"))
      (node (ref "SUBTRACT_INVRTR_LOWER_") (pin "5") (pinfunction "I1_5") (pintype "input"))
    )
    (net (code "201") (name "Net-(OUTPUT_BUFFER_CALC_REGA-A7)") (class "Default")
      (node (ref "LED_B_REG_2") (pin "A") (pinfunction "A_A") (pintype "passive"))
      (node (ref "OUTPUT_BUFFER_CALC_REG") (pin "8") (pinfunction "A7_8") (pintype "bidirectional"))
      (node (ref "REG_CALC_LOWER") (pin "5") (pinfunction "Q3_5") (pintype "tri_state"))
      (node (ref "SUBTRACT_INVRTR_LOWER_") (pin "10") (pinfunction "I1_10") (pintype "input"))
    )
    (net (code "202") (name "Net-(OUTPUT_BUFFER_CALC_REGA-A8)") (class "Default")
      (node (ref "LED_B_REG_1") (pin "A") (pinfunction "A_A") (pintype "passive"))
      (node (ref "OUTPUT_BUFFER_CALC_REG") (pin "9") (pinfunction "A8_9") (pintype "bidirectional"))
      (node (ref "REG_CALC_LOWER") (pin "6") (pinfunction "Q4_6") (pintype "tri_state"))
      (node (ref "SUBTRACT_INVRTR_LOWER_") (pin "13") (pinfunction "I1_13") (pintype "input"))
    )
    (net (code "203") (name "Net-(OUTPUT_BUFFER_CALC_REGA-G)") (class "Default")
      (node (ref "OUTPUT_BUFFER_CALC_REG") (pin "19") (pinfunction "G_19") (pintype "input"))
      (node (ref "SELECTOR_LOGIC_") (pin "11") (pinfunction "Y1_11") (pintype "output"))
    )
    (net (code "204") (name "Net-(OUTPUT_BUFFER_INSTRUCTIONA-A1)") (class "Default")
      (node (ref "INSTRUCTION_MEMORY_0") (pin "11") (pinfunction "11_11") (pintype "passive"))
      (node (ref "OUTPUT_BUFFER_INSTRUCTION") (pin "2") (pinfunction "A1_2") (pintype "bidirectional"))
      (node (ref "SELECTOR_INSRUCTION_LOWER") (pin "13") (pinfunction "4B_13") (pintype "input"))
    )
    (net (code "205") (name "Net-(OUTPUT_BUFFER_INSTRUCTIONA-A2)") (class "Default")
      (node (ref "INSTRUCTION_MEMORY_0") (pin "12") (pinfunction "12_12") (pintype "passive"))
      (node (ref "OUTPUT_BUFFER_INSTRUCTION") (pin "3") (pinfunction "A2_3") (pintype "bidirectional"))
      (node (ref "SELECTOR_INSRUCTION_LOWER") (pin "10") (pinfunction "3B_10") (pintype "input"))
    )
    (net (code "206") (name "Net-(OUTPUT_BUFFER_INSTRUCTIONA-A3)") (class "Default")
      (node (ref "INSTRUCTION_MEMORY_0") (pin "13") (pinfunction "13_13") (pintype "passive"))
      (node (ref "OUTPUT_BUFFER_INSTRUCTION") (pin "4") (pinfunction "A3_4") (pintype "bidirectional"))
      (node (ref "SELECTOR_INSRUCTION_LOWER") (pin "6") (pinfunction "2B_6") (pintype "input"))
    )
    (net (code "207") (name "Net-(OUTPUT_BUFFER_INSTRUCTIONA-A4)") (class "Default")
      (node (ref "INSTRUCTION_MEMORY_0") (pin "15") (pinfunction "15_15") (pintype "passive"))
      (node (ref "OUTPUT_BUFFER_INSTRUCTION") (pin "5") (pinfunction "A4_5") (pintype "bidirectional"))
      (node (ref "SELECTOR_INSRUCTION_LOWER") (pin "3") (pinfunction "1B_3") (pintype "input"))
    )
    (net (code "208") (name "Net-(OUTPUT_BUFFER_INSTRUCTIONA-A5)") (class "Default")
      (node (ref "INSTRUCTION_MEMORY_0") (pin "16") (pinfunction "16_16") (pintype "passive"))
      (node (ref "OUTPUT_BUFFER_INSTRUCTION") (pin "6") (pinfunction "A5_6") (pintype "bidirectional"))
      (node (ref "SELECTOR_INSRUCTION_UPPER") (pin "13") (pinfunction "4B_13") (pintype "input"))
    )
    (net (code "209") (name "Net-(OUTPUT_BUFFER_INSTRUCTIONA-A6)") (class "Default")
      (node (ref "INSTRUCTION_MEMORY_0") (pin "17") (pinfunction "17_17") (pintype "passive"))
      (node (ref "OUTPUT_BUFFER_INSTRUCTION") (pin "7") (pinfunction "A6_7") (pintype "bidirectional"))
      (node (ref "SELECTOR_INSRUCTION_UPPER") (pin "10") (pinfunction "3B_10") (pintype "input"))
    )
    (net (code "210") (name "Net-(OUTPUT_BUFFER_INSTRUCTIONA-A7)") (class "Default")
      (node (ref "INSTRUCTION_MEMORY_0") (pin "18") (pinfunction "18_18") (pintype "passive"))
      (node (ref "OUTPUT_BUFFER_INSTRUCTION") (pin "8") (pinfunction "A7_8") (pintype "bidirectional"))
      (node (ref "SELECTOR_INSRUCTION_UPPER") (pin "6") (pinfunction "2B_6") (pintype "input"))
    )
    (net (code "211") (name "Net-(OUTPUT_BUFFER_INSTRUCTIONA-A8)") (class "Default")
      (node (ref "INSTRUCTION_MEMORY_0") (pin "19") (pinfunction "19_19") (pintype "passive"))
      (node (ref "OUTPUT_BUFFER_INSTRUCTION") (pin "9") (pinfunction "A8_9") (pintype "bidirectional"))
      (node (ref "SELECTOR_INSRUCTION_UPPER") (pin "3") (pinfunction "1B_3") (pintype "input"))
    )
    (net (code "212") (name "Net-(OUTPUT_BUFFER_INSTRUCTIONA-G)") (class "Default")
      (node (ref "OUTPUT_BUFFER_INSTRUCTION") (pin "19") (pinfunction "G_19") (pintype "input"))
      (node (ref "SELECTOR_INSRUCTION_LOWER") (pin "1") (pinfunction "~{A}/B_1") (pintype "input"))
      (node (ref "SELECTOR_INSRUCTION_UPPER") (pin "1") (pinfunction "~{A}/B_1") (pintype "input"))
      (node (ref "SELECTOR_LOGIC_") (pin "6") (pinfunction "Y2_6") (pintype "output"))
    )
    (net (code "213") (name "Net-(OUTPUT_BUFFER_KEYBOARDA-B1)") (class "Default")
      (node (ref "KEYBOARD_ASCII_TABLE") (pin "11") (pinfunction "11_11") (pintype "passive"))
      (node (ref "OUTPUT_BUFFER_KEYBOARD") (pin "18") (pinfunction "B1_18") (pintype "bidirectional"))
    )
    (net (code "214") (name "Net-(OUTPUT_BUFFER_KEYBOARDA-B2)") (class "Default")
      (node (ref "KEYBOARD_ASCII_TABLE") (pin "12") (pinfunction "12_12") (pintype "passive"))
      (node (ref "OUTPUT_BUFFER_KEYBOARD") (pin "17") (pinfunction "B2_17") (pintype "bidirectional"))
    )
    (net (code "215") (name "Net-(OUTPUT_BUFFER_KEYBOARDA-B3)") (class "Default")
      (node (ref "KEYBOARD_ASCII_TABLE") (pin "13") (pinfunction "13_13") (pintype "passive"))
      (node (ref "OUTPUT_BUFFER_KEYBOARD") (pin "16") (pinfunction "B3_16") (pintype "bidirectional"))
    )
    (net (code "216") (name "Net-(OUTPUT_BUFFER_KEYBOARDA-B4)") (class "Default")
      (node (ref "KEYBOARD_ASCII_TABLE") (pin "15") (pinfunction "15_15") (pintype "passive"))
      (node (ref "OUTPUT_BUFFER_KEYBOARD") (pin "15") (pinfunction "B4_15") (pintype "bidirectional"))
    )
    (net (code "217") (name "Net-(OUTPUT_BUFFER_KEYBOARDA-B5)") (class "Default")
      (node (ref "KEYBOARD_ASCII_TABLE") (pin "16") (pinfunction "16_16") (pintype "passive"))
      (node (ref "OUTPUT_BUFFER_KEYBOARD") (pin "14") (pinfunction "B5_14") (pintype "bidirectional"))
    )
    (net (code "218") (name "Net-(OUTPUT_BUFFER_KEYBOARDA-B6)") (class "Default")
      (node (ref "KEYBOARD_ASCII_TABLE") (pin "17") (pinfunction "17_17") (pintype "passive"))
      (node (ref "OUTPUT_BUFFER_KEYBOARD") (pin "13") (pinfunction "B6_13") (pintype "bidirectional"))
    )
    (net (code "219") (name "Net-(OUTPUT_BUFFER_KEYBOARDA-B7)") (class "Default")
      (node (ref "KEYBOARD_ASCII_TABLE") (pin "18") (pinfunction "18_18") (pintype "passive"))
      (node (ref "OUTPUT_BUFFER_KEYBOARD") (pin "12") (pinfunction "B7_12") (pintype "bidirectional"))
    )
    (net (code "220") (name "Net-(OUTPUT_BUFFER_KEYBOARDA-B8)") (class "Default")
      (node (ref "KEYBOARD_ASCII_TABLE") (pin "19") (pinfunction "19_19") (pintype "passive"))
      (node (ref "OUTPUT_BUFFER_KEYBOARD") (pin "11") (pinfunction "B8_11") (pintype "bidirectional"))
    )
    (net (code "221") (name "Net-(OUTPUT_BUFFER_KEYBOARDA-G)") (class "Default")
      (node (ref "OUTPUT_BUFFER_KEYBOARD") (pin "19") (pinfunction "G_19") (pintype "input"))
      (node (ref "SELECTOR_PARAM_") (pin "9") (pinfunction "Y3_9") (pintype "output"))
    )
    (net (code "222") (name "Net-(OUTPUT_BUFFER_MEMORYA-A1)") (class "Default")
      (node (ref "MEMORY") (pin "19") (pinfunction "19_19") (pintype "passive"))
      (node (ref "OUTPUT_BUFFER_MEMORY") (pin "2") (pinfunction "A1_2") (pintype "bidirectional"))
    )
    (net (code "223") (name "Net-(OUTPUT_BUFFER_MEMORYA-A2)") (class "Default")
      (node (ref "MEMORY") (pin "18") (pinfunction "18_18") (pintype "passive"))
      (node (ref "OUTPUT_BUFFER_MEMORY") (pin "3") (pinfunction "A2_3") (pintype "bidirectional"))
    )
    (net (code "224") (name "Net-(OUTPUT_BUFFER_MEMORYA-A3)") (class "Default")
      (node (ref "MEMORY") (pin "17") (pinfunction "17_17") (pintype "passive"))
      (node (ref "OUTPUT_BUFFER_MEMORY") (pin "4") (pinfunction "A3_4") (pintype "bidirectional"))
    )
    (net (code "225") (name "Net-(OUTPUT_BUFFER_MEMORYA-A4)") (class "Default")
      (node (ref "MEMORY") (pin "16") (pinfunction "16_16") (pintype "passive"))
      (node (ref "OUTPUT_BUFFER_MEMORY") (pin "5") (pinfunction "A4_5") (pintype "bidirectional"))
    )
    (net (code "226") (name "Net-(OUTPUT_BUFFER_MEMORYA-A5)") (class "Default")
      (node (ref "MEMORY") (pin "15") (pinfunction "15_15") (pintype "passive"))
      (node (ref "OUTPUT_BUFFER_MEMORY") (pin "6") (pinfunction "A5_6") (pintype "bidirectional"))
    )
    (net (code "227") (name "Net-(OUTPUT_BUFFER_MEMORYA-A6)") (class "Default")
      (node (ref "MEMORY") (pin "13") (pinfunction "13_13") (pintype "passive"))
      (node (ref "OUTPUT_BUFFER_MEMORY") (pin "7") (pinfunction "A6_7") (pintype "bidirectional"))
    )
    (net (code "228") (name "Net-(OUTPUT_BUFFER_MEMORYA-A7)") (class "Default")
      (node (ref "MEMORY") (pin "12") (pinfunction "12_12") (pintype "passive"))
      (node (ref "OUTPUT_BUFFER_MEMORY") (pin "8") (pinfunction "A7_8") (pintype "bidirectional"))
    )
    (net (code "229") (name "Net-(OUTPUT_BUFFER_MEMORYA-A8)") (class "Default")
      (node (ref "MEMORY") (pin "11") (pinfunction "11_11") (pintype "passive"))
      (node (ref "OUTPUT_BUFFER_MEMORY") (pin "9") (pinfunction "A8_9") (pintype "bidirectional"))
    )
    (net (code "230") (name "Net-(OUTPUT_BUFFER_PARAM_REGA-A1)") (class "Default")
      (node (ref "OUTPUT_BUFFER_PARAM_REG") (pin "2") (pinfunction "A1_2") (pintype "bidirectional"))
      (node (ref "PARAM_LED_8") (pin "A") (pinfunction "A_A") (pintype "passive"))
      (node (ref "REG_PARAM_UPPER") (pin "3") (pinfunction "Q1_3") (pintype "tri_state"))
    )
    (net (code "231") (name "Net-(OUTPUT_BUFFER_PARAM_REGA-A2)") (class "Default")
      (node (ref "OUTPUT_BUFFER_PARAM_REG") (pin "3") (pinfunction "A2_3") (pintype "bidirectional"))
      (node (ref "PARAM_LED_7") (pin "A") (pinfunction "A_A") (pintype "passive"))
      (node (ref "REG_PARAM_UPPER") (pin "4") (pinfunction "Q2_4") (pintype "tri_state"))
    )
    (net (code "232") (name "Net-(OUTPUT_BUFFER_PARAM_REGA-A3)") (class "Default")
      (node (ref "OUTPUT_BUFFER_PARAM_REG") (pin "4") (pinfunction "A3_4") (pintype "bidirectional"))
      (node (ref "PARAM_LED_6") (pin "A") (pinfunction "A_A") (pintype "passive"))
      (node (ref "REG_PARAM_UPPER") (pin "5") (pinfunction "Q3_5") (pintype "tri_state"))
    )
    (net (code "233") (name "Net-(OUTPUT_BUFFER_PARAM_REGA-A4)") (class "Default")
      (node (ref "OUTPUT_BUFFER_PARAM_REG") (pin "5") (pinfunction "A4_5") (pintype "bidirectional"))
      (node (ref "PARAM_LED_5") (pin "A") (pinfunction "A_A") (pintype "passive"))
      (node (ref "REG_PARAM_UPPER") (pin "6") (pinfunction "Q4_6") (pintype "tri_state"))
    )
    (net (code "234") (name "Net-(OUTPUT_BUFFER_PARAM_REGA-A5)") (class "Default")
      (node (ref "OUTPUT_BUFFER_PARAM_REG") (pin "6") (pinfunction "A5_6") (pintype "bidirectional"))
      (node (ref "PARAM_LED_4") (pin "A") (pinfunction "A_A") (pintype "passive"))
      (node (ref "REG_PARAM_LOWER") (pin "3") (pinfunction "Q1_3") (pintype "tri_state"))
    )
    (net (code "235") (name "Net-(OUTPUT_BUFFER_PARAM_REGA-A6)") (class "Default")
      (node (ref "OUTPUT_BUFFER_PARAM_REG") (pin "7") (pinfunction "A6_7") (pintype "bidirectional"))
      (node (ref "PARAM_LED_3") (pin "A") (pinfunction "A_A") (pintype "passive"))
      (node (ref "REG_PARAM_LOWER") (pin "4") (pinfunction "Q2_4") (pintype "tri_state"))
    )
    (net (code "236") (name "Net-(OUTPUT_BUFFER_PARAM_REGA-A7)") (class "Default")
      (node (ref "OUTPUT_BUFFER_PARAM_REG") (pin "8") (pinfunction "A7_8") (pintype "bidirectional"))
      (node (ref "PARAM_LED_2") (pin "A") (pinfunction "A_A") (pintype "passive"))
      (node (ref "REG_PARAM_LOWER") (pin "5") (pinfunction "Q3_5") (pintype "tri_state"))
    )
    (net (code "237") (name "Net-(OUTPUT_BUFFER_PARAM_REGA-A8)") (class "Default")
      (node (ref "OUTPUT_BUFFER_PARAM_REG") (pin "9") (pinfunction "A8_9") (pintype "bidirectional"))
      (node (ref "PARAM_LED_1") (pin "A") (pinfunction "A_A") (pintype "passive"))
      (node (ref "REG_PARAM_LOWER") (pin "6") (pinfunction "Q4_6") (pintype "tri_state"))
    )
    (net (code "238") (name "Net-(OUTPUT_BUFFER_PCA-A1)") (class "Default")
      (node (ref "OUTPUT_BUFFER_PC") (pin "2") (pinfunction "A1_2") (pintype "bidirectional"))
      (node (ref "PC_8") (pin "A") (pinfunction "A_A") (pintype "passive"))
      (node (ref "PROGRAM_COUNTER_UPPER") (pin "11") (pinfunction "11_11") (pintype "passive"))
    )
    (net (code "239") (name "Net-(OUTPUT_BUFFER_PCA-A2)") (class "Default")
      (node (ref "OUTPUT_BUFFER_PC") (pin "3") (pinfunction "A2_3") (pintype "bidirectional"))
      (node (ref "PC_7") (pin "A") (pinfunction "A_A") (pintype "passive"))
      (node (ref "PROGRAM_COUNTER_UPPER") (pin "12") (pinfunction "12_12") (pintype "passive"))
    )
    (net (code "240") (name "Net-(OUTPUT_BUFFER_PCA-A3)") (class "Default")
      (node (ref "OUTPUT_BUFFER_PC") (pin "4") (pinfunction "A3_4") (pintype "bidirectional"))
      (node (ref "PC_6") (pin "A") (pinfunction "A_A") (pintype "passive"))
      (node (ref "PROGRAM_COUNTER_UPPER") (pin "13") (pinfunction "13_13") (pintype "passive"))
    )
    (net (code "241") (name "Net-(OUTPUT_BUFFER_PCA-A4)") (class "Default")
      (node (ref "OUTPUT_BUFFER_PC") (pin "5") (pinfunction "A4_5") (pintype "bidirectional"))
      (node (ref "PC_5") (pin "A") (pinfunction "A_A") (pintype "passive"))
      (node (ref "PROGRAM_COUNTER_UPPER") (pin "14") (pinfunction "14_14") (pintype "passive"))
    )
    (net (code "242") (name "Net-(OUTPUT_BUFFER_PCA-A5)") (class "Default")
      (node (ref "OUTPUT_BUFFER_PC") (pin "6") (pinfunction "A5_6") (pintype "bidirectional"))
      (node (ref "PC_4") (pin "A") (pinfunction "A_A") (pintype "passive"))
      (node (ref "PROGRAM_COUNTER_LOWER") (pin "11") (pinfunction "11_11") (pintype "passive"))
    )
    (net (code "243") (name "Net-(OUTPUT_BUFFER_PCA-A6)") (class "Default")
      (node (ref "OUTPUT_BUFFER_PC") (pin "7") (pinfunction "A6_7") (pintype "bidirectional"))
      (node (ref "PC_3") (pin "A") (pinfunction "A_A") (pintype "passive"))
      (node (ref "PROGRAM_COUNTER_LOWER") (pin "12") (pinfunction "12_12") (pintype "passive"))
    )
    (net (code "244") (name "Net-(OUTPUT_BUFFER_PCA-A7)") (class "Default")
      (node (ref "OUTPUT_BUFFER_PC") (pin "8") (pinfunction "A7_8") (pintype "bidirectional"))
      (node (ref "PC_2") (pin "A") (pinfunction "A_A") (pintype "passive"))
      (node (ref "PROGRAM_COUNTER_LOWER") (pin "13") (pinfunction "13_13") (pintype "passive"))
    )
    (net (code "245") (name "Net-(OUTPUT_BUFFER_PCA-A8)") (class "Default")
      (node (ref "OUTPUT_BUFFER_PC") (pin "9") (pinfunction "A8_9") (pintype "bidirectional"))
      (node (ref "PC_1") (pin "A") (pinfunction "A_A") (pintype "passive"))
      (node (ref "PROGRAM_COUNTER_LOWER") (pin "14") (pinfunction "14_14") (pintype "passive"))
    )
    (net (code "246") (name "Net-(OUTPUT_BUFFER_PCA-G)") (class "Default")
      (node (ref "OUTPUT_BUFFER_PC") (pin "19") (pinfunction "G_19") (pintype "input"))
      (node (ref "SELECTOR_STACK_") (pin "6") (pinfunction "Y2_6") (pintype "output"))
    )
    (net (code "247") (name "Net-(OUTPUT_BUFFER_RAMA-A1)") (class "Default")
      (node (ref "OUTPUT_BUFFER_RAM") (pin "2") (pinfunction "A1_2") (pintype "bidirectional"))
      (node (ref "RAM") (pin "11") (pinfunction "11_11") (pintype "passive"))
      (node (ref "RAM_LED_1") (pin "A") (pinfunction "A_A") (pintype "passive"))
    )
    (net (code "248") (name "Net-(OUTPUT_BUFFER_RAMA-A2)") (class "Default")
      (node (ref "OUTPUT_BUFFER_RAM") (pin "3") (pinfunction "A2_3") (pintype "bidirectional"))
      (node (ref "RAM") (pin "12") (pinfunction "12_12") (pintype "passive"))
      (node (ref "RAM_LED_2") (pin "A") (pinfunction "A_A") (pintype "passive"))
    )
    (net (code "249") (name "Net-(OUTPUT_BUFFER_RAMA-A3)") (class "Default")
      (node (ref "OUTPUT_BUFFER_RAM") (pin "4") (pinfunction "A3_4") (pintype "bidirectional"))
      (node (ref "RAM") (pin "13") (pinfunction "13_13") (pintype "passive"))
      (node (ref "RAM_LED_3") (pin "A") (pinfunction "A_A") (pintype "passive"))
    )
    (net (code "250") (name "Net-(OUTPUT_BUFFER_RAMA-A4)") (class "Default")
      (node (ref "OUTPUT_BUFFER_RAM") (pin "5") (pinfunction "A4_5") (pintype "bidirectional"))
      (node (ref "RAM") (pin "15") (pinfunction "15_15") (pintype "passive"))
      (node (ref "RAM_LED_4") (pin "A") (pinfunction "A_A") (pintype "passive"))
    )
    (net (code "251") (name "Net-(OUTPUT_BUFFER_RAMA-A5)") (class "Default")
      (node (ref "OUTPUT_BUFFER_RAM") (pin "6") (pinfunction "A5_6") (pintype "bidirectional"))
      (node (ref "RAM") (pin "16") (pinfunction "16_16") (pintype "passive"))
      (node (ref "RAM_LED_5") (pin "A") (pinfunction "A_A") (pintype "passive"))
    )
    (net (code "252") (name "Net-(OUTPUT_BUFFER_RAMA-A6)") (class "Default")
      (node (ref "OUTPUT_BUFFER_RAM") (pin "7") (pinfunction "A6_7") (pintype "bidirectional"))
      (node (ref "RAM") (pin "17") (pinfunction "17_17") (pintype "passive"))
      (node (ref "RAM_LED_6") (pin "A") (pinfunction "A_A") (pintype "passive"))
    )
    (net (code "253") (name "Net-(OUTPUT_BUFFER_RAMA-A7)") (class "Default")
      (node (ref "OUTPUT_BUFFER_RAM") (pin "8") (pinfunction "A7_8") (pintype "bidirectional"))
      (node (ref "RAM") (pin "18") (pinfunction "18_18") (pintype "passive"))
      (node (ref "RAM_LED_7") (pin "A") (pinfunction "A_A") (pintype "passive"))
    )
    (net (code "254") (name "Net-(OUTPUT_BUFFER_RAMA-A8)") (class "Default")
      (node (ref "OUTPUT_BUFFER_RAM") (pin "9") (pinfunction "A8_9") (pintype "bidirectional"))
      (node (ref "RAM") (pin "19") (pinfunction "19_19") (pintype "passive"))
      (node (ref "RAM_LED_8") (pin "A") (pinfunction "A_A") (pintype "passive"))
    )
    (net (code "255") (name "Net-(OUTPUT_BUFFER_RAMA-DIR)") (class "Default")
      (node (ref "OUTPUT_BUFFER_RAM") (pin "1") (pinfunction "DIR_1") (pintype "input"))
      (node (ref "SELECTOR_STACK_") (pin "9") (pinfunction "Y3_9") (pintype "output"))
    )
    (net (code "256") (name "Net-(OUTPUT_BUFFER_REG_AA-G)") (class "Default")
      (node (ref "OUTPUT_BUFFER_REG_A") (pin "19") (pinfunction "G_19") (pintype "input"))
      (node (ref "SELECTOR_BRANCH_") (pin "11") (pinfunction "Y1_11") (pintype "output"))
    )
    (net (code "257") (name "Net-(OUT_REG_LOWERA-G1)") (class "Default")
      (node (ref "INSTRUCTION_MEMORY_2") (pin "15") (pinfunction "15_15") (pintype "passive"))
      (node (ref "OUT_REG_LOWER") (pin "10") (pinfunction "G2_10") (pintype "input"))
      (node (ref "OUT_REG_LOWER") (pin "9") (pinfunction "G1_9") (pintype "input"))
      (node (ref "OUT_REG_UPPER") (pin "10") (pinfunction "G2_10") (pintype "input"))
      (node (ref "OUT_REG_UPPER") (pin "9") (pinfunction "G1_9") (pintype "input"))
    )
    (net (code "258") (name "Net-(OUT_REG_LOWERA-Q1)") (class "Default")
      (node (ref "OUT_REG_LOWER") (pin "3") (pinfunction "Q1_3") (pintype "tri_state"))
      (node (ref "OUT_ROM_LOWER") (pin "7") (pinfunction "7_7") (pintype "passive"))
    )
    (net (code "259") (name "Net-(OUT_REG_LOWERA-Q2)") (class "Default")
      (node (ref "OUT_REG_LOWER") (pin "4") (pinfunction "Q2_4") (pintype "tri_state"))
      (node (ref "OUT_ROM_LOWER") (pin "8") (pinfunction "8_8") (pintype "passive"))
    )
    (net (code "260") (name "Net-(OUT_REG_LOWERA-Q3)") (class "Default")
      (node (ref "OUT_REG_LOWER") (pin "5") (pinfunction "Q3_5") (pintype "tri_state"))
      (node (ref "OUT_ROM_LOWER") (pin "9") (pinfunction "9_9") (pintype "passive"))
    )
    (net (code "261") (name "Net-(OUT_REG_LOWERA-Q4)") (class "Default")
      (node (ref "OUT_REG_LOWER") (pin "6") (pinfunction "Q4_6") (pintype "tri_state"))
      (node (ref "OUT_ROM_LOWER") (pin "10") (pinfunction "10_10") (pintype "passive"))
    )
    (net (code "262") (name "Net-(OUT_REG_UPPERA-Q1)") (class "Default")
      (node (ref "OUT_REG_UPPER") (pin "3") (pinfunction "Q1_3") (pintype "tri_state"))
      (node (ref "OUT_ROM_UPPER") (pin "7") (pinfunction "7_7") (pintype "passive"))
    )
    (net (code "263") (name "Net-(OUT_REG_UPPERA-Q2)") (class "Default")
      (node (ref "OUT_REG_UPPER") (pin "4") (pinfunction "Q2_4") (pintype "tri_state"))
      (node (ref "OUT_ROM_UPPER") (pin "8") (pinfunction "8_8") (pintype "passive"))
    )
    (net (code "264") (name "Net-(OUT_REG_UPPERA-Q3)") (class "Default")
      (node (ref "OUT_REG_UPPER") (pin "5") (pinfunction "Q3_5") (pintype "tri_state"))
      (node (ref "OUT_ROM_UPPER") (pin "9") (pinfunction "9_9") (pintype "passive"))
    )
    (net (code "265") (name "Net-(OUT_REG_UPPERA-Q4)") (class "Default")
      (node (ref "OUT_REG_UPPER") (pin "6") (pinfunction "Q4_6") (pintype "tri_state"))
      (node (ref "OUT_ROM_UPPER") (pin "10") (pinfunction "10_10") (pintype "passive"))
    )
    (net (code "266") (name "Net-(OUT_SEGMENT_LOWER-A)") (class "Default")
      (node (ref "OUT_ROM_LOWER") (pin "16") (pinfunction "16_16") (pintype "passive"))
      (node (ref "OUT_SEGMENT_LOWER") (pin "7") (pinfunction "A_7") (pintype "passive"))
    )
    (net (code "267") (name "Net-(OUT_SEGMENT_LOWER-B)") (class "Default")
      (node (ref "OUT_ROM_LOWER") (pin "15") (pinfunction "15_15") (pintype "passive"))
      (node (ref "OUT_SEGMENT_LOWER") (pin "6") (pinfunction "B_6") (pintype "passive"))
    )
    (net (code "268") (name "Net-(OUT_SEGMENT_LOWER-C)") (class "Default")
      (node (ref "OUT_ROM_LOWER") (pin "13") (pinfunction "13_13") (pintype "passive"))
      (node (ref "OUT_SEGMENT_LOWER") (pin "4") (pinfunction "C_4") (pintype "passive"))
    )
    (net (code "269") (name "Net-(OUT_SEGMENT_LOWER-D)") (class "Default")
      (node (ref "OUT_ROM_LOWER") (pin "12") (pinfunction "12_12") (pintype "passive"))
      (node (ref "OUT_SEGMENT_LOWER") (pin "2") (pinfunction "D_2") (pintype "passive"))
    )
    (net (code "270") (name "Net-(OUT_SEGMENT_LOWER-DP)") (class "Default")
      (node (ref "OUT_ROM_LOWER") (pin "19") (pinfunction "19_19") (pintype "passive"))
      (node (ref "OUT_SEGMENT_LOWER") (pin "5") (pinfunction "DP_5") (pintype "passive"))
    )
    (net (code "271") (name "Net-(OUT_SEGMENT_LOWER-E)") (class "Default")
      (node (ref "OUT_ROM_LOWER") (pin "11") (pinfunction "11_11") (pintype "passive"))
      (node (ref "OUT_SEGMENT_LOWER") (pin "1") (pinfunction "E_1") (pintype "passive"))
    )
    (net (code "272") (name "Net-(OUT_SEGMENT_LOWER-F)") (class "Default")
      (node (ref "OUT_ROM_LOWER") (pin "17") (pinfunction "17_17") (pintype "passive"))
      (node (ref "OUT_SEGMENT_LOWER") (pin "9") (pinfunction "F_9") (pintype "passive"))
    )
    (net (code "273") (name "Net-(OUT_SEGMENT_LOWER-G)") (class "Default")
      (node (ref "OUT_ROM_LOWER") (pin "18") (pinfunction "18_18") (pintype "passive"))
      (node (ref "OUT_SEGMENT_LOWER") (pin "10") (pinfunction "G_10") (pintype "passive"))
    )
    (net (code "274") (name "Net-(OUT_SEGMENT_UPPER-A)") (class "Default")
      (node (ref "OUT_ROM_UPPER") (pin "16") (pinfunction "16_16") (pintype "passive"))
      (node (ref "OUT_SEGMENT_UPPER") (pin "7") (pinfunction "A_7") (pintype "passive"))
    )
    (net (code "275") (name "Net-(OUT_SEGMENT_UPPER-B)") (class "Default")
      (node (ref "OUT_ROM_UPPER") (pin "15") (pinfunction "15_15") (pintype "passive"))
      (node (ref "OUT_SEGMENT_UPPER") (pin "6") (pinfunction "B_6") (pintype "passive"))
    )
    (net (code "276") (name "Net-(OUT_SEGMENT_UPPER-C)") (class "Default")
      (node (ref "OUT_ROM_UPPER") (pin "11") (pinfunction "11_11") (pintype "passive"))
      (node (ref "OUT_SEGMENT_UPPER") (pin "4") (pinfunction "C_4") (pintype "passive"))
    )
    (net (code "277") (name "Net-(OUT_SEGMENT_UPPER-D)") (class "Default")
      (node (ref "OUT_ROM_UPPER") (pin "12") (pinfunction "12_12") (pintype "passive"))
      (node (ref "OUT_SEGMENT_UPPER") (pin "2") (pinfunction "D_2") (pintype "passive"))
    )
    (net (code "278") (name "Net-(OUT_SEGMENT_UPPER-DP)") (class "Default")
      (node (ref "OUT_ROM_UPPER") (pin "17") (pinfunction "17_17") (pintype "passive"))
      (node (ref "OUT_SEGMENT_UPPER") (pin "5") (pinfunction "DP_5") (pintype "passive"))
    )
    (net (code "279") (name "Net-(OUT_SEGMENT_UPPER-E)") (class "Default")
      (node (ref "OUT_ROM_UPPER") (pin "13") (pinfunction "13_13") (pintype "passive"))
      (node (ref "OUT_SEGMENT_UPPER") (pin "1") (pinfunction "E_1") (pintype "passive"))
    )
    (net (code "280") (name "Net-(OUT_SEGMENT_UPPER-F)") (class "Default")
      (node (ref "OUT_ROM_UPPER") (pin "19") (pinfunction "19_19") (pintype "passive"))
      (node (ref "OUT_SEGMENT_UPPER") (pin "9") (pinfunction "F_9") (pintype "passive"))
    )
    (net (code "281") (name "Net-(OUT_SEGMENT_UPPER-G)") (class "Default")
      (node (ref "OUT_ROM_UPPER") (pin "18") (pinfunction "18_18") (pintype "passive"))
      (node (ref "OUT_SEGMENT_UPPER") (pin "10") (pinfunction "G_10") (pintype "passive"))
    )
    (net (code "282") (name "Net-(OVERFLOW_FLAG-C)") (class "Default")
      (node (ref "OVERFLOW_FLAG") (pin "K") (pinfunction "C_K") (pintype "passive"))
      (node (ref "R13") (pin "2") (pinfunction "2_2") (pintype "passive"))
    )
    (net (code "283") (name "Net-(PARAM_LED_1-C)") (class "Default")
      (node (ref "PARAM_LED_1") (pin "K") (pinfunction "C_K") (pintype "passive"))
      (node (ref "R71") (pin "1") (pinfunction "1_1") (pintype "passive"))
    )
    (net (code "284") (name "Net-(PARAM_LED_2-C)") (class "Default")
      (node (ref "PARAM_LED_2") (pin "K") (pinfunction "C_K") (pintype "passive"))
      (node (ref "R70") (pin "1") (pinfunction "1_1") (pintype "passive"))
    )
    (net (code "285") (name "Net-(PARAM_LED_3-C)") (class "Default")
      (node (ref "PARAM_LED_3") (pin "K") (pinfunction "C_K") (pintype "passive"))
      (node (ref "R69") (pin "1") (pinfunction "1_1") (pintype "passive"))
    )
    (net (code "286") (name "Net-(PARAM_LED_4-C)") (class "Default")
      (node (ref "PARAM_LED_4") (pin "K") (pinfunction "C_K") (pintype "passive"))
      (node (ref "R76") (pin "1") (pinfunction "1_1") (pintype "passive"))
    )
    (net (code "287") (name "Net-(PARAM_LED_5-C)") (class "Default")
      (node (ref "PARAM_LED_5") (pin "K") (pinfunction "C_K") (pintype "passive"))
      (node (ref "R72") (pin "1") (pinfunction "1_1") (pintype "passive"))
    )
    (net (code "288") (name "Net-(PARAM_LED_6-C)") (class "Default")
      (node (ref "PARAM_LED_6") (pin "K") (pinfunction "C_K") (pintype "passive"))
      (node (ref "R73") (pin "1") (pinfunction "1_1") (pintype "passive"))
    )
    (net (code "289") (name "Net-(PARAM_LED_7-C)") (class "Default")
      (node (ref "PARAM_LED_7") (pin "K") (pinfunction "C_K") (pintype "passive"))
      (node (ref "R74") (pin "1") (pinfunction "1_1") (pintype "passive"))
    )
    (net (code "290") (name "Net-(PARAM_LED_8-C)") (class "Default")
      (node (ref "PARAM_LED_8") (pin "K") (pinfunction "C_K") (pintype "passive"))
      (node (ref "R75") (pin "1") (pinfunction "1_1") (pintype "passive"))
    )
    (net (code "291") (name "Net-(PC_1-C)") (class "Default")
      (node (ref "PC_1") (pin "K") (pinfunction "C_K") (pintype "passive"))
      (node (ref "R16") (pin "1") (pinfunction "1_1") (pintype "passive"))
    )
    (net (code "292") (name "Net-(PC_2-C)") (class "Default")
      (node (ref "PC_2") (pin "K") (pinfunction "C_K") (pintype "passive"))
      (node (ref "R17") (pin "1") (pinfunction "1_1") (pintype "passive"))
    )
    (net (code "293") (name "Net-(PC_3-C)") (class "Default")
      (node (ref "PC_3") (pin "K") (pinfunction "C_K") (pintype "passive"))
      (node (ref "R18") (pin "1") (pinfunction "1_1") (pintype "passive"))
    )
    (net (code "294") (name "Net-(PC_4-C)") (class "Default")
      (node (ref "PC_4") (pin "K") (pinfunction "C_K") (pintype "passive"))
      (node (ref "R19") (pin "1") (pinfunction "1_1") (pintype "passive"))
    )
    (net (code "295") (name "Net-(PC_5-C)") (class "Default")
      (node (ref "PC_5") (pin "K") (pinfunction "C_K") (pintype "passive"))
      (node (ref "R20") (pin "1") (pinfunction "1_1") (pintype "passive"))
    )
    (net (code "296") (name "Net-(PC_6-C)") (class "Default")
      (node (ref "PC_6") (pin "K") (pinfunction "C_K") (pintype "passive"))
      (node (ref "R21") (pin "1") (pinfunction "1_1") (pintype "passive"))
    )
    (net (code "297") (name "Net-(PC_7-C)") (class "Default")
      (node (ref "PC_7") (pin "K") (pinfunction "C_K") (pintype "passive"))
      (node (ref "R22") (pin "1") (pinfunction "1_1") (pintype "passive"))
    )
    (net (code "298") (name "Net-(PC_8-C)") (class "Default")
      (node (ref "PC_8") (pin "K") (pinfunction "C_K") (pintype "passive"))
      (node (ref "R23") (pin "1") (pinfunction "1_1") (pintype "passive"))
    )
    (net (code "299") (name "Net-(POSITIVE_FLAG-C)") (class "Default")
      (node (ref "POSITIVE_FLAG") (pin "K") (pinfunction "C_K") (pintype "passive"))
      (node (ref "R12") (pin "2") (pinfunction "2_2") (pintype "passive"))
    )
    (net (code "300") (name "Net-(PROGRAM_COUNTER_LOWER-Pad15)") (class "Default")
      (node (ref "PROGRAM_COUNTER_LOWER") (pin "15") (pinfunction "15_15") (pintype "passive"))
      (node (ref "PROGRAM_COUNTER_UPPER") (pin "10") (pinfunction "10_10") (pintype "passive"))
    )
    (net (code "301") (name "Net-(RAM_ADDR_LOWERA-Q1)") (class "Default")
      (node (ref "RAM") (pin "10") (pinfunction "10_10") (pintype "passive"))
      (node (ref "RAM_ADDR_LOWER") (pin "3") (pinfunction "Q1_3") (pintype "tri_state"))
    )
    (net (code "302") (name "Net-(RAM_ADDR_LOWERA-Q2)") (class "Default")
      (node (ref "RAM") (pin "9") (pinfunction "9_9") (pintype "passive"))
      (node (ref "RAM_ADDR_LOWER") (pin "4") (pinfunction "Q2_4") (pintype "tri_state"))
    )
    (net (code "303") (name "Net-(RAM_ADDR_LOWERA-Q3)") (class "Default")
      (node (ref "RAM") (pin "8") (pinfunction "8_8") (pintype "passive"))
      (node (ref "RAM_ADDR_LOWER") (pin "5") (pinfunction "Q3_5") (pintype "tri_state"))
    )
    (net (code "304") (name "Net-(RAM_ADDR_LOWERA-Q4)") (class "Default")
      (node (ref "RAM") (pin "7") (pinfunction "7_7") (pintype "passive"))
      (node (ref "RAM_ADDR_LOWER") (pin "6") (pinfunction "Q4_6") (pintype "tri_state"))
    )
    (net (code "305") (name "Net-(RAM_ADDR_UPPERA-Q1)") (class "Default")
      (node (ref "RAM") (pin "6") (pinfunction "6_6") (pintype "passive"))
      (node (ref "RAM_ADDR_UPPER") (pin "3") (pinfunction "Q1_3") (pintype "tri_state"))
    )
    (net (code "306") (name "Net-(RAM_ADDR_UPPERA-Q2)") (class "Default")
      (node (ref "RAM") (pin "5") (pinfunction "5_5") (pintype "passive"))
      (node (ref "RAM_ADDR_UPPER") (pin "4") (pinfunction "Q2_4") (pintype "tri_state"))
    )
    (net (code "307") (name "Net-(RAM_ADDR_UPPERA-Q3)") (class "Default")
      (node (ref "RAM") (pin "4") (pinfunction "4_4") (pintype "passive"))
      (node (ref "RAM_ADDR_UPPER") (pin "5") (pinfunction "Q3_5") (pintype "tri_state"))
    )
    (net (code "308") (name "Net-(RAM_ADDR_UPPERA-Q4)") (class "Default")
      (node (ref "RAM") (pin "3") (pinfunction "3_3") (pintype "passive"))
      (node (ref "RAM_ADDR_UPPER") (pin "6") (pinfunction "Q4_6") (pintype "tri_state"))
    )
    (net (code "309") (name "Net-(RAM_LED_1-C)") (class "Default")
      (node (ref "R32") (pin "1") (pinfunction "1_1") (pintype "passive"))
      (node (ref "RAM_LED_1") (pin "K") (pinfunction "C_K") (pintype "passive"))
    )
    (net (code "310") (name "Net-(RAM_LED_2-C)") (class "Default")
      (node (ref "R33") (pin "1") (pinfunction "1_1") (pintype "passive"))
      (node (ref "RAM_LED_2") (pin "K") (pinfunction "C_K") (pintype "passive"))
    )
    (net (code "311") (name "Net-(RAM_LED_3-C)") (class "Default")
      (node (ref "R34") (pin "1") (pinfunction "1_1") (pintype "passive"))
      (node (ref "RAM_LED_3") (pin "K") (pinfunction "C_K") (pintype "passive"))
    )
    (net (code "312") (name "Net-(RAM_LED_4-C)") (class "Default")
      (node (ref "R35") (pin "1") (pinfunction "1_1") (pintype "passive"))
      (node (ref "RAM_LED_4") (pin "K") (pinfunction "C_K") (pintype "passive"))
    )
    (net (code "313") (name "Net-(RAM_LED_5-C)") (class "Default")
      (node (ref "R36") (pin "1") (pinfunction "1_1") (pintype "passive"))
      (node (ref "RAM_LED_5") (pin "K") (pinfunction "C_K") (pintype "passive"))
    )
    (net (code "314") (name "Net-(RAM_LED_6-C)") (class "Default")
      (node (ref "R37") (pin "1") (pinfunction "1_1") (pintype "passive"))
      (node (ref "RAM_LED_6") (pin "K") (pinfunction "C_K") (pintype "passive"))
    )
    (net (code "315") (name "Net-(RAM_LED_7-C)") (class "Default")
      (node (ref "R38") (pin "1") (pinfunction "1_1") (pintype "passive"))
      (node (ref "RAM_LED_7") (pin "K") (pinfunction "C_K") (pintype "passive"))
    )
    (net (code "316") (name "Net-(RAM_LED_8-C)") (class "Default")
      (node (ref "R39") (pin "1") (pinfunction "1_1") (pintype "passive"))
      (node (ref "RAM_LED_8") (pin "K") (pinfunction "C_K") (pintype "passive"))
    )
    (net (code "317") (name "Net-(REG_A_LOWERA-G1)") (class "Default")
      (node (ref "REG_A_LOWER") (pin "10") (pinfunction "G2_10") (pintype "input"))
      (node (ref "REG_A_LOWER") (pin "9") (pinfunction "G1_9") (pintype "input"))
      (node (ref "REG_A_UPPER") (pin "10") (pinfunction "G2_10") (pintype "input"))
      (node (ref "REG_A_UPPER") (pin "9") (pinfunction "G1_9") (pintype "input"))
      (node (ref "SELECTOR_BRANCH_") (pin "10") (pinfunction "Y2_10") (pintype "output"))
    )
    (net (code "318") (name "Net-(REG_CALC_LOWERA-G1)") (class "Default")
      (node (ref "REG_CALC_LOWER") (pin "10") (pinfunction "G2_10") (pintype "input"))
      (node (ref "REG_CALC_LOWER") (pin "9") (pinfunction "G1_9") (pintype "input"))
      (node (ref "REG_CALC_UPPER") (pin "10") (pinfunction "G2_10") (pintype "input"))
      (node (ref "REG_CALC_UPPER") (pin "9") (pinfunction "G1_9") (pintype "input"))
      (node (ref "SELECTOR_LOGIC_") (pin "10") (pinfunction "Y2_10") (pintype "output"))
    )
    (net (code "319") (name "Net-(SELECTOR_BRANCH_A-A)") (class "Default")
      (node (ref "INSTRUCTION_MEMORY_2") (pin "19") (pinfunction "19_19") (pintype "passive"))
      (node (ref "SELECTOR_BRANCH_") (pin "2") (pinfunction "A_2") (pintype "input"))
    )
    (net (code "320") (name "Net-(SELECTOR_BRANCH_A-B)") (class "Default")
      (node (ref "INSTRUCTION_MEMORY_2") (pin "18") (pinfunction "18_18") (pintype "passive"))
      (node (ref "SELECTOR_BRANCH_") (pin "3") (pinfunction "B_3") (pintype "input"))
    )
    (net (code "321") (name "Net-(SELECTOR_BRANCH_B-A)") (class "Default")
      (node (ref "SELECTOR_BRANCH_") (pin "14") (pinfunction "A_14") (pintype "input"))
      (node (ref "SELECTOR_INSRUCTION_LOWER") (pin "4") (pinfunction "1Y_4") (pintype "output"))
    )
    (net (code "322") (name "Net-(SELECTOR_BRANCH_B-B)") (class "Default")
      (node (ref "SELECTOR_BRANCH_") (pin "13") (pinfunction "B_13") (pintype "input"))
      (node (ref "SELECTOR_INSRUCTION_LOWER") (pin "7") (pinfunction "2Y_7") (pintype "output"))
    )
    (net (code "323") (name "Net-(SELECTOR_INSRUCTION_LOWERA-3Y)") (class "Default")
      (node (ref "SELECTOR_INSRUCTION_LOWER") (pin "9") (pinfunction "3Y_9") (pintype "output"))
      (node (ref "SELECTOR_PARAM_") (pin "14") (pinfunction "A_14") (pintype "input"))
    )
    (net (code "324") (name "Net-(SELECTOR_INSRUCTION_LOWERA-4Y)") (class "Default")
      (node (ref "SELECTOR_INSRUCTION_LOWER") (pin "12") (pinfunction "4Y_12") (pintype "output"))
      (node (ref "SELECTOR_PARAM_") (pin "13") (pinfunction "B_13") (pintype "input"))
    )
    (net (code "325") (name "Net-(SELECTOR_INSRUCTION_UPPERA-3Y)") (class "Default")
      (node (ref "SELECTOR_INSRUCTION_UPPER") (pin "9") (pinfunction "3Y_9") (pintype "output"))
      (node (ref "SELECTOR_STACK_") (pin "2") (pinfunction "A_2") (pintype "input"))
    )
    (net (code "326") (name "Net-(SELECTOR_INSRUCTION_UPPERA-4Y)") (class "Default")
      (node (ref "SELECTOR_INSRUCTION_UPPER") (pin "12") (pinfunction "4Y_12") (pintype "output"))
      (node (ref "SELECTOR_STACK_") (pin "3") (pinfunction "B_3") (pintype "input"))
    )
    (net (code "327") (name "Net-(SELECTOR_LOGIC_A-A)") (class "Default")
      (node (ref "INSTRUCTION_MEMORY_1") (pin "18") (pinfunction "18_18") (pintype "passive"))
      (node (ref "SELECTOR_LOGIC_") (pin "2") (pinfunction "A_2") (pintype "input"))
    )
    (net (code "328") (name "Net-(SELECTOR_LOGIC_A-B)") (class "Default")
      (node (ref "INSTRUCTION_MEMORY_1") (pin "19") (pinfunction "19_19") (pintype "passive"))
      (node (ref "SELECTOR_LOGIC_") (pin "3") (pinfunction "B_3") (pintype "input"))
    )
    (net (code "329") (name "Net-(SELECTOR_LOGIC_B-A)") (class "Default")
      (node (ref "INSTRUCTION_MEMORY_1") (pin "12") (pinfunction "12_12") (pintype "passive"))
      (node (ref "SELECTOR_LOGIC_") (pin "14") (pinfunction "A_14") (pintype "input"))
    )
    (net (code "330") (name "Net-(SELECTOR_LOGIC_B-B)") (class "Default")
      (node (ref "INSTRUCTION_MEMORY_1") (pin "11") (pinfunction "11_11") (pintype "passive"))
      (node (ref "SELECTOR_LOGIC_") (pin "13") (pinfunction "B_13") (pintype "input"))
    )
    (net (code "331") (name "Net-(SELECTOR_PARAM_A-A)") (class "Default")
      (node (ref "INSTRUCTION_MEMORY_2") (pin "17") (pinfunction "17_17") (pintype "passive"))
      (node (ref "SELECTOR_PARAM_") (pin "2") (pinfunction "A_2") (pintype "input"))
    )
    (net (code "332") (name "Net-(SELECTOR_PARAM_A-B)") (class "Default")
      (node (ref "INSTRUCTION_MEMORY_2") (pin "16") (pinfunction "16_16") (pintype "passive"))
      (node (ref "SELECTOR_PARAM_") (pin "3") (pinfunction "B_3") (pintype "input"))
    )
    (net (code "333") (name "Net-(SELECTOR_STACK_B-A)") (class "Default")
      (node (ref "INSTRUCTION_MEMORY_2") (pin "13") (pinfunction "13_13") (pintype "passive"))
      (node (ref "SELECTOR_STACK_") (pin "14") (pinfunction "A_14") (pintype "input"))
    )
    (net (code "334") (name "Net-(SELECTOR_STACK_B-B)") (class "Default")
      (node (ref "INSTRUCTION_MEMORY_2") (pin "12") (pinfunction "12_12") (pintype "passive"))
      (node (ref "SELECTOR_STACK_") (pin "13") (pinfunction "B_13") (pintype "input"))
    )
    (net (code "335") (name "Net-(STEPPER_CLOCK-DIS)") (class "Default")
      (node (ref "C2") (pin "+") (pinfunction "+_+") (pintype "passive"))
      (node (ref "R3") (pin "1") (pinfunction "1_1") (pintype "passive"))
      (node (ref "STEPPER_CLOCK") (pin "6") (pinfunction "THR_6") (pintype "input"))
      (node (ref "STEPPER_CLOCK") (pin "7") (pinfunction "DIS_7") (pintype "input"))
    )
    (net (code "336") (name "Net-(USTEP_1-C)") (class "Default")
      (node (ref "R40") (pin "2") (pinfunction "2_2") (pintype "passive"))
      (node (ref "USTEP_1") (pin "K") (pinfunction "C_K") (pintype "passive"))
    )
    (net (code "337") (name "Net-(USTEP_2-C)") (class "Default")
      (node (ref "R41") (pin "2") (pinfunction "2_2") (pintype "passive"))
      (node (ref "USTEP_2") (pin "K") (pinfunction "C_K") (pintype "passive"))
    )
    (net (code "338") (name "Net-(USTEP_3-C)") (class "Default")
      (node (ref "R42") (pin "2") (pinfunction "2_2") (pintype "passive"))
      (node (ref "USTEP_3") (pin "K") (pinfunction "C_K") (pintype "passive"))
    )
    (net (code "339") (name "Net-(USTEP_4-C)") (class "Default")
      (node (ref "R43") (pin "2") (pinfunction "2_2") (pintype "passive"))
      (node (ref "USTEP_4") (pin "K") (pinfunction "C_K") (pintype "passive"))
    )
    (net (code "340") (name "Net-(USTEP_5-C)") (class "Default")
      (node (ref "R44") (pin "2") (pinfunction "2_2") (pintype "passive"))
      (node (ref "USTEP_5") (pin "K") (pinfunction "C_K") (pintype "passive"))
    )
    (net (code "341") (name "Net-(ZERO_FLAG-C)") (class "Default")
      (node (ref "R14") (pin "2") (pinfunction "2_2") (pintype "passive"))
      (node (ref "ZERO_FLAG") (pin "K") (pinfunction "C_K") (pintype "passive"))
    )
    (net (code "342") (name "VCC") (class "Default")
      (node (ref "4_INP_OR_GATE") (pin "14") (pinfunction "VDD_14") (pintype "power_in"))
      (node (ref "AUTO_CLOCK") (pin "4") (pinfunction "R_4") (pintype "input"))
      (node (ref "AUTO_CLOCK") (pin "8") (pinfunction "V+_8") (pintype "power_in"))
      (node (ref "C3") (pin "+") (pinfunction "+_+") (pintype "passive"))
      (node (ref "CLK_MODE") (pin "2") (pinfunction "2_2") (pintype "passive"))
      (node (ref "EXTENSION") (pin "10") (pinfunction "1_10") (pintype "passive"))
      (node (ref "INSTRUCTIONS_EXTENSION") (pin "14") (pinfunction "1_14") (pintype "passive"))
      (node (ref "INSTRUCTION_MEMORY_0") (pin "27") (pinfunction "27_27") (pintype "passive"))
      (node (ref "INSTRUCTION_MEMORY_0") (pin "28") (pinfunction "28_28") (pintype "passive"))
      (node (ref "INSTRUCTION_MEMORY_1") (pin "27") (pinfunction "27_27") (pintype "passive"))
      (node (ref "INSTRUCTION_MEMORY_1") (pin "28") (pinfunction "28_28") (pintype "passive"))
      (node (ref "INSTRUCTION_MEMORY_2") (pin "27") (pinfunction "27_27") (pintype "passive"))
      (node (ref "INSTRUCTION_MEMORY_2") (pin "28") (pinfunction "28_28") (pintype "passive"))
      (node (ref "KEYBOARD") (pin "1") (pinfunction "1_1") (pintype "passive"))
      (node (ref "KEYBOARD_ASCII_TABLE") (pin "27") (pinfunction "27_27") (pintype "passive"))
      (node (ref "KEYBOARD_ASCII_TABLE") (pin "28") (pinfunction "28_28") (pintype "passive"))
      (node (ref "KEYBOARD_SHIFT_LOWER") (pin "10") (pinfunction "SCL_10") (pintype "input"))
      (node (ref "KEYBOARD_SHIFT_UPPER") (pin "10") (pinfunction "SCL_10") (pintype "input"))
      (node (ref "MEMORY") (pin "27") (pinfunction "27_27") (pintype "passive"))
      (node (ref "MEMORY") (pin "28") (pinfunction "28_28") (pintype "passive"))
      (node (ref "MICRO_COUNTER_LOWER") (pin "10") (pinfunction "10_10") (pintype "passive"))
      (node (ref "MICRO_COUNTER_LOWER") (pin "16") (pinfunction "16_16") (pintype "passive"))
      (node (ref "MICRO_COUNTER_LOWER") (pin "7") (pinfunction "7_7") (pintype "passive"))
      (node (ref "MICRO_COUNTER_UPPER") (pin "16") (pinfunction "16_16") (pintype "passive"))
      (node (ref "MICRO_COUNTER_UPPER") (pin "7") (pinfunction "7_7") (pintype "passive"))
      (node (ref "OUTPUT_BUFFER_CALC_REG") (pin "1") (pinfunction "DIR_1") (pintype "input"))
      (node (ref "OUTPUT_BUFFER_INSTRUCTION") (pin "1") (pinfunction "DIR_1") (pintype "input"))
      (node (ref "OUTPUT_BUFFER_MEMORY") (pin "1") (pinfunction "DIR_1") (pintype "input"))
      (node (ref "OUTPUT_BUFFER_PARAM_REG") (pin "1") (pinfunction "DIR_1") (pintype "input"))
      (node (ref "OUTPUT_BUFFER_PC") (pin "1") (pinfunction "DIR_1") (pintype "input"))
      (node (ref "OUTPUT_BUFFER_REG_A") (pin "1") (pinfunction "DIR_1") (pintype "input"))
      (node (ref "OUT_ROM_LOWER") (pin "27") (pinfunction "27_27") (pintype "passive"))
      (node (ref "OUT_ROM_LOWER") (pin "28") (pinfunction "28_28") (pintype "passive"))
      (node (ref "OUT_ROM_UPPER") (pin "27") (pinfunction "27_27") (pintype "passive"))
      (node (ref "OUT_ROM_UPPER") (pin "28") (pinfunction "28_28") (pintype "passive"))
      (node (ref "PROGRAM_COUNTER_LOWER") (pin "16") (pinfunction "16_16") (pintype "passive"))
      (node (ref "PROGRAM_COUNTER_LOWER") (pin "7") (pinfunction "7_7") (pintype "passive"))
      (node (ref "PROGRAM_COUNTER_UPPER") (pin "16") (pinfunction "16_16") (pintype "passive"))
      (node (ref "PROGRAM_COUNTER_UPPER") (pin "7") (pinfunction "7_7") (pintype "passive"))
      (node (ref "R1") (pin "1") (pinfunction "1_1") (pintype "passive"))
      (node (ref "R2") (pin "1") (pinfunction "1_1") (pintype "passive"))
      (node (ref "R3") (pin "2") (pinfunction "2_2") (pintype "passive"))
      (node (ref "R80") (pin "2") (pinfunction "2_2") (pintype "passive"))
      (node (ref "RAM") (pin "28") (pinfunction "28_28") (pintype "passive"))
      (node (ref "RESET_REGS") (pin "1") (pinfunction "S_1") (pintype "passive"))
      (node (ref "STEPPER_CLOCK") (pin "8") (pinfunction "V+_8") (pintype "power_in"))
      (node (ref "X1") (pin "2") (pinfunction "1_2") (pintype "passive"))
      (node (ref "ZERO_POS_FLAG_IDENTIFIER") (pin "14") (pinfunction "+UB_14") (pintype "power_in"))
    )
    (net (code "343") (name "unconnected-(AUTO_CLOCK-CV-Pad5)") (class "Default")
      (node (ref "AUTO_CLOCK") (pin "5") (pinfunction "CV_5") (pintype "input"))
    )
    (net (code "344") (name "unconnected-(CLK_TRIGGER-P1-Pad4)") (class "Default")
      (node (ref "CLK_TRIGGER") (pin "4") (pinfunction "P1_4") (pintype "passive"))
    )
    (net (code "345") (name "unconnected-(CLK_TRIGGER-S-Pad1)") (class "Default")
      (node (ref "CLK_TRIGGER") (pin "1") (pinfunction "S_1") (pintype "passive"))
    )
    (net (code "346") (name "unconnected-(FREQUENCY-PadA)") (class "Default")
      (node (ref "FREQUENCY") (pin "A") (pinfunction "A_A") (pintype "passive"))
    )
    (net (code "347") (name "unconnected-(IC1A-CLK-Pad2)") (class "Default")
      (node (ref "IC1") (pin "2") (pinfunction "CLK_2") (pintype "input"))
    )
    (net (code "348") (name "unconnected-(IC1A-CO-Pad15)") (class "Default")
      (node (ref "IC1") (pin "15") (pinfunction "CO_15") (pintype "output"))
    )
    (net (code "349") (name "unconnected-(IC1A-P1-Pad3)") (class "Default")
      (node (ref "IC1") (pin "3") (pinfunction "P1_3") (pintype "input"))
    )
    (net (code "350") (name "unconnected-(IC1A-P2-Pad4)") (class "Default")
      (node (ref "IC1") (pin "4") (pinfunction "P2_4") (pintype "input"))
    )
    (net (code "351") (name "unconnected-(IC1A-P3-Pad5)") (class "Default")
      (node (ref "IC1") (pin "5") (pinfunction "P3_5") (pintype "input"))
    )
    (net (code "352") (name "unconnected-(IC1A-P4-Pad6)") (class "Default")
      (node (ref "IC1") (pin "6") (pinfunction "P4_6") (pintype "input"))
    )
    (net (code "353") (name "unconnected-(IC1A-PE-Pad7)") (class "Default")
      (node (ref "IC1") (pin "7") (pinfunction "PE_7") (pintype "input"))
    )
    (net (code "354") (name "unconnected-(IC1A-Q1-Pad14)") (class "Default")
      (node (ref "IC1") (pin "14") (pinfunction "Q1_14") (pintype "output"))
    )
    (net (code "355") (name "unconnected-(IC1A-Q2-Pad13)") (class "Default")
      (node (ref "IC1") (pin "13") (pinfunction "Q2_13") (pintype "output"))
    )
    (net (code "356") (name "unconnected-(IC1A-Q3-Pad12)") (class "Default")
      (node (ref "IC1") (pin "12") (pinfunction "Q3_12") (pintype "output"))
    )
    (net (code "357") (name "unconnected-(IC1A-Q4-Pad11)") (class "Default")
      (node (ref "IC1") (pin "11") (pinfunction "Q4_11") (pintype "output"))
    )
    (net (code "358") (name "unconnected-(IC1A-TE-Pad10)") (class "Default")
      (node (ref "IC1") (pin "10") (pinfunction "TE_10") (pintype "input"))
    )
    (net (code "359") (name "unconnected-(IC1A-~{CLEAR}-Pad1)") (class "Default")
      (node (ref "IC1") (pin "1") (pinfunction "~{CLEAR}_1") (pintype "input"))
    )
    (net (code "360") (name "unconnected-(IC1A-~{LOAD}-Pad9)") (class "Default")
      (node (ref "IC1") (pin "9") (pinfunction "~{LOAD}_9") (pintype "input"))
    )
    (net (code "361") (name "unconnected-(INSTRUCTION_MEMORY_0-Pad1)") (class "Default")
      (node (ref "INSTRUCTION_MEMORY_0") (pin "1") (pinfunction "1_1") (pintype "passive"))
    )
    (net (code "362") (name "unconnected-(INSTRUCTION_MEMORY_0-Pad26)") (class "Default")
      (node (ref "INSTRUCTION_MEMORY_0") (pin "26") (pinfunction "26_26") (pintype "passive"))
    )
    (net (code "363") (name "unconnected-(INSTRUCTION_MEMORY_1-Pad1)") (class "Default")
      (node (ref "INSTRUCTION_MEMORY_1") (pin "1") (pinfunction "1_1") (pintype "passive"))
    )
    (net (code "364") (name "unconnected-(INSTRUCTION_MEMORY_1-Pad26)") (class "Default")
      (node (ref "INSTRUCTION_MEMORY_1") (pin "26") (pinfunction "26_26") (pintype "passive"))
    )
    (net (code "365") (name "unconnected-(INSTRUCTION_MEMORY_2-Pad1)") (class "Default")
      (node (ref "INSTRUCTION_MEMORY_2") (pin "1") (pinfunction "1_1") (pintype "passive"))
    )
    (net (code "366") (name "unconnected-(INSTRUCTION_MEMORY_2-Pad26)") (class "Default")
      (node (ref "INSTRUCTION_MEMORY_2") (pin "26") (pinfunction "26_26") (pintype "passive"))
    )
    (net (code "367") (name "unconnected-(KEYBOARD_ASCII_TABLE-Pad1)") (class "Default")
      (node (ref "KEYBOARD_ASCII_TABLE") (pin "1") (pinfunction "1_1") (pintype "passive"))
    )
    (net (code "368") (name "unconnected-(KEYBOARD_ASCII_TABLE-Pad26)") (class "Default")
      (node (ref "KEYBOARD_ASCII_TABLE") (pin "26") (pinfunction "26_26") (pintype "passive"))
    )
    (net (code "369") (name "unconnected-(KEYBOARD_SHIFT_LOWERA-QC-Pad2)") (class "Default")
      (node (ref "KEYBOARD_SHIFT_LOWER") (pin "2") (pinfunction "QC_2") (pintype "tri_state"))
    )
    (net (code "370") (name "unconnected-(KEYBOARD_SHIFT_LOWERA-QD-Pad3)") (class "Default")
      (node (ref "KEYBOARD_SHIFT_LOWER") (pin "3") (pinfunction "QD_3") (pintype "tri_state"))
    )
    (net (code "371") (name "unconnected-(KEYBOARD_SHIFT_LOWERA-QE-Pad4)") (class "Default")
      (node (ref "KEYBOARD_SHIFT_LOWER") (pin "4") (pinfunction "QE_4") (pintype "tri_state"))
    )
    (net (code "372") (name "unconnected-(KEYBOARD_SHIFT_LOWERA-QF-Pad5)") (class "Default")
      (node (ref "KEYBOARD_SHIFT_LOWER") (pin "5") (pinfunction "QF_5") (pintype "tri_state"))
    )
    (net (code "373") (name "unconnected-(KEYBOARD_SHIFT_LOWERA-QG-Pad6)") (class "Default")
      (node (ref "KEYBOARD_SHIFT_LOWER") (pin "6") (pinfunction "QG_6") (pintype "tri_state"))
    )
    (net (code "374") (name "unconnected-(KEYBOARD_SHIFT_LOWERA-QH*-Pad9)") (class "Default")
      (node (ref "KEYBOARD_SHIFT_LOWER") (pin "9") (pinfunction "QH*_9") (pintype "tri_state"))
    )
    (net (code "375") (name "unconnected-(KEYBOARD_SHIFT_LOWERA-QH-Pad7)") (class "Default")
      (node (ref "KEYBOARD_SHIFT_LOWER") (pin "7") (pinfunction "QH_7") (pintype "tri_state"))
    )
    (net (code "376") (name "unconnected-(KEYBOARD_SHIFT_UPPERA-QA-Pad15)") (class "Default")
      (node (ref "KEYBOARD_SHIFT_UPPER") (pin "15") (pinfunction "QA_15") (pintype "tri_state"))
    )
    (net (code "377") (name "unconnected-(KEYBOARD_SHIFT_UPPERA-QB-Pad1)") (class "Default")
      (node (ref "KEYBOARD_SHIFT_UPPER") (pin "1") (pinfunction "QB_1") (pintype "tri_state"))
    )
    (net (code "378") (name "unconnected-(MEMORY-Pad1)") (class "Default")
      (node (ref "MEMORY") (pin "1") (pinfunction "1_1") (pintype "passive"))
    )
    (net (code "379") (name "unconnected-(MEMORY-Pad26)") (class "Default")
      (node (ref "MEMORY") (pin "26") (pinfunction "26_26") (pintype "passive"))
    )
    (net (code "380") (name "unconnected-(MICRO_COUNTER_UPPER-Pad4)") (class "Default")
      (node (ref "MICRO_COUNTER_UPPER") (pin "4") (pinfunction "4_4") (pintype "passive"))
    )
    (net (code "381") (name "unconnected-(MICRO_COUNTER_UPPER-Pad5)") (class "Default")
      (node (ref "MICRO_COUNTER_UPPER") (pin "5") (pinfunction "5_5") (pintype "passive"))
    )
    (net (code "382") (name "unconnected-(MICRO_COUNTER_UPPER-Pad6)") (class "Default")
      (node (ref "MICRO_COUNTER_UPPER") (pin "6") (pinfunction "6_6") (pintype "passive"))
    )
    (net (code "383") (name "unconnected-(MICRO_COUNTER_UPPER-Pad11)") (class "Default")
      (node (ref "MICRO_COUNTER_UPPER") (pin "11") (pinfunction "11_11") (pintype "passive"))
    )
    (net (code "384") (name "unconnected-(MICRO_COUNTER_UPPER-Pad12)") (class "Default")
      (node (ref "MICRO_COUNTER_UPPER") (pin "12") (pinfunction "12_12") (pintype "passive"))
    )
    (net (code "385") (name "unconnected-(MICRO_COUNTER_UPPER-Pad13)") (class "Default")
      (node (ref "MICRO_COUNTER_UPPER") (pin "13") (pinfunction "13_13") (pintype "passive"))
    )
    (net (code "386") (name "unconnected-(MICRO_COUNTER_UPPER-Pad15)") (class "Default")
      (node (ref "MICRO_COUNTER_UPPER") (pin "15") (pinfunction "15_15") (pintype "passive"))
    )
    (net (code "387") (name "unconnected-(OUT_ROM_LOWER-Pad1)") (class "Default")
      (node (ref "OUT_ROM_LOWER") (pin "1") (pinfunction "1_1") (pintype "passive"))
    )
    (net (code "388") (name "unconnected-(OUT_ROM_LOWER-Pad26)") (class "Default")
      (node (ref "OUT_ROM_LOWER") (pin "26") (pinfunction "26_26") (pintype "passive"))
    )
    (net (code "389") (name "unconnected-(OUT_ROM_UPPER-Pad1)") (class "Default")
      (node (ref "OUT_ROM_UPPER") (pin "1") (pinfunction "1_1") (pintype "passive"))
    )
    (net (code "390") (name "unconnected-(OUT_ROM_UPPER-Pad26)") (class "Default")
      (node (ref "OUT_ROM_UPPER") (pin "26") (pinfunction "26_26") (pintype "passive"))
    )
    (net (code "391") (name "unconnected-(PROGRAM_COUNTER_UPPER-Pad15)") (class "Default")
      (node (ref "PROGRAM_COUNTER_UPPER") (pin "15") (pinfunction "15_15") (pintype "passive"))
    )
    (net (code "392") (name "unconnected-(RAM1-Pad1)") (class "Default")
      (node (ref "RAM1") (pin "1") (pinfunction "1_1") (pintype "passive"))
    )
    (net (code "393") (name "unconnected-(RAM1-Pad2)") (class "Default")
      (node (ref "RAM1") (pin "2") (pinfunction "2_2") (pintype "passive"))
    )
    (net (code "394") (name "unconnected-(RAM1-Pad3)") (class "Default")
      (node (ref "RAM1") (pin "3") (pinfunction "3_3") (pintype "passive"))
    )
    (net (code "395") (name "unconnected-(RAM1-Pad4)") (class "Default")
      (node (ref "RAM1") (pin "4") (pinfunction "4_4") (pintype "passive"))
    )
    (net (code "396") (name "unconnected-(RAM1-Pad5)") (class "Default")
      (node (ref "RAM1") (pin "5") (pinfunction "5_5") (pintype "passive"))
    )
    (net (code "397") (name "unconnected-(RAM1-Pad6)") (class "Default")
      (node (ref "RAM1") (pin "6") (pinfunction "6_6") (pintype "passive"))
    )
    (net (code "398") (name "unconnected-(RAM1-Pad7)") (class "Default")
      (node (ref "RAM1") (pin "7") (pinfunction "7_7") (pintype "passive"))
    )
    (net (code "399") (name "unconnected-(RAM1-Pad8)") (class "Default")
      (node (ref "RAM1") (pin "8") (pinfunction "8_8") (pintype "passive"))
    )
    (net (code "400") (name "unconnected-(RAM1-Pad9)") (class "Default")
      (node (ref "RAM1") (pin "9") (pinfunction "9_9") (pintype "passive"))
    )
    (net (code "401") (name "unconnected-(RAM1-Pad10)") (class "Default")
      (node (ref "RAM1") (pin "10") (pinfunction "10_10") (pintype "passive"))
    )
    (net (code "402") (name "unconnected-(RAM1-Pad11)") (class "Default")
      (node (ref "RAM1") (pin "11") (pinfunction "11_11") (pintype "passive"))
    )
    (net (code "403") (name "unconnected-(RAM1-Pad12)") (class "Default")
      (node (ref "RAM1") (pin "12") (pinfunction "12_12") (pintype "passive"))
    )
    (net (code "404") (name "unconnected-(RAM1-Pad13)") (class "Default")
      (node (ref "RAM1") (pin "13") (pinfunction "13_13") (pintype "passive"))
    )
    (net (code "405") (name "unconnected-(RAM1-Pad14)") (class "Default")
      (node (ref "RAM1") (pin "14") (pinfunction "14_14") (pintype "passive"))
    )
    (net (code "406") (name "unconnected-(RAM1-Pad15)") (class "Default")
      (node (ref "RAM1") (pin "15") (pinfunction "15_15") (pintype "passive"))
    )
    (net (code "407") (name "unconnected-(RAM1-Pad16)") (class "Default")
      (node (ref "RAM1") (pin "16") (pinfunction "16_16") (pintype "passive"))
    )
    (net (code "408") (name "unconnected-(RAM1-Pad17)") (class "Default")
      (node (ref "RAM1") (pin "17") (pinfunction "17_17") (pintype "passive"))
    )
    (net (code "409") (name "unconnected-(RAM1-Pad18)") (class "Default")
      (node (ref "RAM1") (pin "18") (pinfunction "18_18") (pintype "passive"))
    )
    (net (code "410") (name "unconnected-(RAM1-Pad19)") (class "Default")
      (node (ref "RAM1") (pin "19") (pinfunction "19_19") (pintype "passive"))
    )
    (net (code "411") (name "unconnected-(RAM1-Pad20)") (class "Default")
      (node (ref "RAM1") (pin "20") (pinfunction "20_20") (pintype "passive"))
    )
    (net (code "412") (name "unconnected-(RAM1-Pad21)") (class "Default")
      (node (ref "RAM1") (pin "21") (pinfunction "21_21") (pintype "passive"))
    )
    (net (code "413") (name "unconnected-(RAM1-Pad22)") (class "Default")
      (node (ref "RAM1") (pin "22") (pinfunction "22_22") (pintype "passive"))
    )
    (net (code "414") (name "unconnected-(RAM1-Pad23)") (class "Default")
      (node (ref "RAM1") (pin "23") (pinfunction "23_23") (pintype "passive"))
    )
    (net (code "415") (name "unconnected-(RAM1-Pad24)") (class "Default")
      (node (ref "RAM1") (pin "24") (pinfunction "24_24") (pintype "passive"))
    )
    (net (code "416") (name "unconnected-(RAM1-Pad25)") (class "Default")
      (node (ref "RAM1") (pin "25") (pinfunction "25_25") (pintype "passive"))
    )
    (net (code "417") (name "unconnected-(RAM1-Pad26)") (class "Default")
      (node (ref "RAM1") (pin "26") (pinfunction "26_26") (pintype "passive"))
    )
    (net (code "418") (name "unconnected-(RAM1-Pad27)") (class "Default")
      (node (ref "RAM1") (pin "27") (pinfunction "27_27") (pintype "passive"))
    )
    (net (code "419") (name "unconnected-(RAM1-Pad28)") (class "Default")
      (node (ref "RAM1") (pin "28") (pinfunction "28_28") (pintype "passive"))
    )
    (net (code "420") (name "unconnected-(RESET_PC-P-Pad3)") (class "Default")
      (node (ref "RESET_PC") (pin "3") (pinfunction "P_3") (pintype "passive"))
    )
    (net (code "421") (name "unconnected-(RESET_PC-S1-Pad2)") (class "Default")
      (node (ref "RESET_PC") (pin "2") (pinfunction "S1_2") (pintype "passive"))
    )
    (net (code "422") (name "unconnected-(RESET_REGS-P-Pad3)") (class "Default")
      (node (ref "RESET_REGS") (pin "3") (pinfunction "P_3") (pintype "passive"))
    )
    (net (code "423") (name "unconnected-(RESET_REGS-S1-Pad2)") (class "Default")
      (node (ref "RESET_REGS") (pin "2") (pinfunction "S1_2") (pintype "passive"))
    )
    (net (code "424") (name "unconnected-(SELECTOR_BRANCH_B-Y0-Pad12)") (class "Default")
      (node (ref "SELECTOR_BRANCH_") (pin "12") (pinfunction "Y0_12") (pintype "output"))
    )
    (net (code "425") (name "unconnected-(SELECTOR_LOGIC_A-Y0-Pad4)") (class "Default")
      (node (ref "SELECTOR_LOGIC_") (pin "4") (pinfunction "Y0_4") (pintype "output"))
    )
    (net (code "426") (name "unconnected-(SELECTOR_LOGIC_B-Y0-Pad12)") (class "Default")
      (node (ref "SELECTOR_LOGIC_") (pin "12") (pinfunction "Y0_12") (pintype "output"))
    )
    (net (code "427") (name "unconnected-(SELECTOR_PARAM_A-Y0-Pad4)") (class "Default")
      (node (ref "SELECTOR_PARAM_") (pin "4") (pinfunction "Y0_4") (pintype "output"))
    )
    (net (code "428") (name "unconnected-(SELECTOR_PARAM_B-Y0-Pad12)") (class "Default")
      (node (ref "SELECTOR_PARAM_") (pin "12") (pinfunction "Y0_12") (pintype "output"))
    )
    (net (code "429") (name "unconnected-(SELECTOR_STACK_A-Y0-Pad4)") (class "Default")
      (node (ref "SELECTOR_STACK_") (pin "4") (pinfunction "Y0_4") (pintype "output"))
    )
    (net (code "430") (name "unconnected-(SELECTOR_STACK_B-Y0-Pad12)") (class "Default")
      (node (ref "SELECTOR_STACK_") (pin "12") (pinfunction "Y0_12") (pintype "output"))
    )
    (net (code "431") (name "unconnected-(SELECTOR_STACK_B-Y1-Pad11)") (class "Default")
      (node (ref "SELECTOR_STACK_") (pin "11") (pinfunction "Y1_11") (pintype "output"))
    )
    (net (code "432") (name "unconnected-(SELECTOR_STACK_B-Y2-Pad10)") (class "Default")
      (node (ref "SELECTOR_STACK_") (pin "10") (pinfunction "Y2_10") (pintype "output"))
    )
    (net (code "433") (name "unconnected-(STEPPER_CLOCK-CV-Pad5)") (class "Default")
      (node (ref "STEPPER_CLOCK") (pin "5") (pinfunction "CV_5") (pintype "input"))
    )
    (net (code "434") (name "unconnected-(STEPPER_CLOCK-R-Pad4)") (class "Default")
      (node (ref "STEPPER_CLOCK") (pin "4") (pinfunction "R_4") (pintype "input"))
    )
    (net (code "435") (name "unconnected-(X1C-1-Pad3)") (class "Default")
      (node (ref "X1") (pin "3") (pinfunction "1_3") (pintype "passive"))
    )
  )
)
